# aqc-rev2.net
KiCad netlist of a schematic drawn in EAGLE
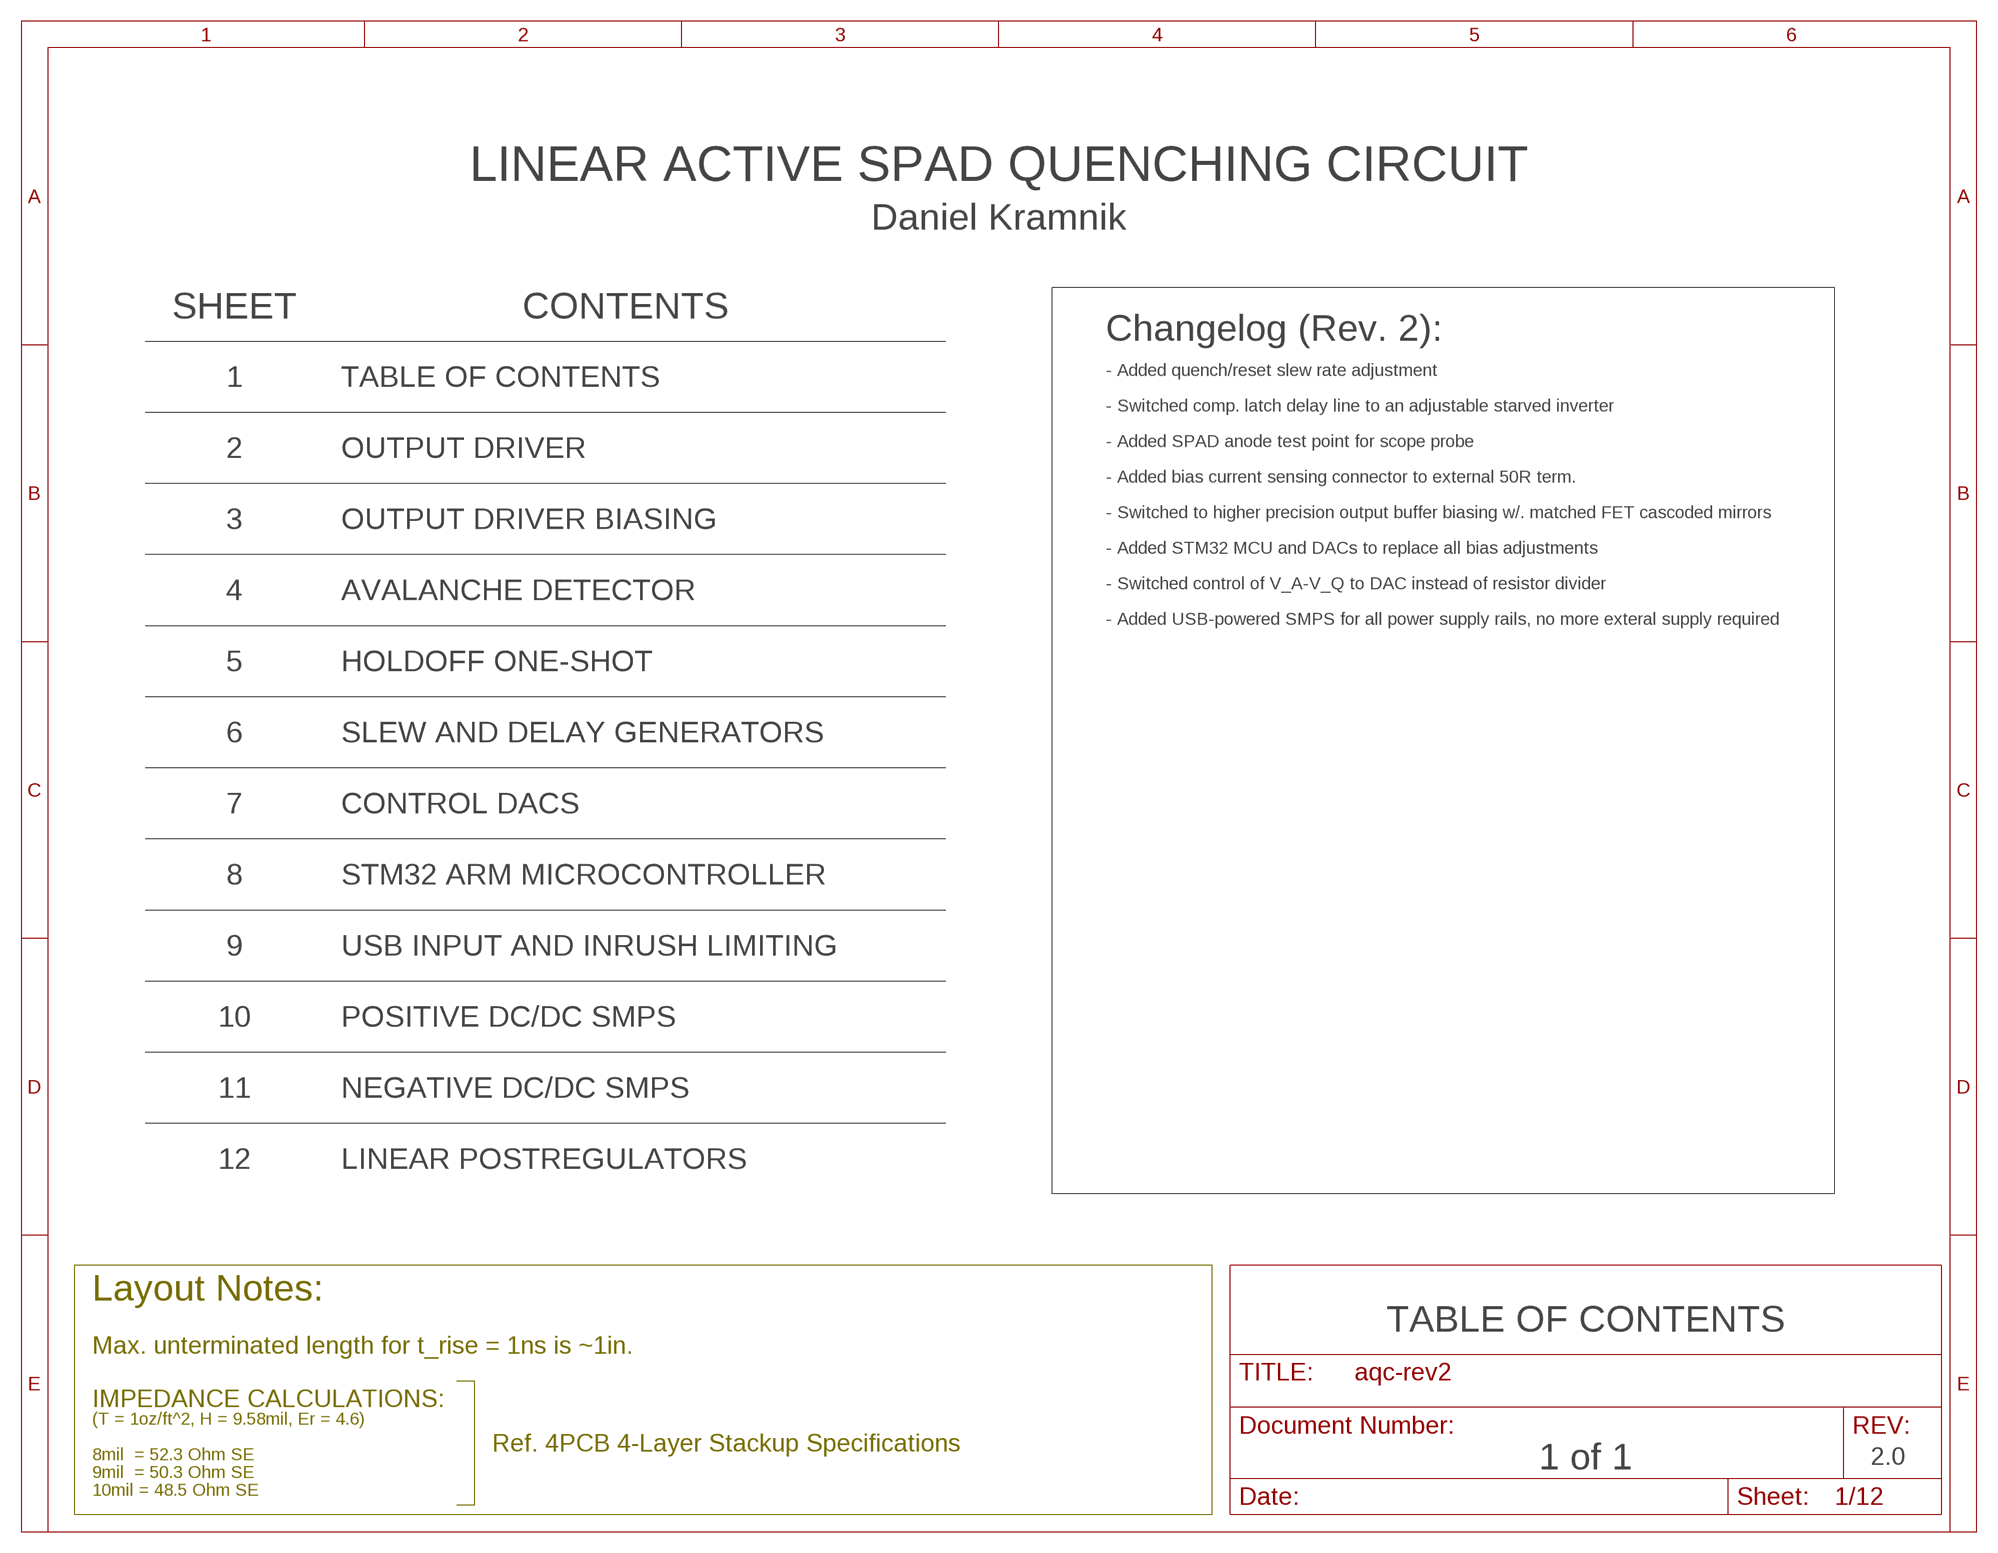
[diagram p0: schematic, sheet 1]
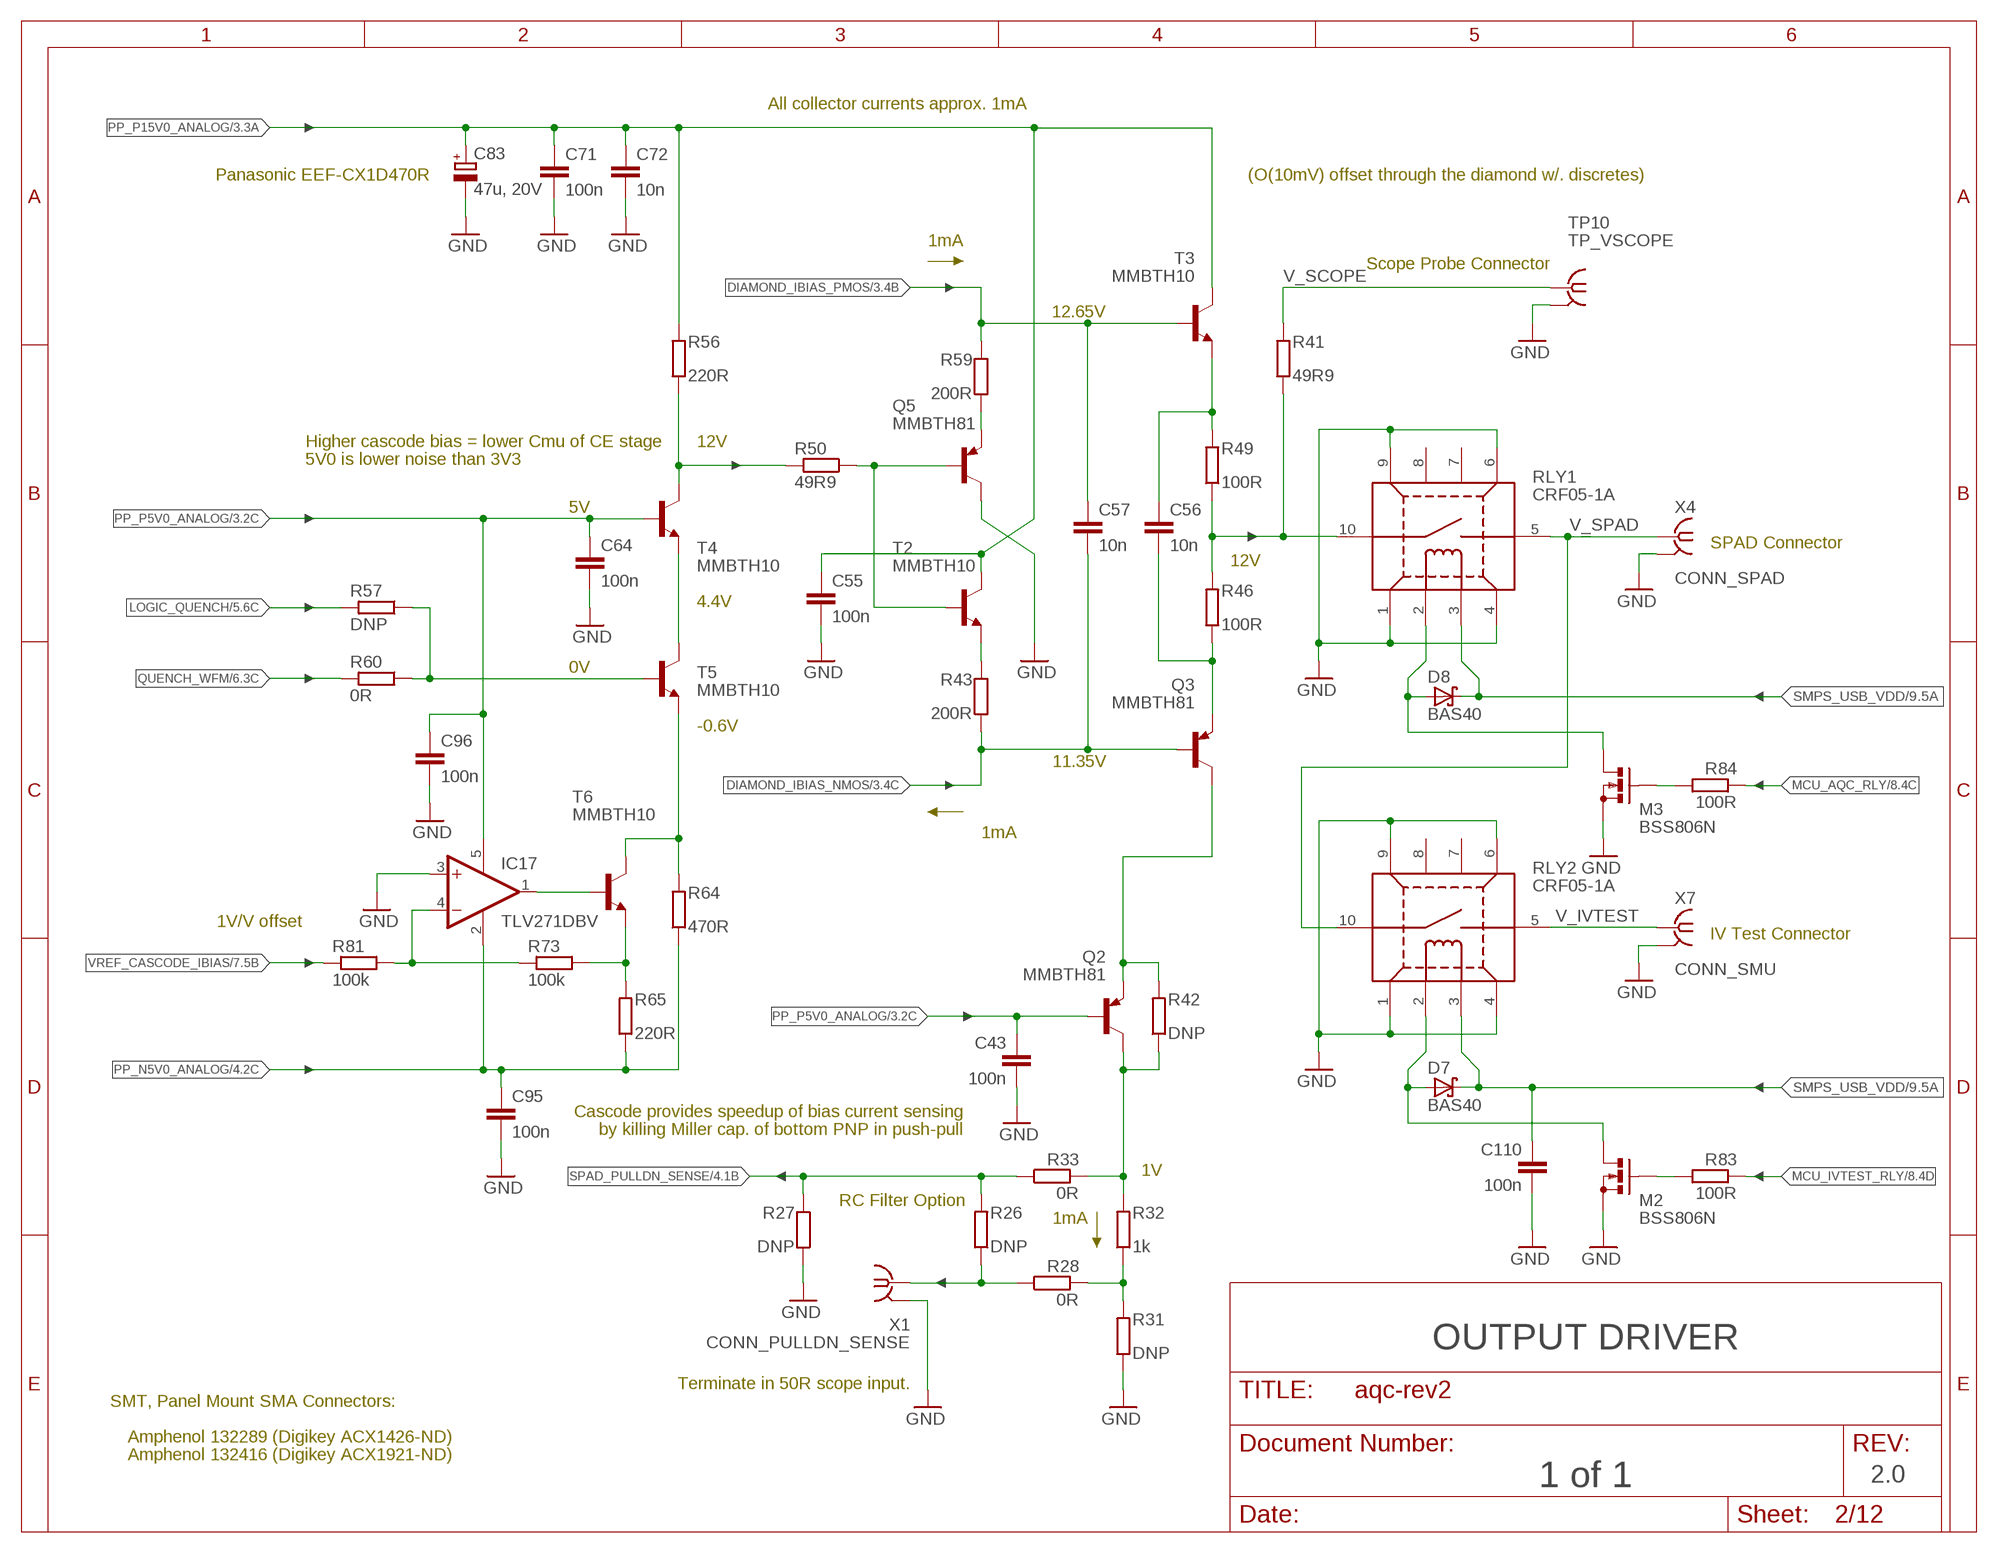
[diagram p1: schematic, sheet 2]
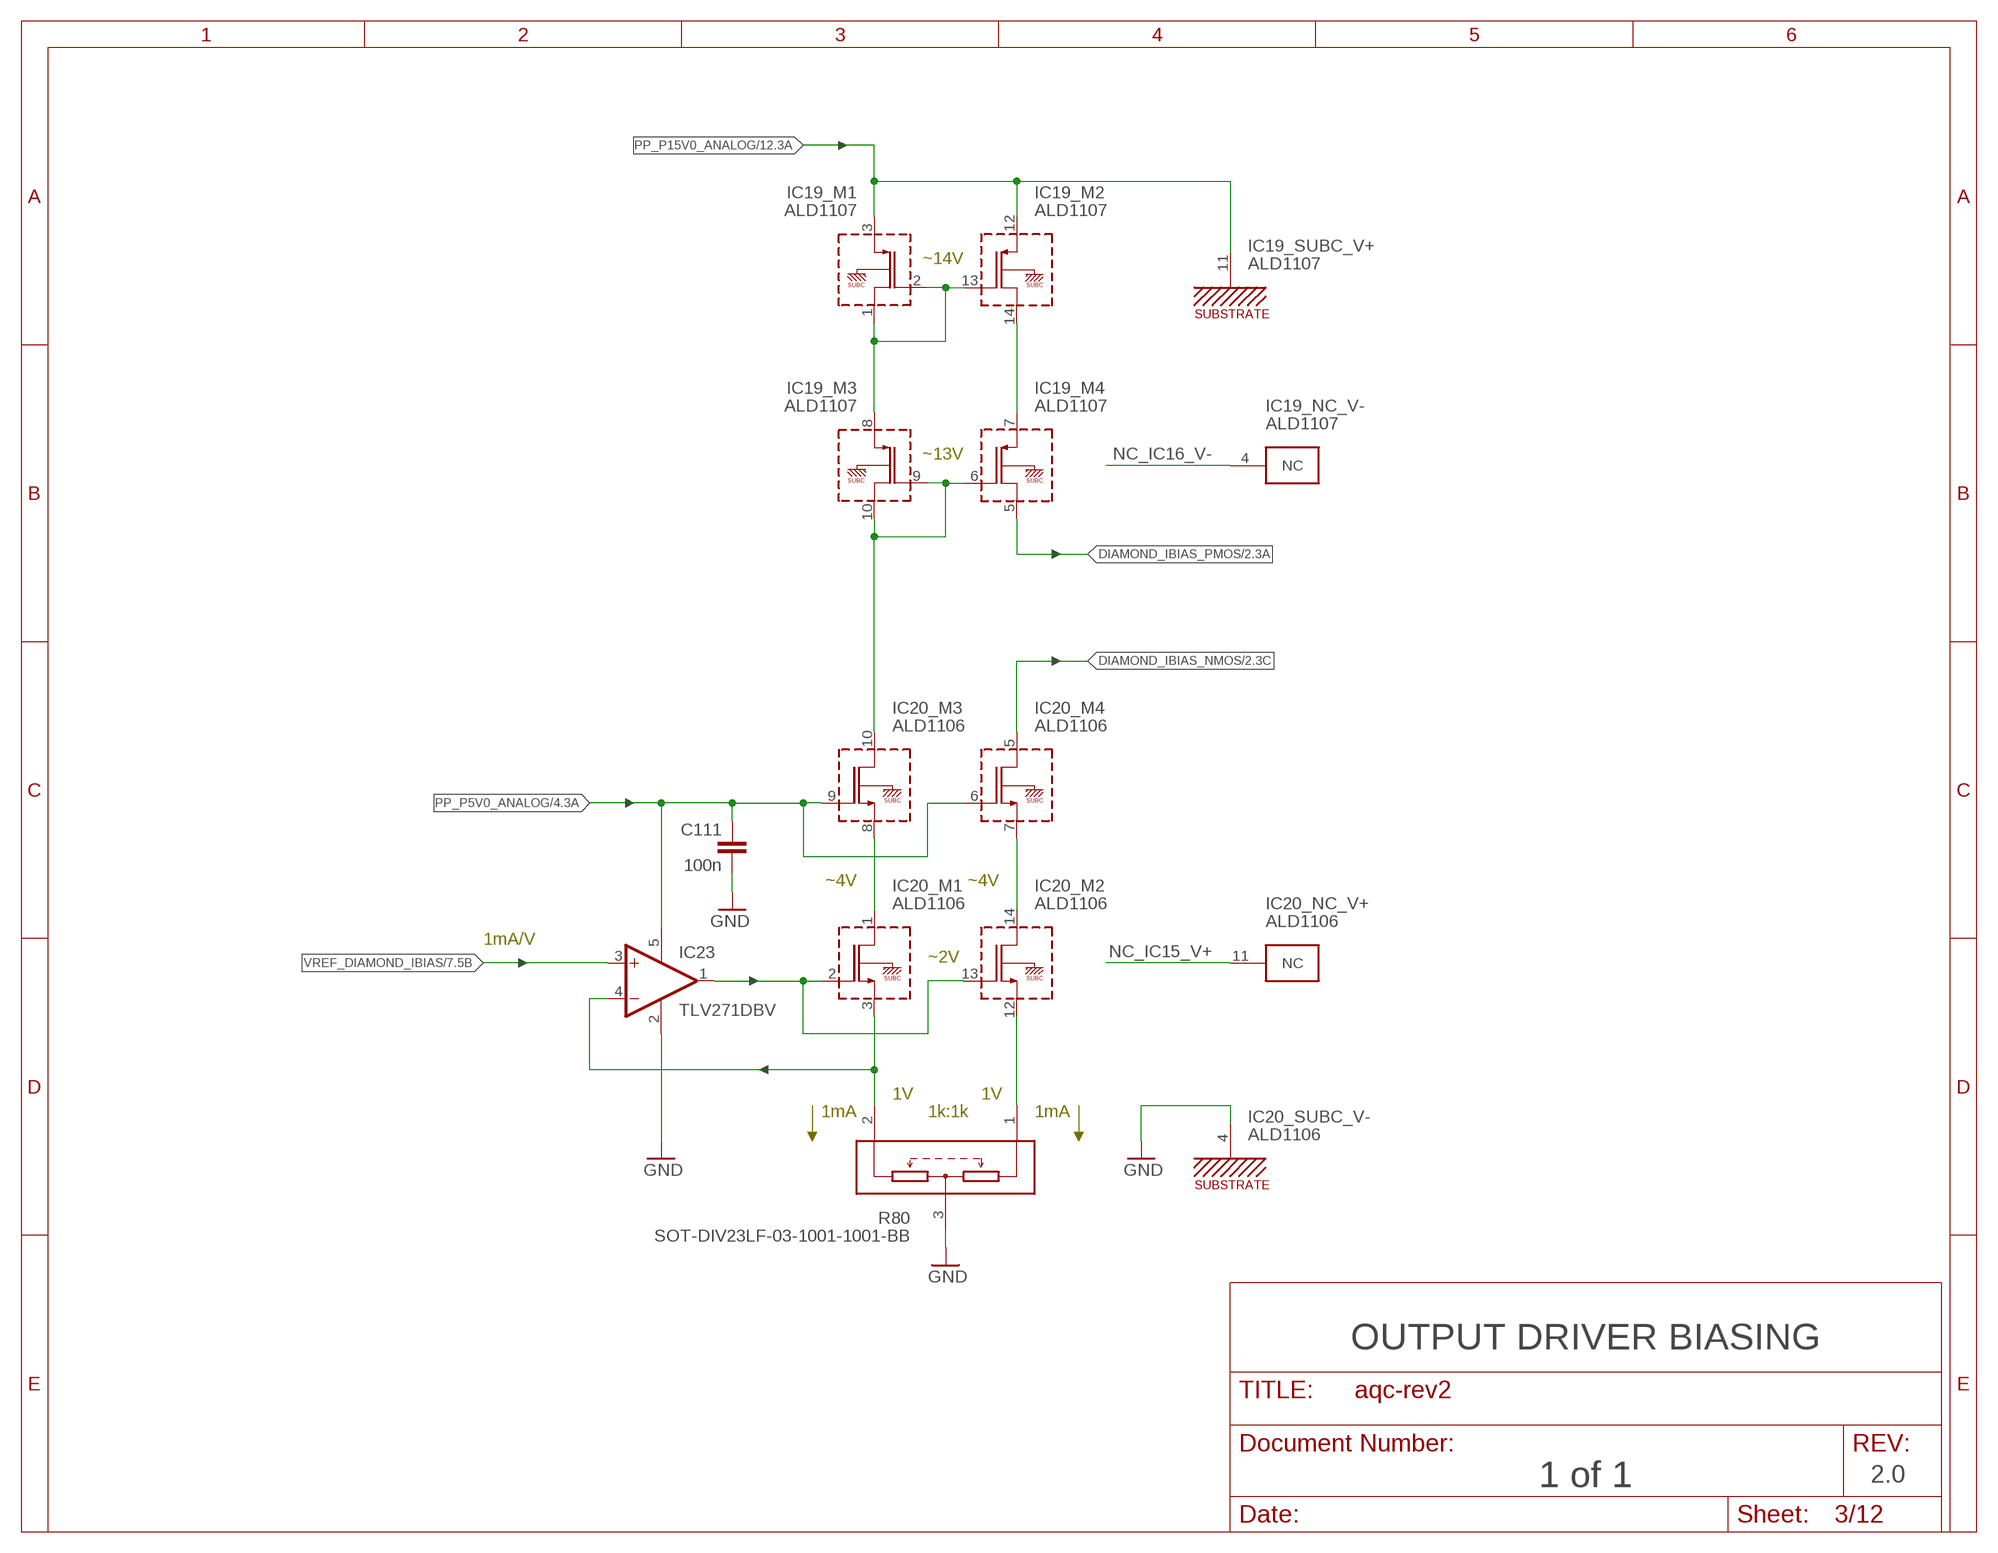
[diagram p2: schematic, sheet 3]
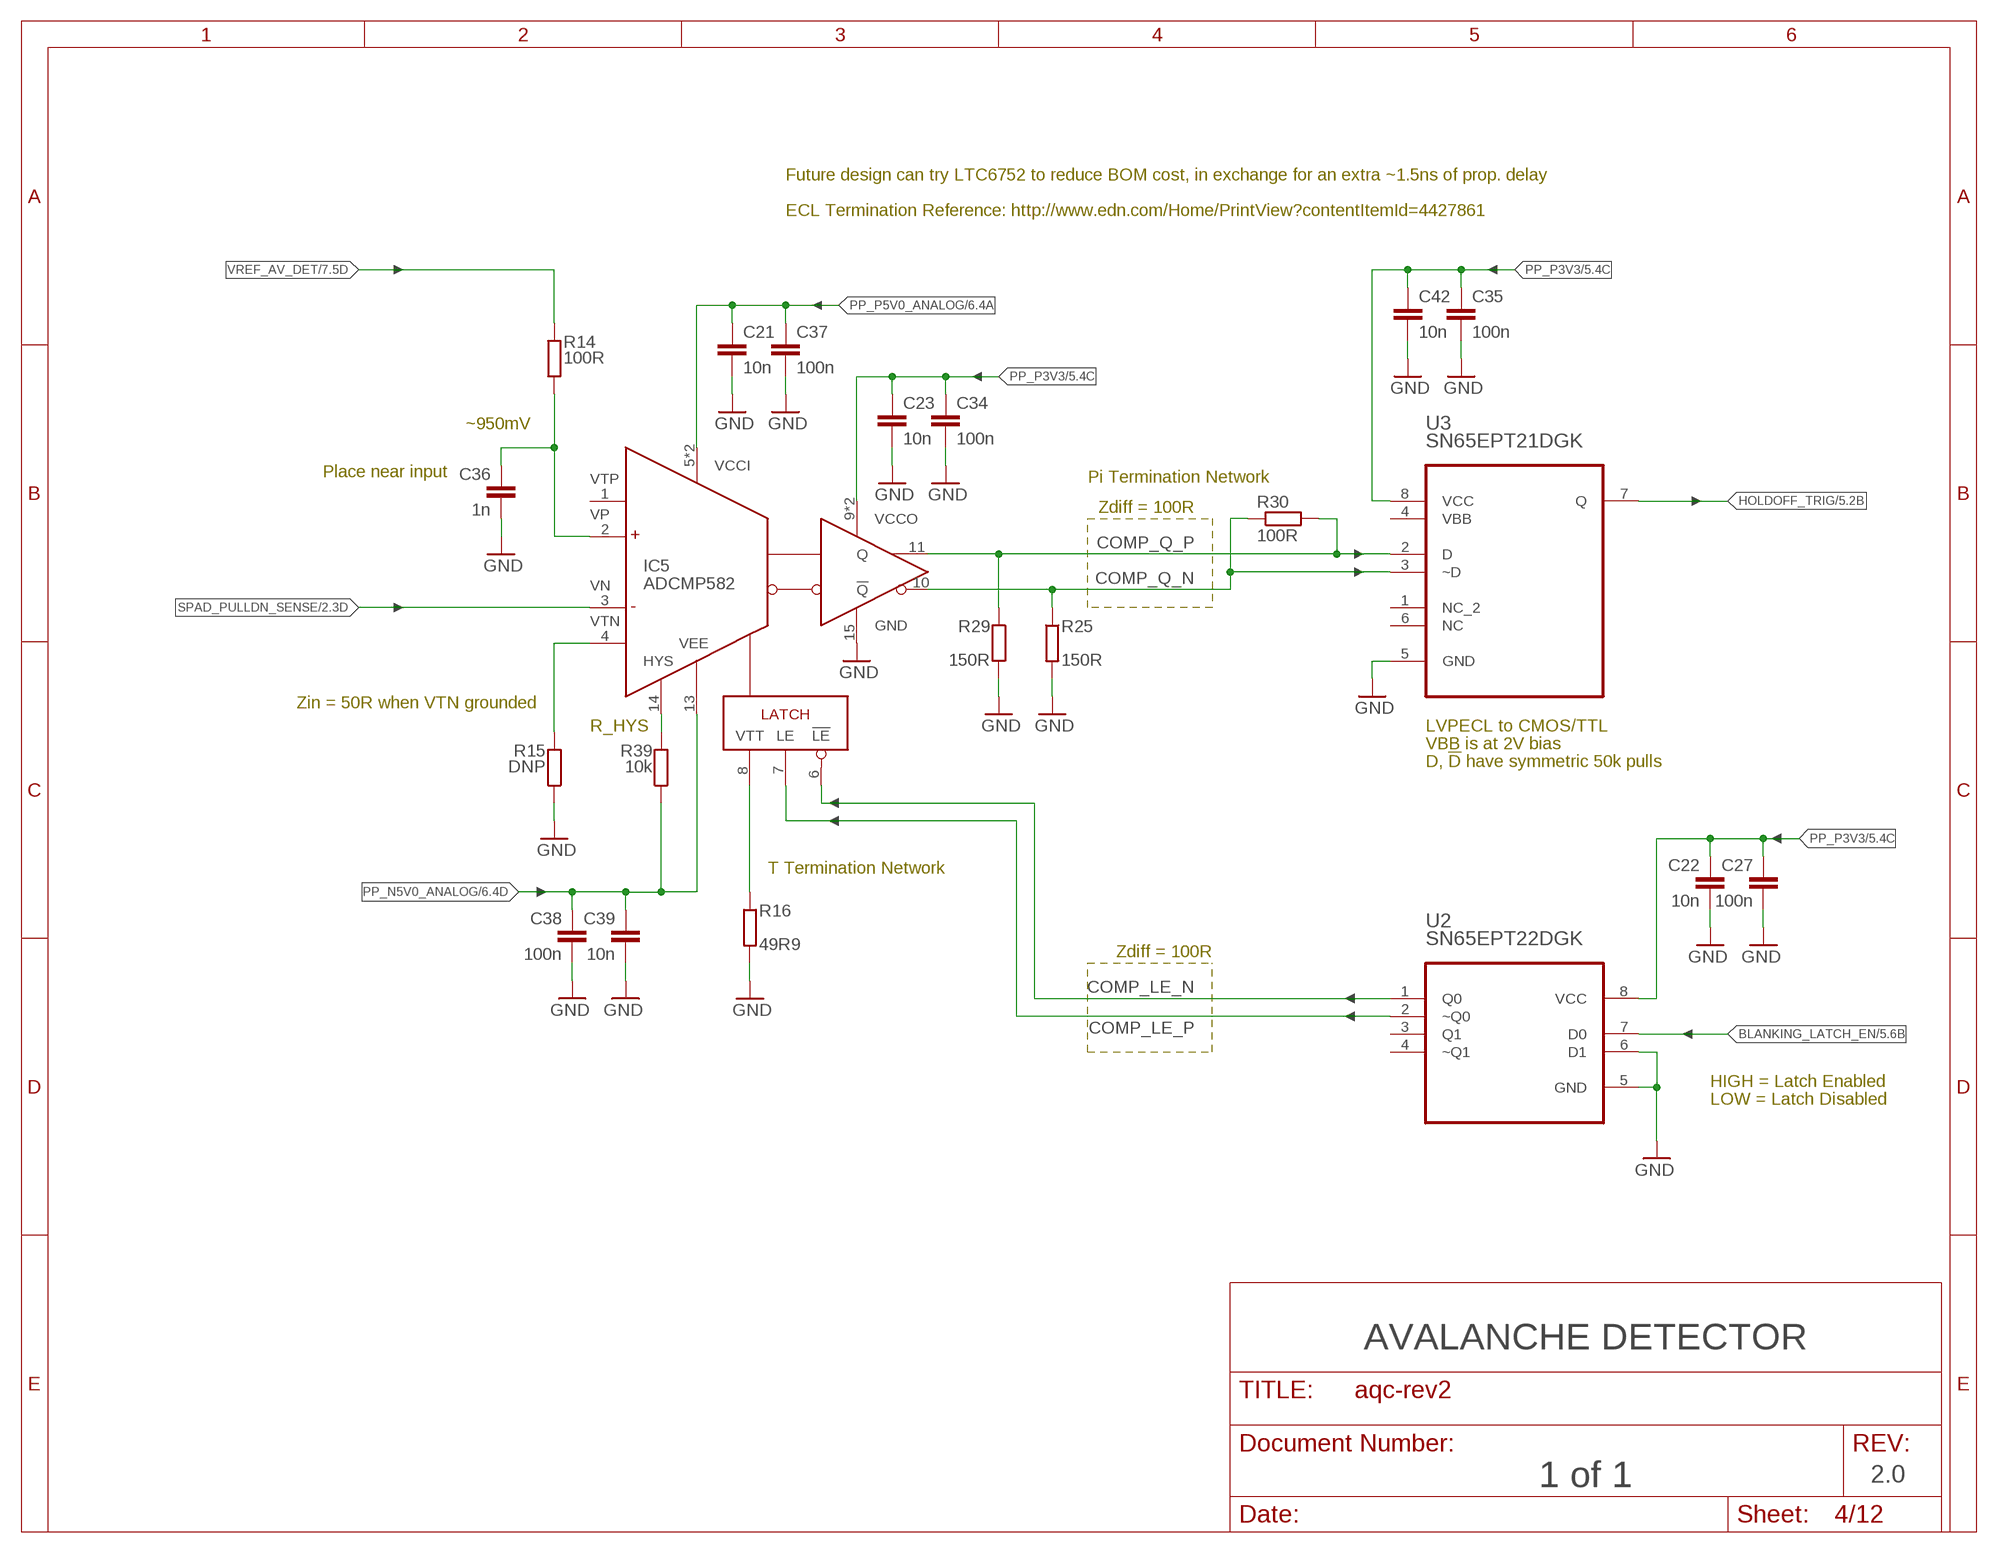
[diagram p3: schematic, sheet 4]
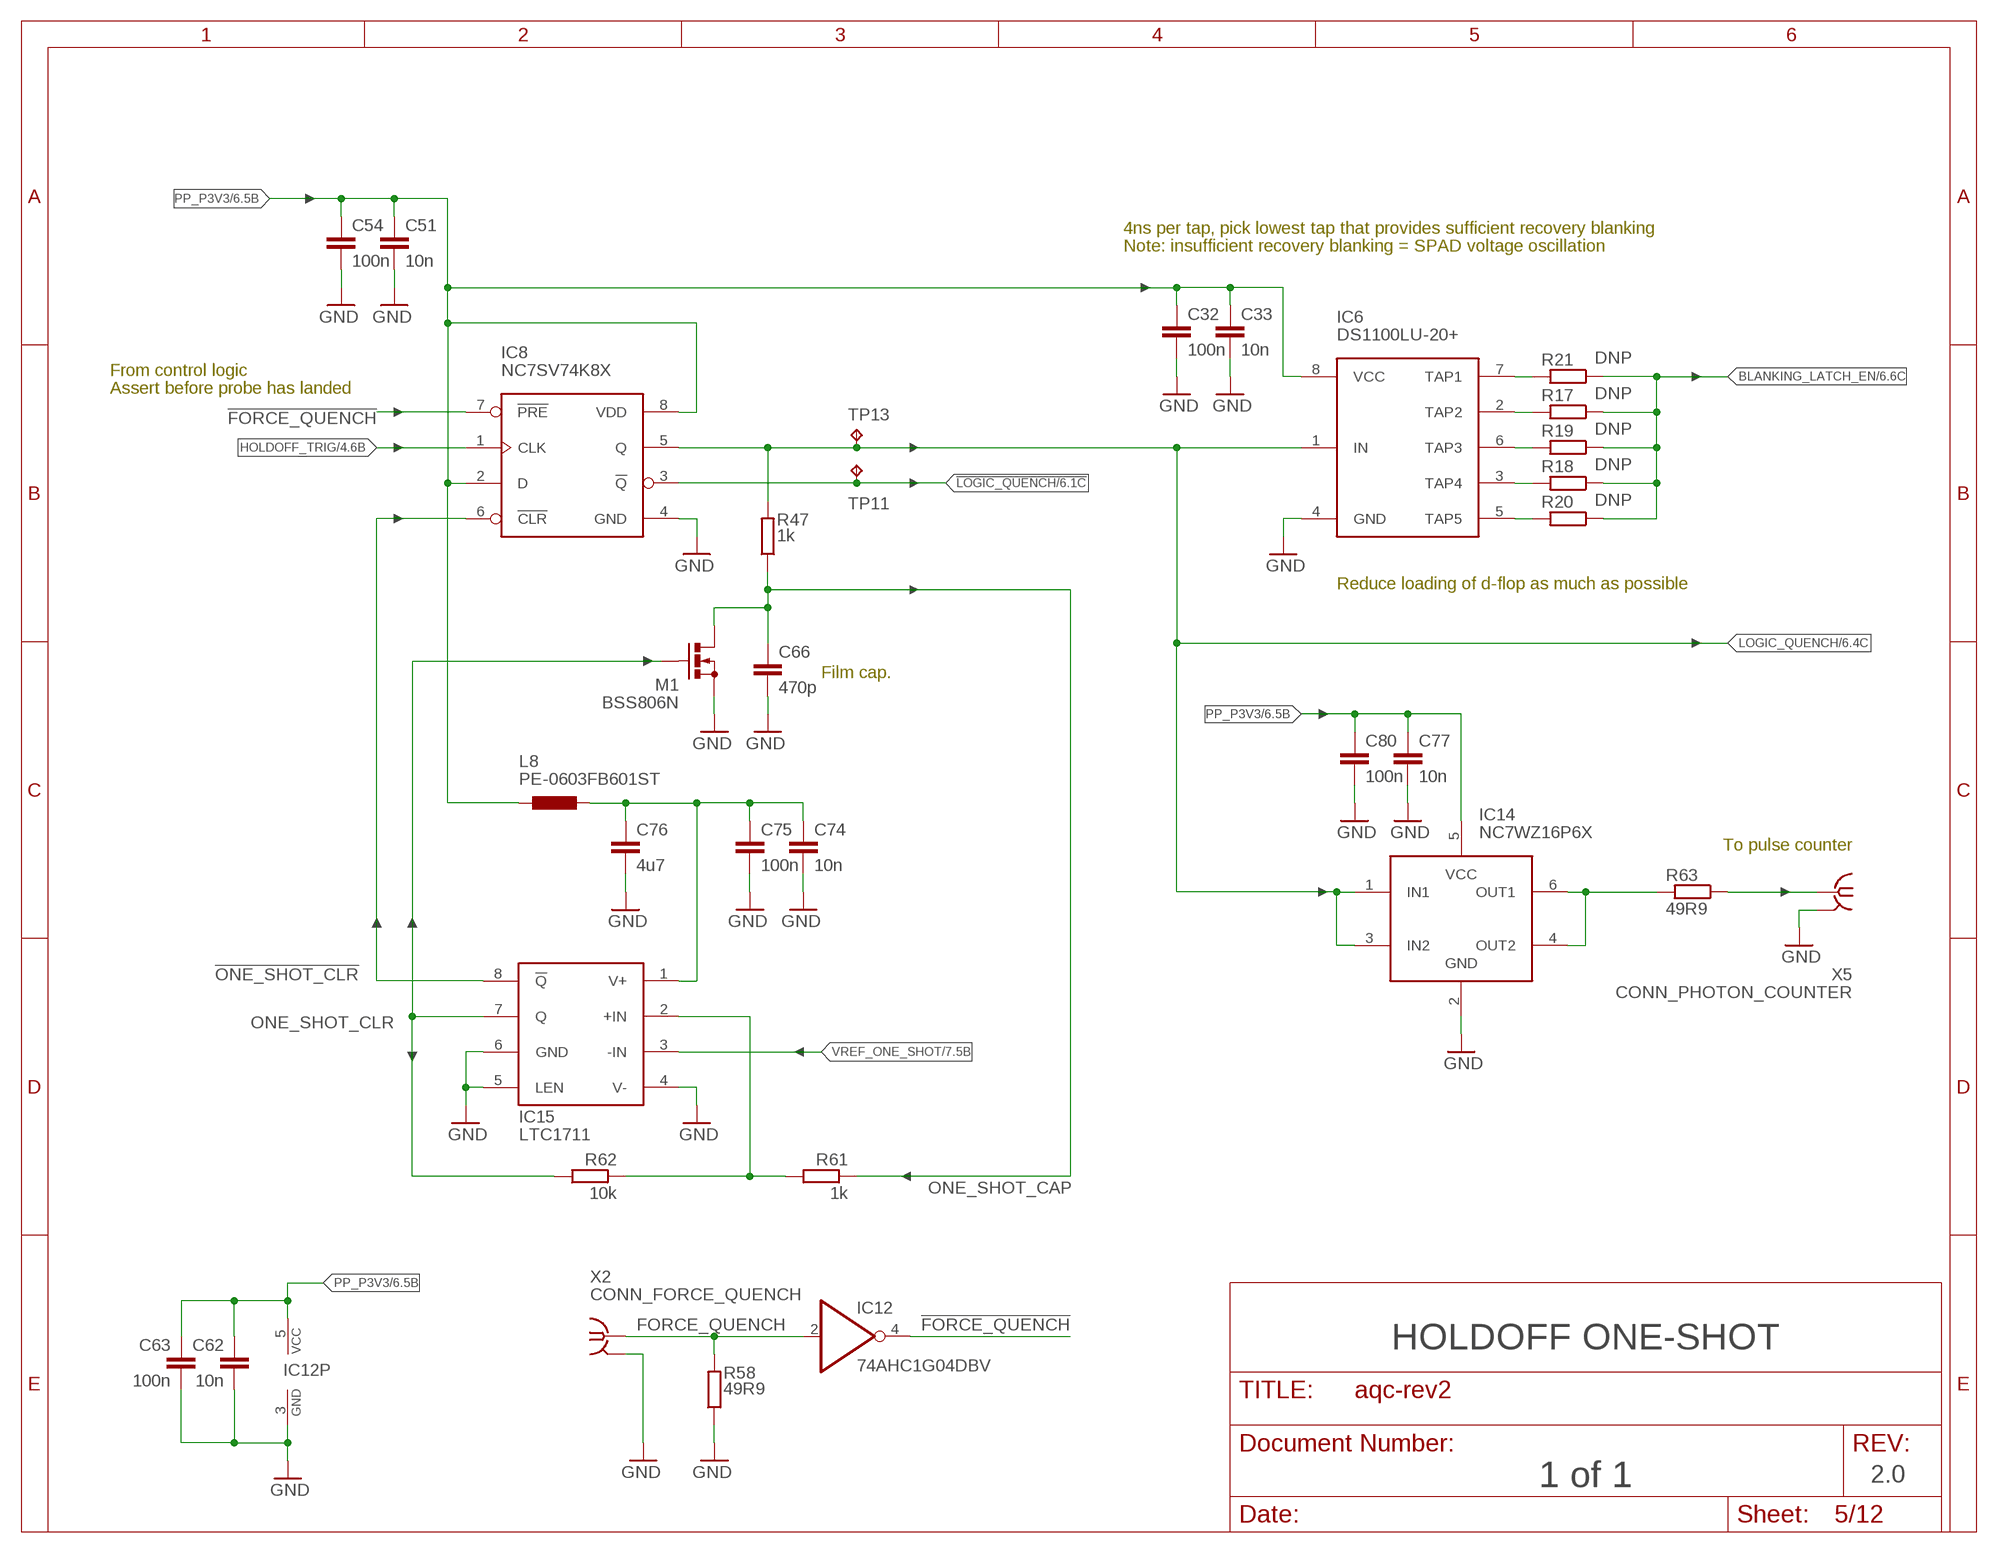
[diagram p4: schematic, sheet 5]
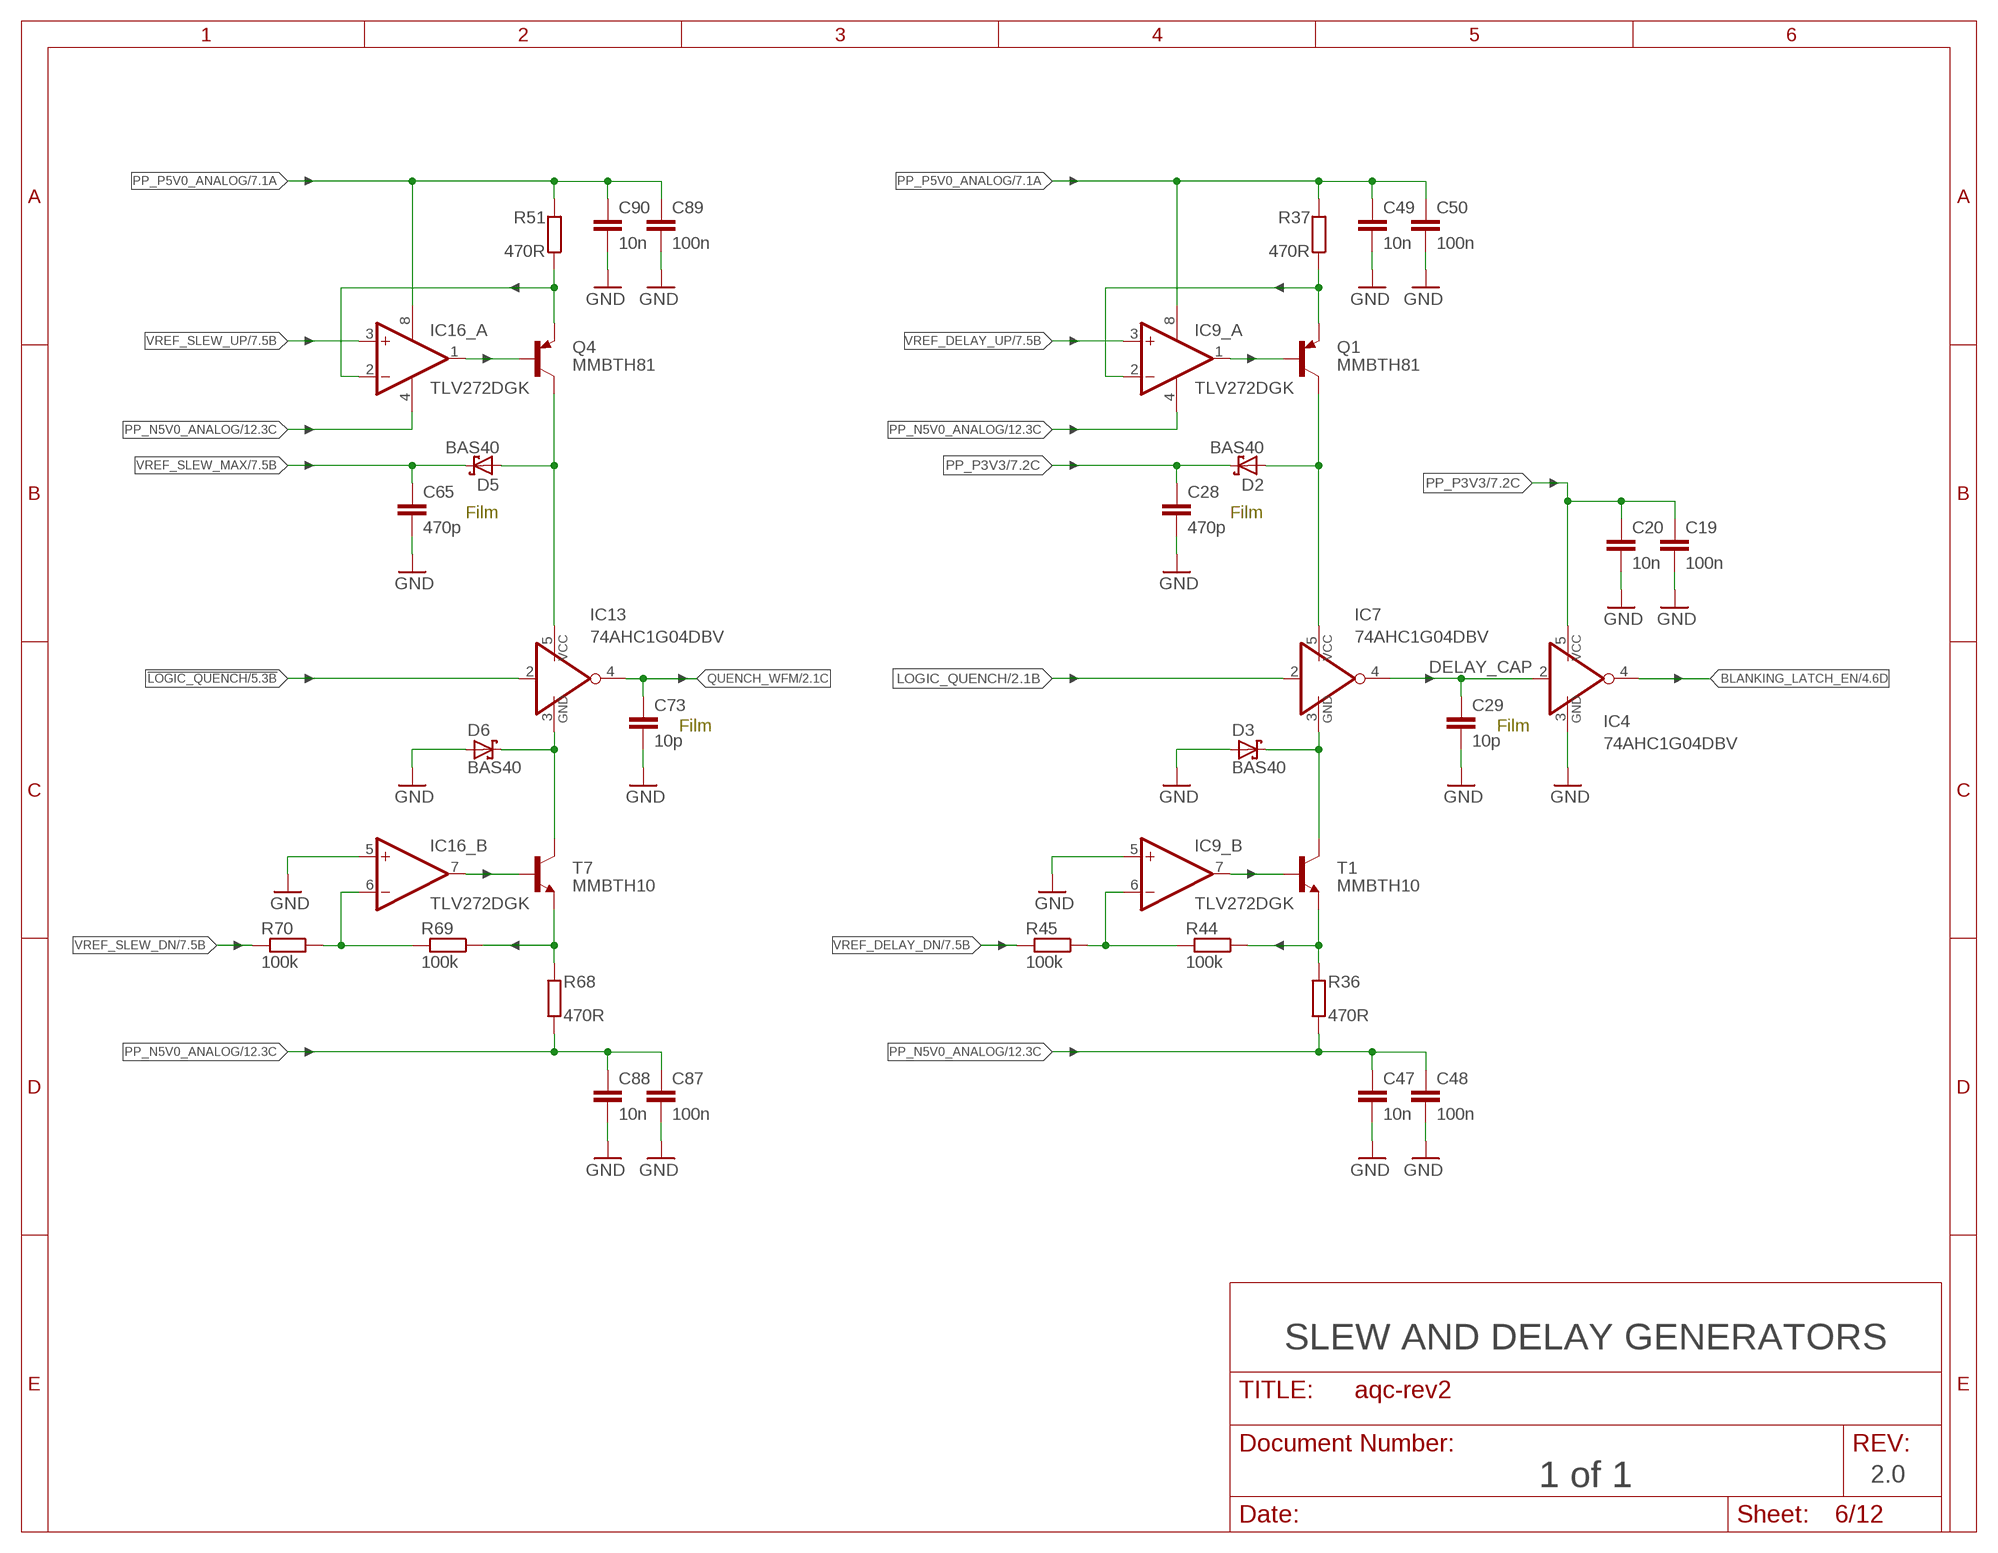
[diagram p5: schematic, sheet 6]
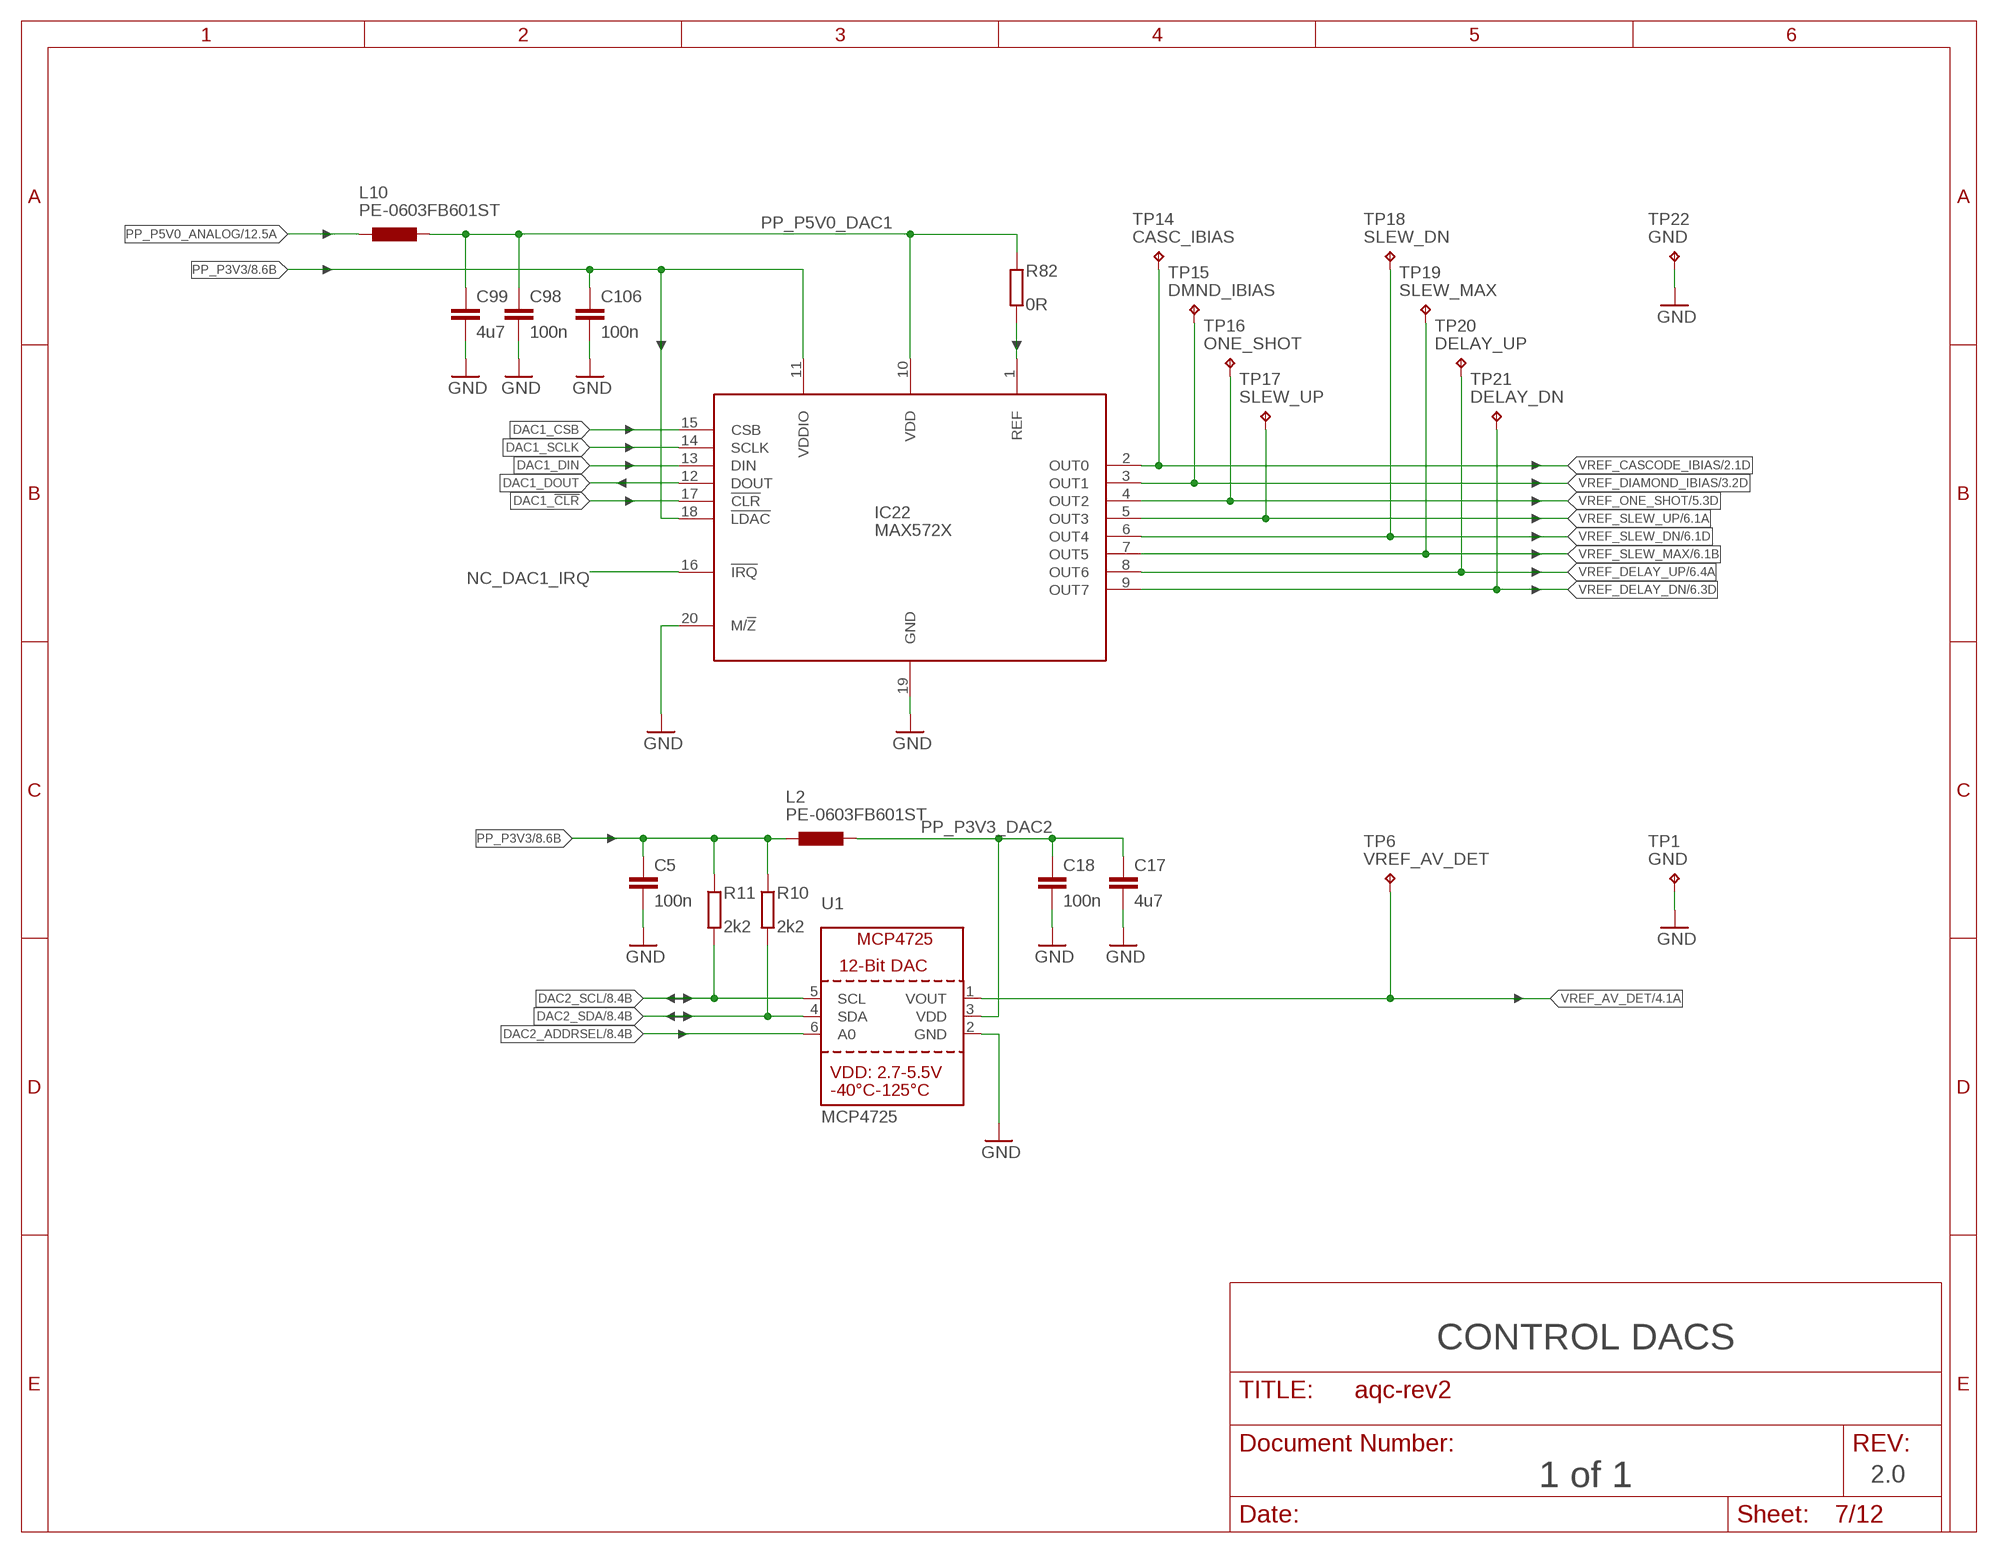
[diagram p6: schematic, sheet 7]
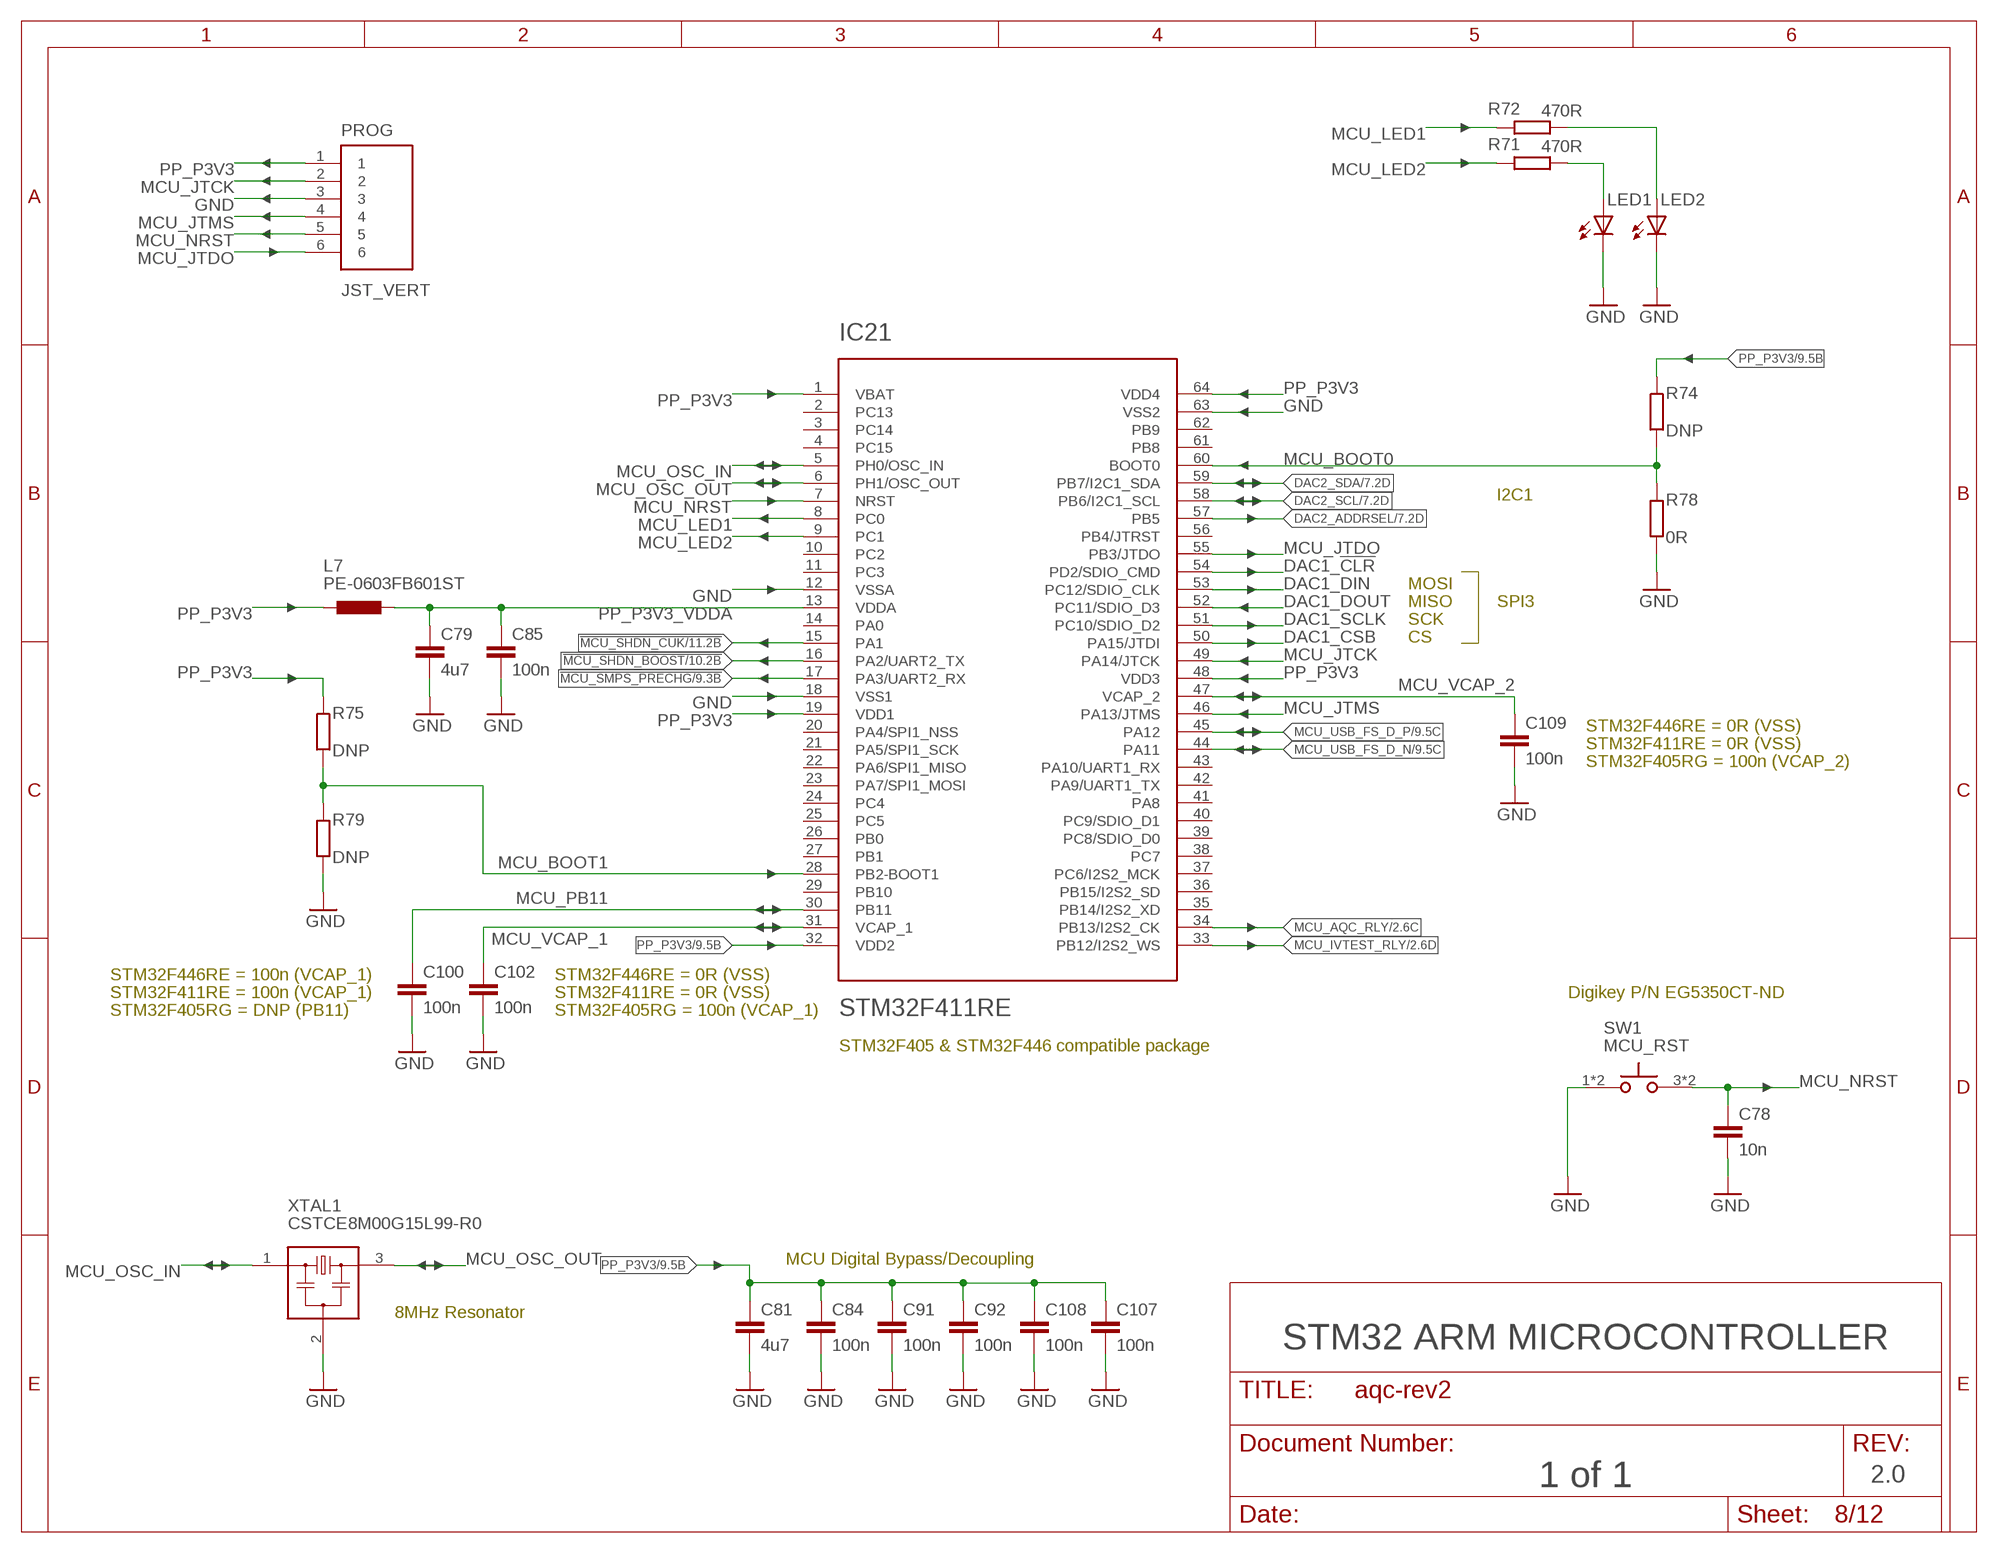
[diagram p7: schematic, sheet 8]
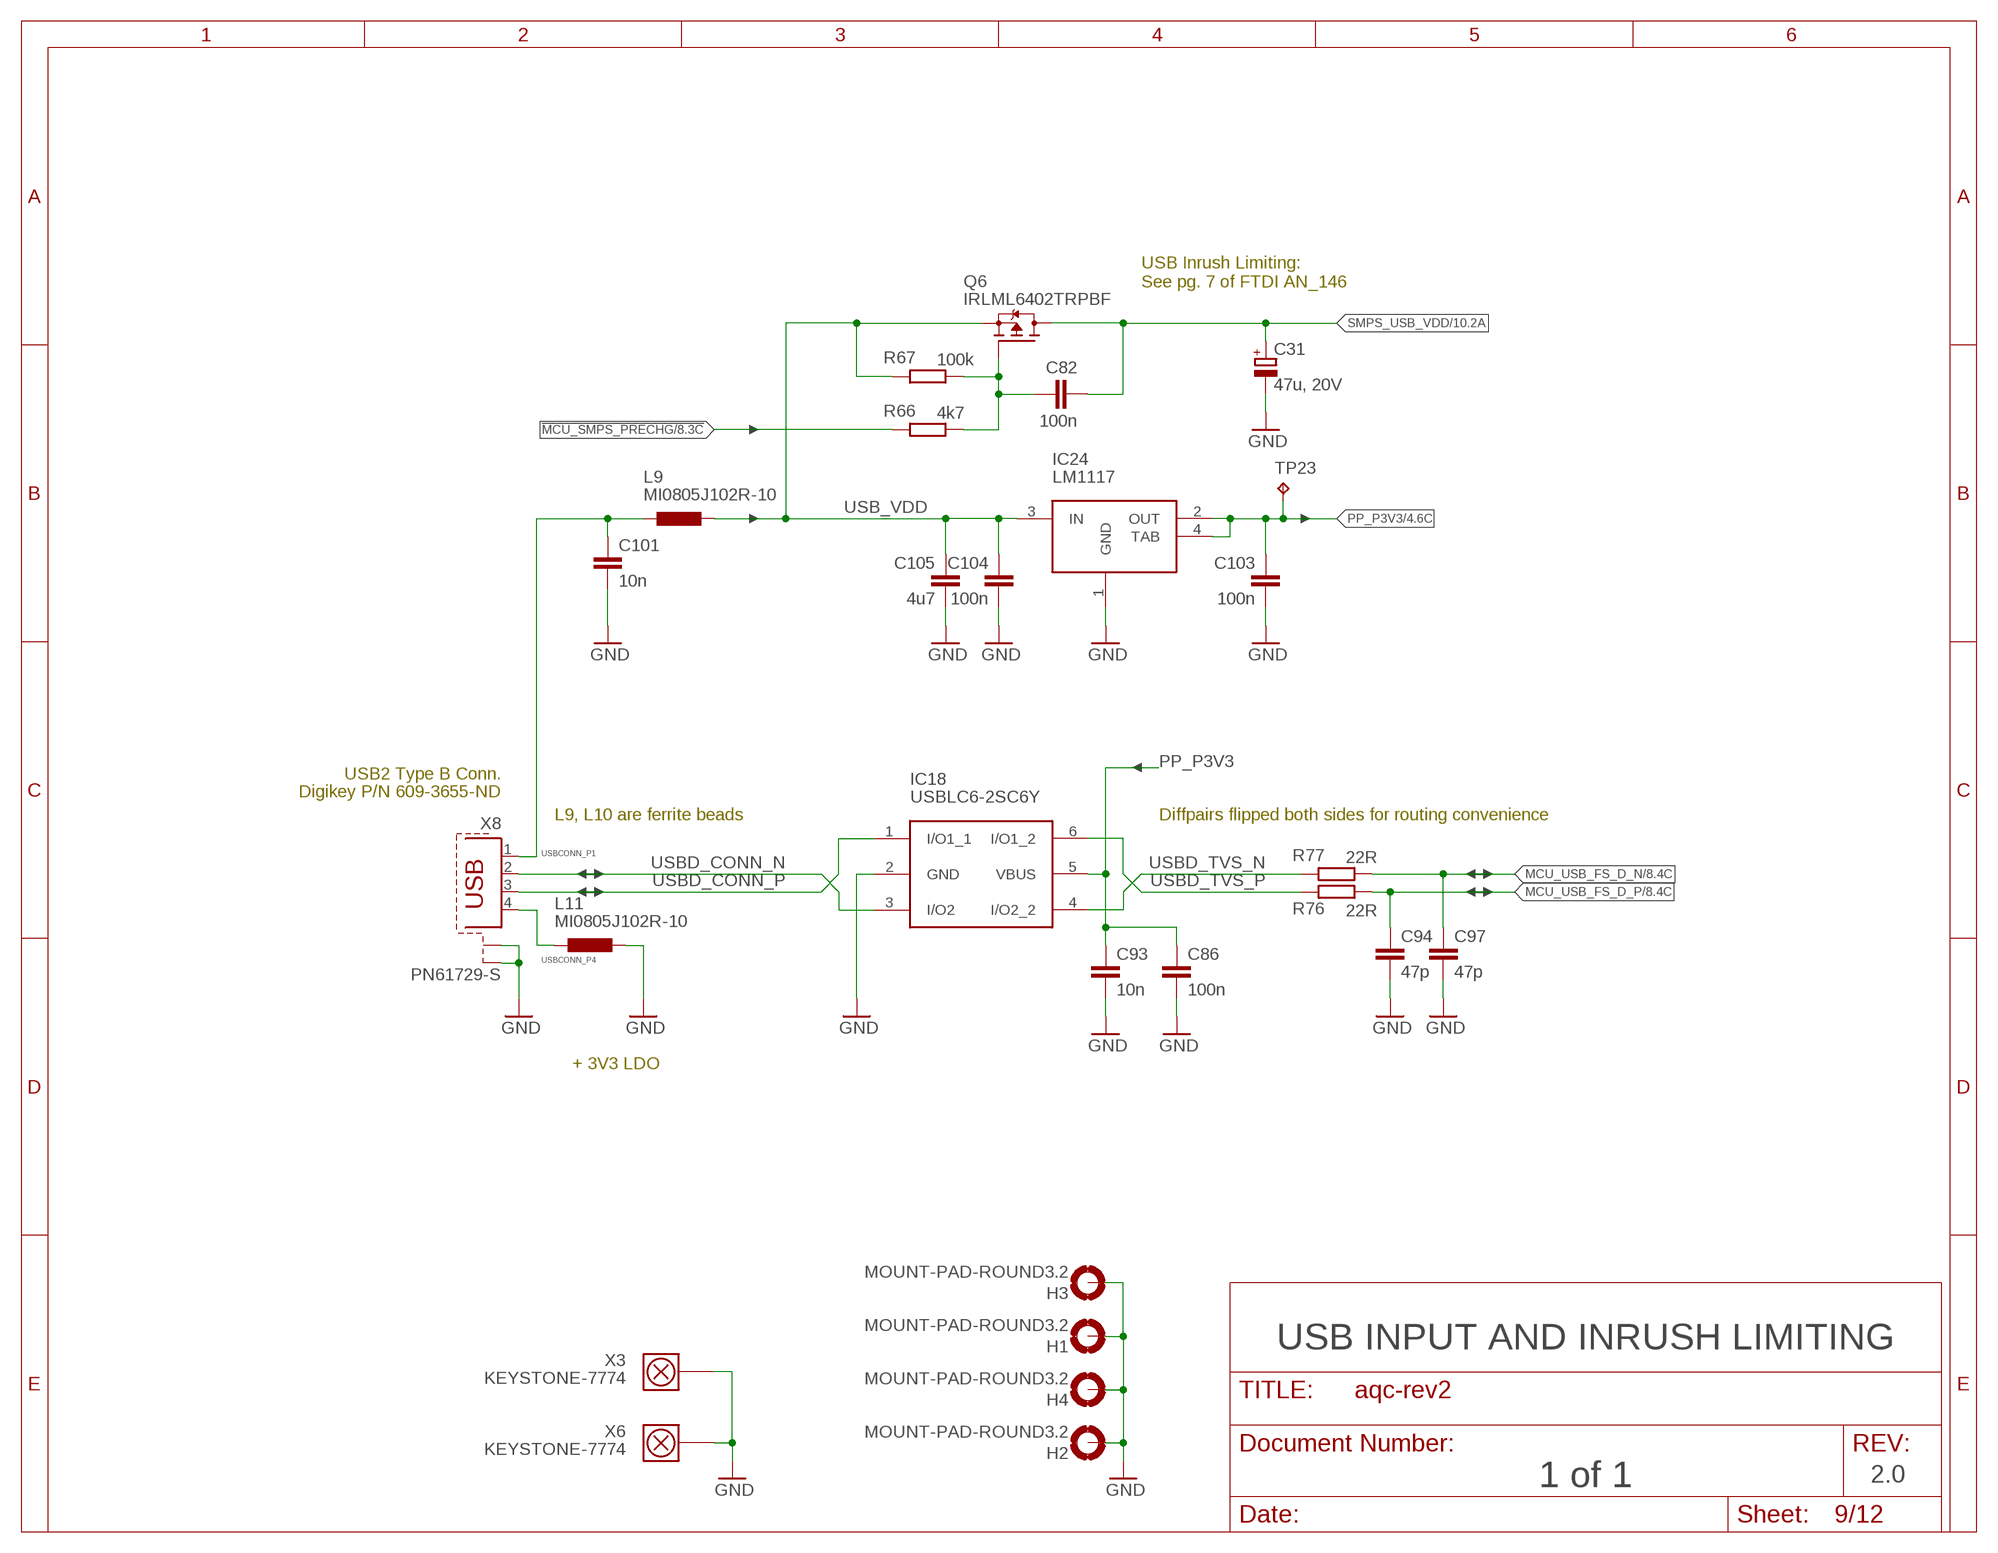
[diagram p8: schematic, sheet 9]
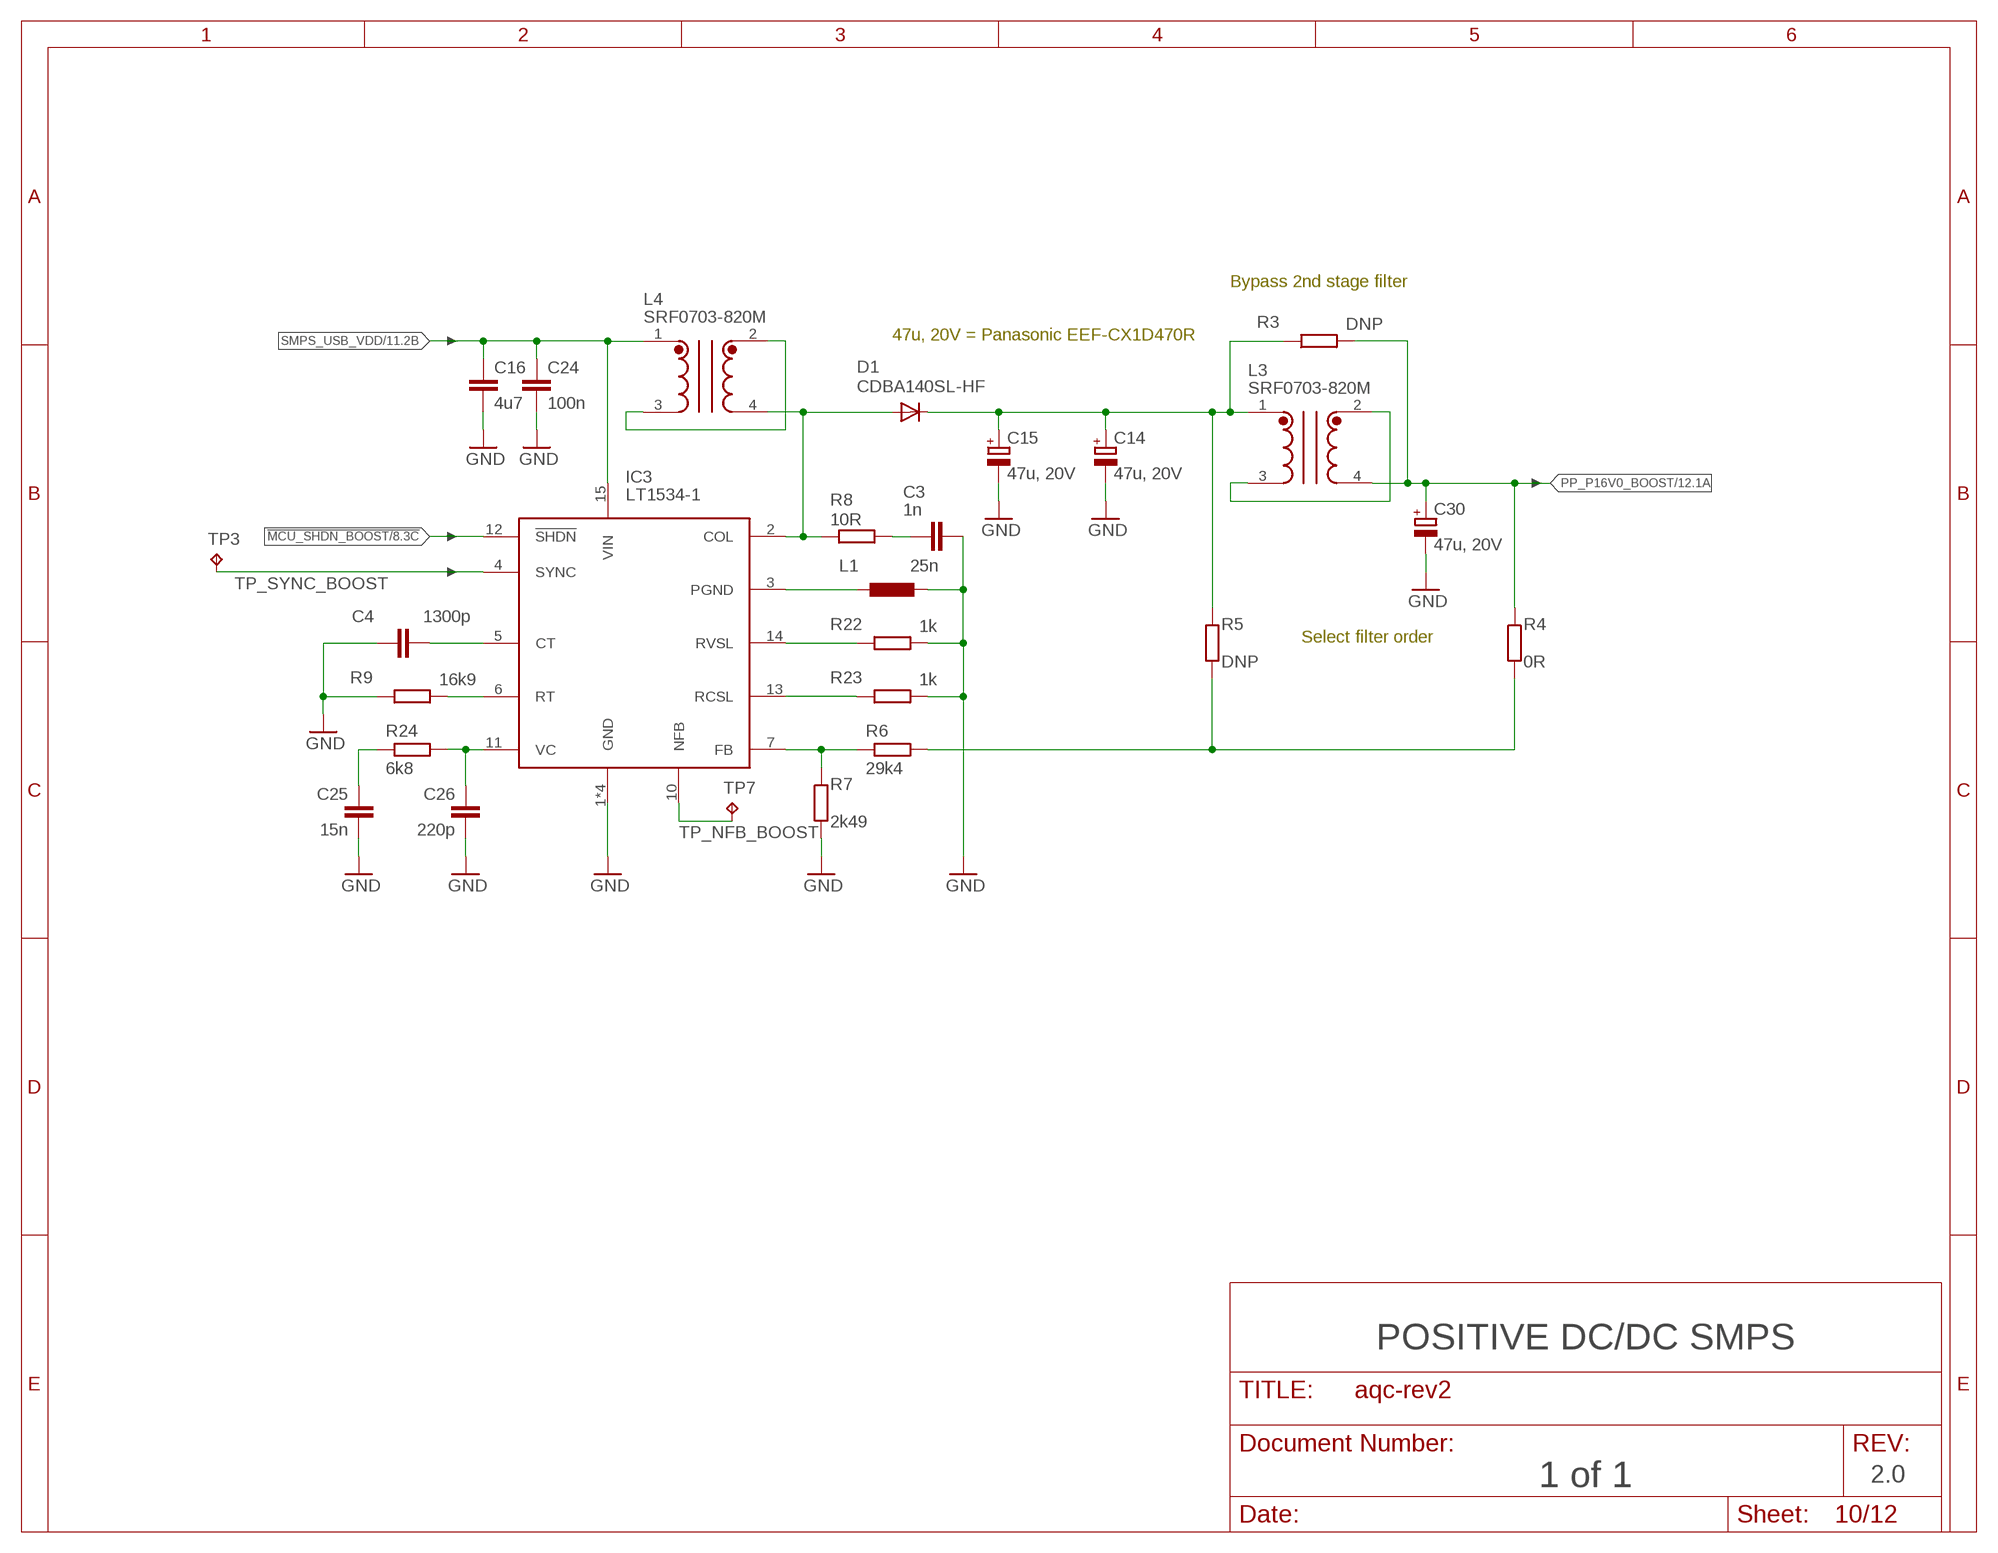
[diagram p9: schematic, sheet 10]
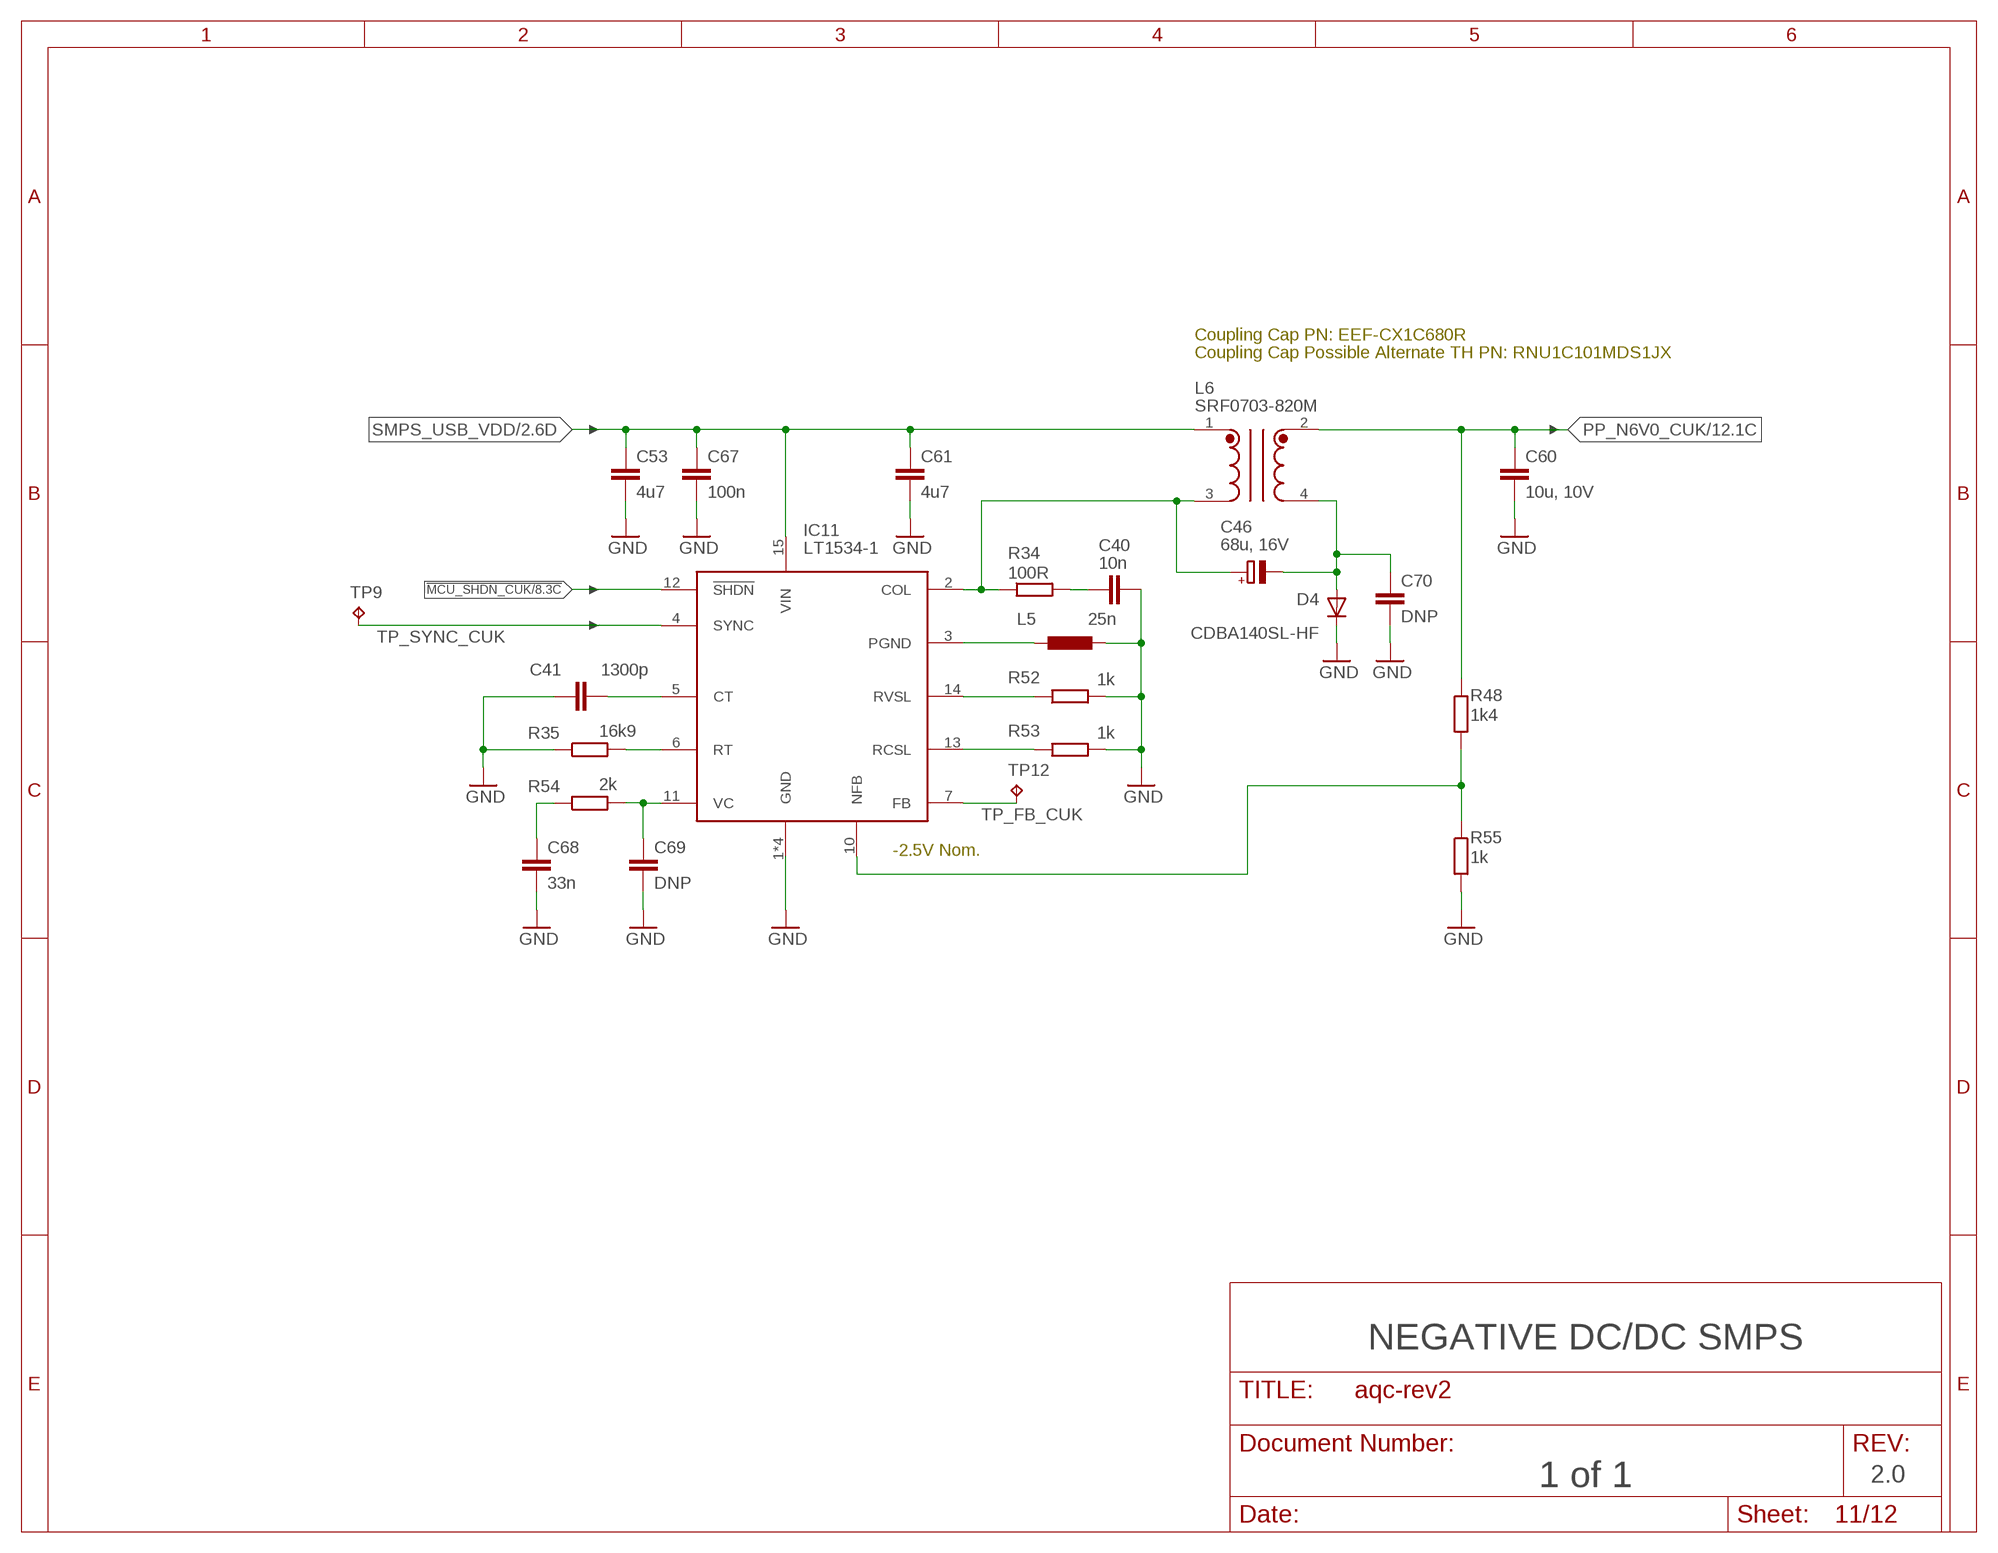
[diagram p10: schematic, sheet 11]
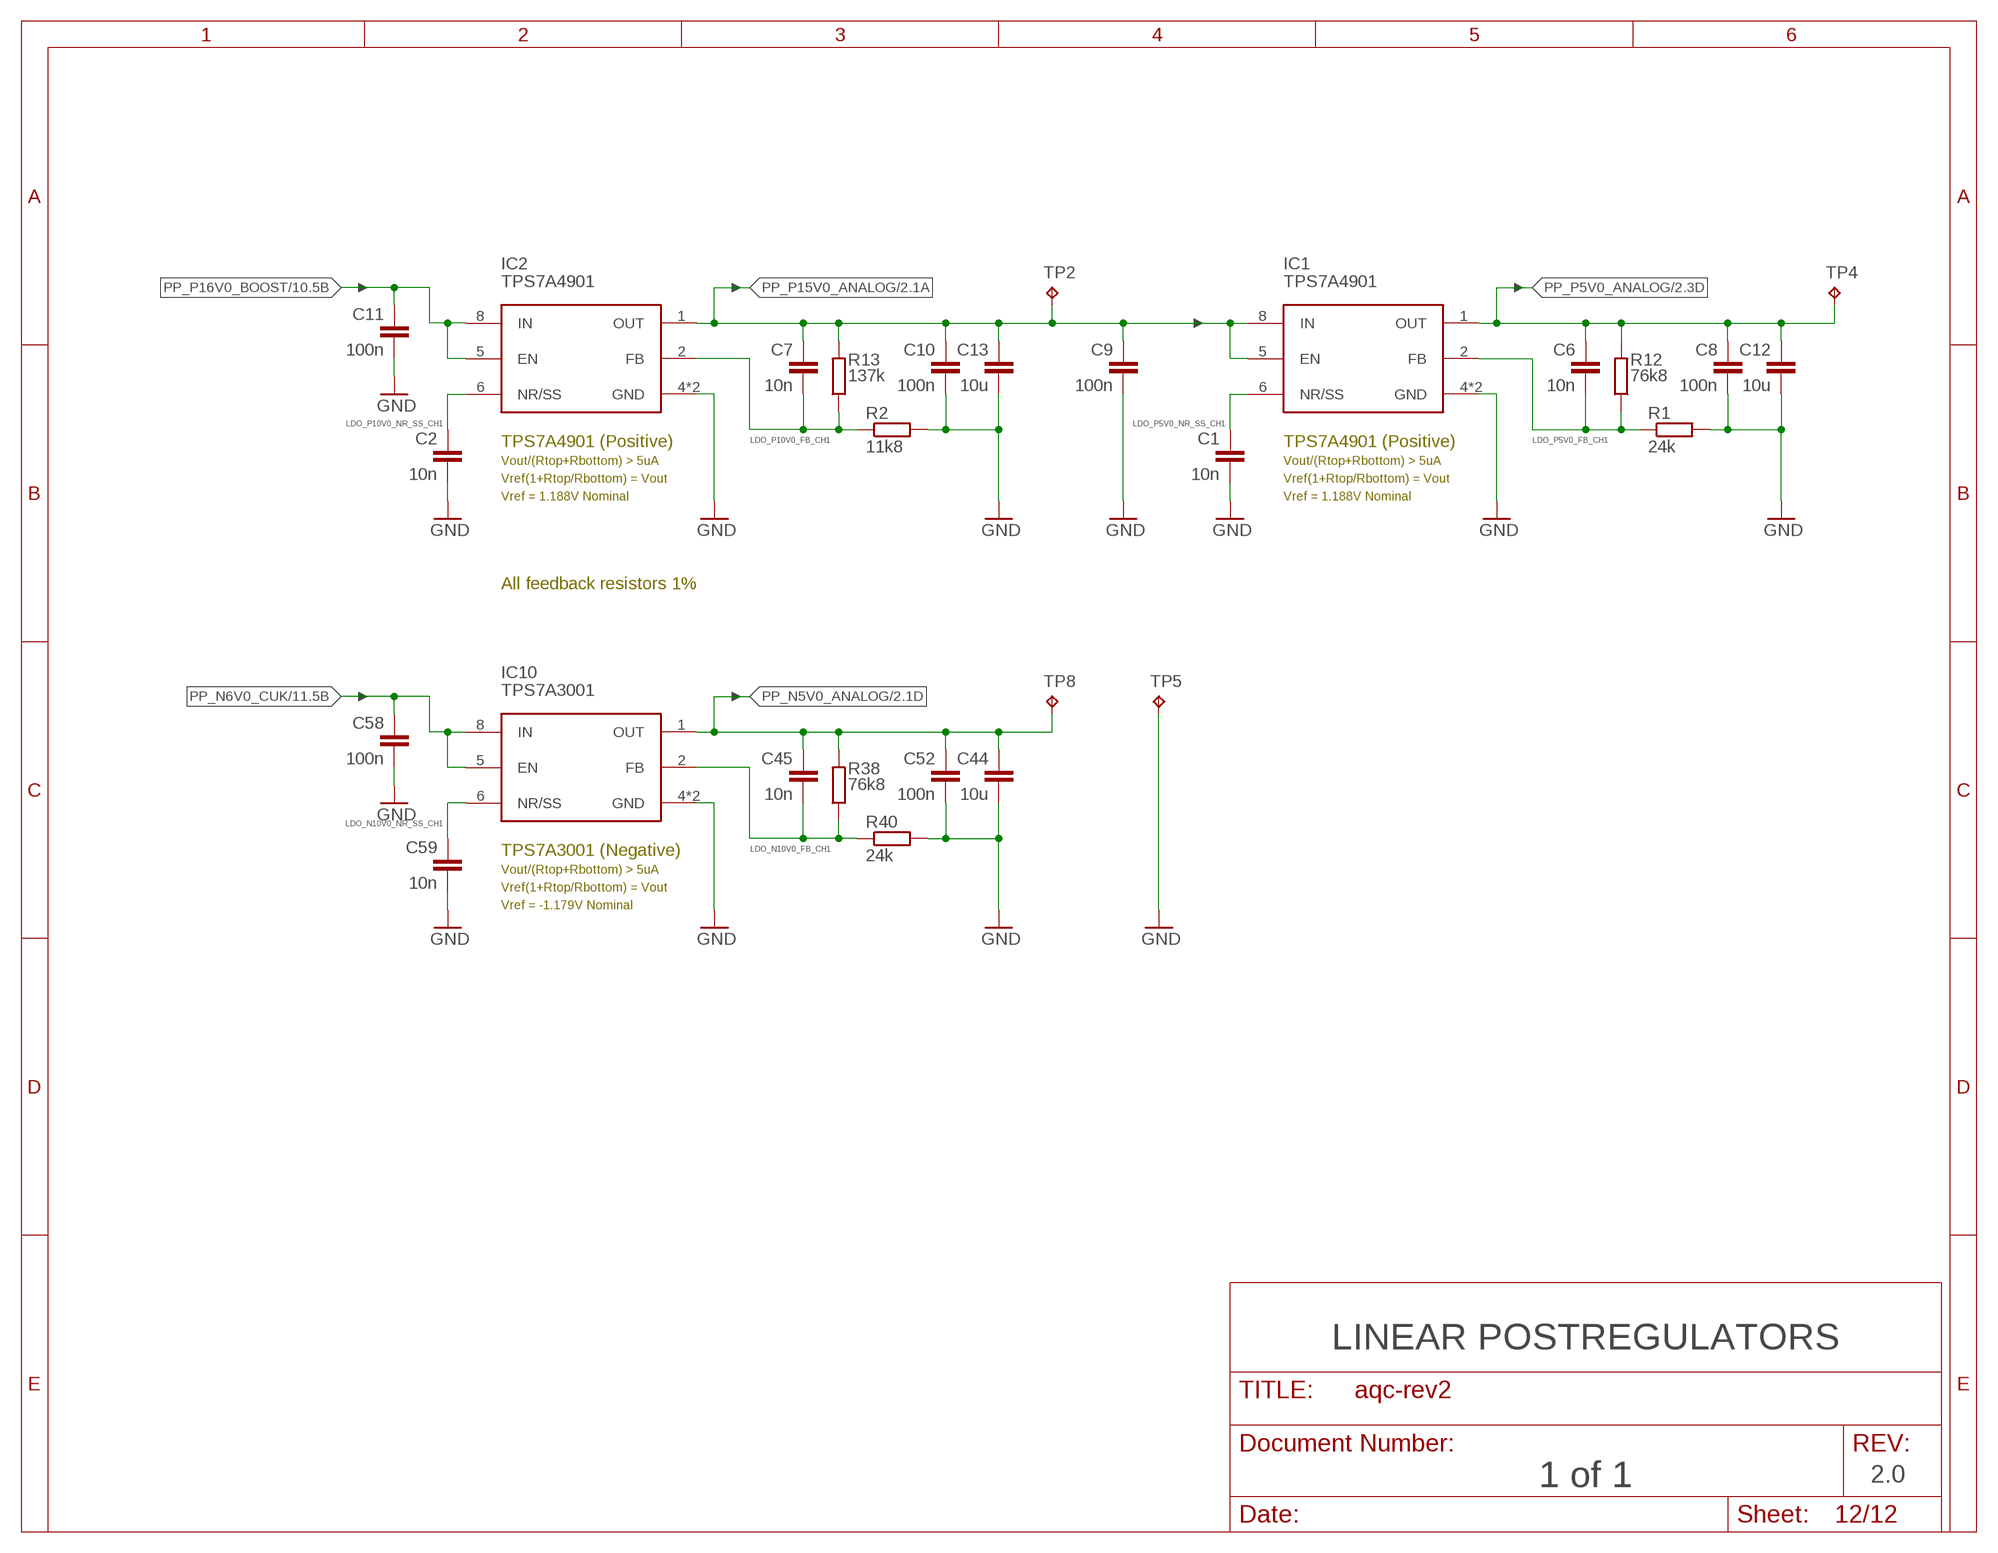
[diagram p11: schematic, sheet 12]

(export (version "E")
  (design (tool "Eeschema 10.0.6"))
  (components
    (comp (ref "C40")
      (value "10n")
      (footprint "eagle-import:C0603")
      (libsource (lib "eagle-import") (part "C-EUC0603"))
    )
    (comp (ref "C41")
      (value "1300p")
      (footprint "eagle-import:C0603")
      (libsource (lib "eagle-import") (part "C-EUC0603"))
    )
    (comp (ref "C46")
      (value "68u, 16V")
      (footprint "eagle-import:CT7343")
      (libsource (lib "eagle-import") (part "CPOL-EUCT7343"))
    )
    (comp (ref "C53")
      (value "4u7")
      (footprint "eagle-import:C0805")
      (libsource (lib "eagle-import") (part "C-EUC0805"))
    )
    (comp (ref "C60")
      (value "10u, 10V")
      (footprint "eagle-import:C0805")
      (libsource (lib "eagle-import") (part "C-EUC0805"))
    )
    (comp (ref "C61")
      (value "4u7")
      (footprint "eagle-import:C0805")
      (libsource (lib "eagle-import") (part "C-EUC0805"))
    )
    (comp (ref "C67")
      (value "100n")
      (footprint "eagle-import:C0603")
      (libsource (lib "eagle-import") (part "C-EUC0603"))
    )
    (comp (ref "C68")
      (value "33n")
      (footprint "eagle-import:C0603")
      (libsource (lib "eagle-import") (part "C-EUC0603"))
    )
    (comp (ref "C69")
      (value "DNP")
      (footprint "eagle-import:C0603")
      (libsource (lib "eagle-import") (part "C-EUC0603"))
    )
    (comp (ref "C70")
      (value "DNP")
      (footprint "eagle-import:C0603")
      (libsource (lib "eagle-import") (part "C-EUC0603"))
    )
    (comp (ref "D4")
      (value "CDBA140SL-HF")
      (footprint "eagle-import:DO214AC")
      (libsource (lib "eagle-import") (part "DIODE-DO214AC"))
    )
    (comp (ref "IC11")
      (value "LT1534-1")
      (footprint "eagle-import:SO16")
      (libsource (lib "eagle-import") (part "LT1534"))
    )
    (comp (ref "L5")
      (value "25n")
      (footprint "eagle-import:R0603")
      (libsource (lib "eagle-import") (part "INDUCTOR0603"))
    )
    (comp (ref "L6")
      (value "SRF0703-820M")
      (footprint "eagle-import:SRF0703")
      (libsource (lib "eagle-import") (part "SRF0703"))
    )
    (comp (ref "R34")
      (value "100R")
      (footprint "eagle-import:R0603")
      (libsource (lib "eagle-import") (part "resistor_R-EU_R0603"))
    )
    (comp (ref "R35")
      (value "16k9")
      (footprint "eagle-import:R0603")
      (libsource (lib "eagle-import") (part "R-EU_R0603"))
    )
    (comp (ref "R48")
      (value "1k4")
      (footprint "eagle-import:R0603")
      (libsource (lib "eagle-import") (part "resistor_R-EU_R0603"))
    )
    (comp (ref "R52")
      (value "1k")
      (footprint "eagle-import:R0603")
      (libsource (lib "eagle-import") (part "resistor_R-EU_R0603"))
    )
    (comp (ref "R53")
      (value "1k")
      (footprint "eagle-import:R0603")
      (libsource (lib "eagle-import") (part "resistor_R-EU_R0603"))
    )
    (comp (ref "R54")
      (value "2k")
      (footprint "eagle-import:R0603")
      (libsource (lib "eagle-import") (part "R-EU_R0603"))
    )
    (comp (ref "R55")
      (value "1k")
      (footprint "eagle-import:R0603")
      (libsource (lib "eagle-import") (part "resistor_R-EU_R0603"))
    )
    (comp (ref "TP9")
      (value "TPB1,27")
      (footprint "eagle-import:B1,27")
      (libsource (lib "eagle-import") (part "TPB1,27"))
    )
    (comp (ref "TP12")
      (value "TPB1,27")
      (footprint "eagle-import:B1,27")
      (libsource (lib "eagle-import") (part "TPB1,27"))
    )
    (comp (ref "C19")
      (value "100n")
      (footprint "eagle-import:C0402")
      (libsource (lib "eagle-import") (part "C-EUC0402"))
    )
    (comp (ref "C20")
      (value "10n")
      (footprint "eagle-import:C0402")
      (libsource (lib "eagle-import") (part "C-EUC0402"))
    )
    (comp (ref "C28")
      (value "470p")
      (footprint "eagle-import:C0603")
      (libsource (lib "eagle-import") (part "C-EUC0603"))
    )
    (comp (ref "C29")
      (value "10p")
      (footprint "eagle-import:C0603")
      (libsource (lib "eagle-import") (part "C-EUC0603"))
    )
    (comp (ref "C47")
      (value "10n")
      (footprint "eagle-import:C0402")
      (libsource (lib "eagle-import") (part "C-EUC0402"))
    )
    (comp (ref "C48")
      (value "100n")
      (footprint "eagle-import:C0402")
      (libsource (lib "eagle-import") (part "C-EUC0402"))
    )
    (comp (ref "C49")
      (value "10n")
      (footprint "eagle-import:C0402")
      (libsource (lib "eagle-import") (part "C-EUC0402"))
    )
    (comp (ref "C50")
      (value "100n")
      (footprint "eagle-import:C0402")
      (libsource (lib "eagle-import") (part "C-EUC0402"))
    )
    (comp (ref "C65")
      (value "470p")
      (footprint "eagle-import:C0603")
      (libsource (lib "eagle-import") (part "C-EUC0603"))
    )
    (comp (ref "C73")
      (value "10p")
      (footprint "eagle-import:C0603")
      (libsource (lib "eagle-import") (part "C-EUC0603"))
    )
    (comp (ref "C87")
      (value "100n")
      (footprint "eagle-import:C0402")
      (libsource (lib "eagle-import") (part "C-EUC0402"))
    )
    (comp (ref "C88")
      (value "10n")
      (footprint "eagle-import:C0402")
      (libsource (lib "eagle-import") (part "C-EUC0402"))
    )
    (comp (ref "C89")
      (value "100n")
      (footprint "eagle-import:C0402")
      (libsource (lib "eagle-import") (part "C-EUC0402"))
    )
    (comp (ref "C90")
      (value "10n")
      (footprint "eagle-import:C0402")
      (libsource (lib "eagle-import") (part "C-EUC0402"))
    )
    (comp (ref "D2")
      (value "BAS40")
      (footprint "eagle-import:SOT23")
      (libsource (lib "eagle-import") (part "BAS40"))
    )
    (comp (ref "D3")
      (value "BAS40")
      (footprint "eagle-import:SOT23")
      (libsource (lib "eagle-import") (part "BAS40"))
    )
    (comp (ref "D5")
      (value "BAS40")
      (footprint "eagle-import:SOT23")
      (libsource (lib "eagle-import") (part "BAS40"))
    )
    (comp (ref "D6")
      (value "BAS40")
      (footprint "eagle-import:SOT23")
      (libsource (lib "eagle-import") (part "BAS40"))
    )
    (comp (ref "IC4")
      (value "74AHC1G04DBV")
      (footprint "eagle-import:SOT23-5")
      (libsource (lib "eagle-import") (part "741G04DBVAHC"))
    )
    (comp (ref "IC7")
      (value "74AHC1G04DBV")
      (footprint "eagle-import:SOT23-5")
      (libsource (lib "eagle-import") (part "741G04DBVAHC"))
    )
    (comp (ref "IC9")
      (value "TLV272DGK")
      (footprint "eagle-import:MSOP8")
      (libsource (lib "eagle-import") (part "TLV272DGK"))
    )
    (comp (ref "IC13")
      (value "74AHC1G04DBV")
      (footprint "eagle-import:SOT23-5")
      (libsource (lib "eagle-import") (part "741G04DBVAHC"))
    )
    (comp (ref "IC16")
      (value "TLV272DGK")
      (footprint "eagle-import:MSOP8")
      (libsource (lib "eagle-import") (part "TLV272DGK"))
    )
    (comp (ref "Q1")
      (value "MMBTH81")
      (footprint "eagle-import:SOT23-BEC")
      (libsource (lib "eagle-import") (part "MMBTH81SMDLT1"))
    )
    (comp (ref "Q4")
      (value "MMBTH81")
      (footprint "eagle-import:SOT23-BEC")
      (libsource (lib "eagle-import") (part "MMBTH81SMDLT1"))
    )
    (comp (ref "R36")
      (value "470R")
      (footprint "eagle-import:R0603")
      (libsource (lib "eagle-import") (part "R-EU_R0603"))
    )
    (comp (ref "R37")
      (value "470R")
      (footprint "eagle-import:R0603")
      (libsource (lib "eagle-import") (part "R-EU_R0603"))
    )
    (comp (ref "R44")
      (value "100k")
      (footprint "eagle-import:R0603")
      (libsource (lib "eagle-import") (part "R-EU_R0603"))
    )
    (comp (ref "R45")
      (value "100k")
      (footprint "eagle-import:R0603")
      (libsource (lib "eagle-import") (part "R-EU_R0603"))
    )
    (comp (ref "R51")
      (value "470R")
      (footprint "eagle-import:R0603")
      (libsource (lib "eagle-import") (part "R-EU_R0603"))
    )
    (comp (ref "R68")
      (value "470R")
      (footprint "eagle-import:R0603")
      (libsource (lib "eagle-import") (part "R-EU_R0603"))
    )
    (comp (ref "R69")
      (value "100k")
      (footprint "eagle-import:R0603")
      (libsource (lib "eagle-import") (part "R-EU_R0603"))
    )
    (comp (ref "R70")
      (value "100k")
      (footprint "eagle-import:R0603")
      (libsource (lib "eagle-import") (part "R-EU_R0603"))
    )
    (comp (ref "T1")
      (value "MMBTH10")
      (footprint "eagle-import:SOT23-BEC")
      (libsource (lib "eagle-import") (part "-NPN-SOT23-BECMMBTH10LT1"))
    )
    (comp (ref "T7")
      (value "MMBTH10")
      (footprint "eagle-import:SOT23-BEC")
      (libsource (lib "eagle-import") (part "-NPN-SOT23-BECMMBTH10LT1"))
    )
    (comp (ref "C3")
      (value "1n")
      (footprint "eagle-import:C0603")
      (libsource (lib "eagle-import") (part "C-EUC0603"))
    )
    (comp (ref "C4")
      (value "1300p")
      (footprint "eagle-import:C0603")
      (libsource (lib "eagle-import") (part "C-EUC0603"))
    )
    (comp (ref "C14")
      (value "47u, 20V")
      (footprint "eagle-import:CT7343")
      (libsource (lib "eagle-import") (part "CPOL-EUCT7343"))
    )
    (comp (ref "C15")
      (value "47u, 20V")
      (footprint "eagle-import:CT7343")
      (libsource (lib "eagle-import") (part "CPOL-EUCT7343"))
    )
    (comp (ref "C16")
      (value "4u7")
      (footprint "eagle-import:C0805")
      (libsource (lib "eagle-import") (part "C-EUC0805"))
    )
    (comp (ref "C24")
      (value "100n")
      (footprint "eagle-import:C0603")
      (libsource (lib "eagle-import") (part "C-EUC0603"))
    )
    (comp (ref "C25")
      (value "15n")
      (footprint "eagle-import:C0603")
      (libsource (lib "eagle-import") (part "C-EUC0603"))
    )
    (comp (ref "C26")
      (value "220p")
      (footprint "eagle-import:C0603")
      (libsource (lib "eagle-import") (part "C-EUC0603"))
    )
    (comp (ref "C30")
      (value "47u, 20V")
      (footprint "eagle-import:CT7343")
      (libsource (lib "eagle-import") (part "CPOL-EUCT7343"))
    )
    (comp (ref "D1")
      (value "CDBA140SL-HF")
      (footprint "eagle-import:DO214AC")
      (libsource (lib "eagle-import") (part "DIODE-DO214AC"))
    )
    (comp (ref "IC3")
      (value "LT1534-1")
      (footprint "eagle-import:SO16")
      (libsource (lib "eagle-import") (part "LT1534"))
    )
    (comp (ref "L1")
      (value "25n")
      (footprint "eagle-import:R0603")
      (libsource (lib "eagle-import") (part "INDUCTOR0603"))
    )
    (comp (ref "L3")
      (value "SRF0703-820M")
      (footprint "eagle-import:SRF0703")
      (libsource (lib "eagle-import") (part "SRF0703"))
    )
    (comp (ref "L4")
      (value "SRF0703-820M")
      (footprint "eagle-import:SRF0703")
      (libsource (lib "eagle-import") (part "SRF0703"))
    )
    (comp (ref "R3")
      (value "DNP")
      (footprint "eagle-import:R0603")
      (libsource (lib "eagle-import") (part "resistor_R-EU_R0603"))
    )
    (comp (ref "R4")
      (value "0R")
      (footprint "eagle-import:R0603")
      (libsource (lib "eagle-import") (part "resistor_R-EU_R0603"))
    )
    (comp (ref "R5")
      (value "DNP")
      (footprint "eagle-import:R0603")
      (libsource (lib "eagle-import") (part "resistor_R-EU_R0603"))
    )
    (comp (ref "R6")
      (value "29k4")
      (footprint "eagle-import:R0603")
      (libsource (lib "eagle-import") (part "resistor_R-EU_R0603"))
    )
    (comp (ref "R7")
      (value "2k49")
      (footprint "eagle-import:R0603")
      (libsource (lib "eagle-import") (part "resistor_R-EU_R0603"))
    )
    (comp (ref "R8")
      (value "10R")
      (footprint "eagle-import:R0603")
      (libsource (lib "eagle-import") (part "resistor_R-EU_R0603"))
    )
    (comp (ref "R9")
      (value "16k9")
      (footprint "eagle-import:R0603")
      (libsource (lib "eagle-import") (part "resistor_R-EU_R0603"))
    )
    (comp (ref "R22")
      (value "1k")
      (footprint "eagle-import:R0603")
      (libsource (lib "eagle-import") (part "resistor_R-EU_R0603"))
    )
    (comp (ref "R23")
      (value "1k")
      (footprint "eagle-import:R0603")
      (libsource (lib "eagle-import") (part "resistor_R-EU_R0603"))
    )
    (comp (ref "R24")
      (value "6k8")
      (footprint "eagle-import:R0603")
      (libsource (lib "eagle-import") (part "resistor_R-EU_R0603"))
    )
    (comp (ref "TP3")
      (value "TPB1,27")
      (footprint "eagle-import:B1,27")
      (libsource (lib "eagle-import") (part "TPB1,27"))
    )
    (comp (ref "TP7")
      (value "TPB1,27")
      (footprint "eagle-import:B1,27")
      (libsource (lib "eagle-import") (part "TPB1,27"))
    )
    (comp (ref "C31")
      (value "47u, 20V")
      (footprint "eagle-import:CT7343")
      (libsource (lib "eagle-import") (part "CPOL-EUCT7343"))
    )
    (comp (ref "C82")
      (value "100n")
      (footprint "eagle-import:C0603")
      (libsource (lib "eagle-import") (part "C-EUC0603"))
    )
    (comp (ref "C86")
      (value "100n")
      (footprint "eagle-import:C0402")
      (libsource (lib "eagle-import") (part "C-EUC0402"))
    )
    (comp (ref "C93")
      (value "10n")
      (footprint "eagle-import:C0402")
      (libsource (lib "eagle-import") (part "C-EUC0402"))
    )
    (comp (ref "C94")
      (value "47p")
      (footprint "eagle-import:C0402")
      (libsource (lib "eagle-import") (part "C-EUC0402"))
    )
    (comp (ref "C97")
      (value "47p")
      (footprint "eagle-import:C0402")
      (libsource (lib "eagle-import") (part "C-EUC0402"))
    )
    (comp (ref "C101")
      (value "10n")
      (footprint "eagle-import:C0603")
      (libsource (lib "eagle-import") (part "C-EUC0603"))
    )
    (comp (ref "C103")
      (value "100n")
      (footprint "eagle-import:C0603")
      (libsource (lib "eagle-import") (part "C-EUC0603"))
    )
    (comp (ref "C104")
      (value "100n")
      (footprint "eagle-import:C0603")
      (libsource (lib "eagle-import") (part "C-EUC0603"))
    )
    (comp (ref "C105")
      (value "4u7")
      (footprint "eagle-import:C0603")
      (libsource (lib "eagle-import") (part "C-EUC0603"))
    )
    (comp (ref "H1")
      (value "MOUNT-PAD-ROUND3.2")
      (footprint "eagle-import:3,2-PAD")
      (libsource (lib "eagle-import") (part "MOUNT-PAD-ROUND3.2"))
    )
    (comp (ref "H2")
      (value "MOUNT-PAD-ROUND3.2")
      (footprint "eagle-import:3,2-PAD")
      (libsource (lib "eagle-import") (part "MOUNT-PAD-ROUND3.2"))
    )
    (comp (ref "H3")
      (value "MOUNT-PAD-ROUND3.2")
      (footprint "eagle-import:3,2-PAD")
      (libsource (lib "eagle-import") (part "MOUNT-PAD-ROUND3.2"))
    )
    (comp (ref "H4")
      (value "MOUNT-PAD-ROUND3.2")
      (footprint "eagle-import:3,2-PAD")
      (libsource (lib "eagle-import") (part "MOUNT-PAD-ROUND3.2"))
    )
    (comp (ref "IC18")
      (value "USBLC6-2SC6Y")
      (footprint "eagle-import:SOT23-6L")
      (libsource (lib "eagle-import") (part "USBLC6"))
    )
    (comp (ref "IC24")
      (value "LM1117")
      (footprint "eagle-import:SOT-223")
      (libsource (lib "eagle-import") (part "LM1117"))
    )
    (comp (ref "L9")
      (value "MI0805J102R-10")
      (footprint "eagle-import:R0805")
      (libsource (lib "eagle-import") (part "INDUCTOR0805"))
    )
    (comp (ref "L11")
      (value "MI0805J102R-10")
      (footprint "eagle-import:R0805")
      (libsource (lib "eagle-import") (part "INDUCTOR0805"))
    )
    (comp (ref "Q6")
      (value "IRLML6402TRPBF")
      (footprint "eagle-import:SOT23-WIDE")
      (libsource (lib "eagle-import") (part "MOSFET-PWIDE"))
    )
    (comp (ref "R66")
      (value "4k7")
      (footprint "eagle-import:R0603")
      (libsource (lib "eagle-import") (part "resistor_R-EU_R0603"))
    )
    (comp (ref "R67")
      (value "100k")
      (footprint "eagle-import:R0603")
      (libsource (lib "eagle-import") (part "resistor_R-EU_R0603"))
    )
    (comp (ref "R76")
      (value "22R")
      (footprint "eagle-import:R0402")
      (libsource (lib "eagle-import") (part "resistor_R-EU_R0402"))
    )
    (comp (ref "R77")
      (value "22R")
      (footprint "eagle-import:R0402")
      (libsource (lib "eagle-import") (part "resistor_R-EU_R0402"))
    )
    (comp (ref "TP23")
      (value "TPTP15R")
      (footprint "eagle-import:TP15R")
      (libsource (lib "eagle-import") (part "TPTP15R"))
    )
    (comp (ref "X3")
      (value "KEYSTONE-7774")
      (footprint "eagle-import:KEYSTONE-7774")
      (libsource (lib "eagle-import") (part "KEYSTONE-7774"))
    )
    (comp (ref "X6")
      (value "KEYSTONE-7774")
      (footprint "eagle-import:KEYSTONE-7774")
      (libsource (lib "eagle-import") (part "KEYSTONE-7774"))
    )
    (comp (ref "X8")
      (value "PN61729-S")
      (footprint "eagle-import:PN61729-S")
      (libsource (lib "eagle-import") (part "PN61729-S"))
    )
    (comp (ref "C32")
      (value "100n")
      (footprint "eagle-import:C0402")
      (libsource (lib "eagle-import") (part "C-EUC0402"))
    )
    (comp (ref "C33")
      (value "10n")
      (footprint "eagle-import:C0402")
      (libsource (lib "eagle-import") (part "C-EUC0402"))
    )
    (comp (ref "C51")
      (value "10n")
      (footprint "eagle-import:C0402")
      (libsource (lib "eagle-import") (part "C-EUC0402"))
    )
    (comp (ref "C54")
      (value "100n")
      (footprint "eagle-import:C0402")
      (libsource (lib "eagle-import") (part "C-EUC0402"))
    )
    (comp (ref "C62")
      (value "10n")
      (footprint "eagle-import:C0402")
      (libsource (lib "eagle-import") (part "C-EUC0402"))
    )
    (comp (ref "C63")
      (value "100n")
      (footprint "eagle-import:C0402")
      (libsource (lib "eagle-import") (part "C-EUC0402"))
    )
    (comp (ref "C66")
      (value "470p")
      (footprint "eagle-import:C0603")
      (libsource (lib "eagle-import") (part "C-EUC0603"))
    )
    (comp (ref "C74")
      (value "10n")
      (footprint "eagle-import:C0402")
      (libsource (lib "eagle-import") (part "C-EUC0402"))
    )
    (comp (ref "C75")
      (value "100n")
      (footprint "eagle-import:C0402")
      (libsource (lib "eagle-import") (part "C-EUC0402"))
    )
    (comp (ref "C76")
      (value "4u7")
      (footprint "eagle-import:C0603")
      (libsource (lib "eagle-import") (part "C-EUC0603"))
    )
    (comp (ref "C77")
      (value "10n")
      (footprint "eagle-import:C0402")
      (libsource (lib "eagle-import") (part "C-EUC0402"))
    )
    (comp (ref "C80")
      (value "100n")
      (footprint "eagle-import:C0402")
      (libsource (lib "eagle-import") (part "C-EUC0402"))
    )
    (comp (ref "IC6")
      (value "DS1100LU-20+")
      (footprint "eagle-import:MSOP8")
      (libsource (lib "eagle-import") (part "DS1100L"))
    )
    (comp (ref "IC8")
      (value "NC7SV74K8X")
      (footprint "eagle-import:US8_3.1MM_JDEC_MO-187")
      (libsource (lib "eagle-import") (part "NC7SV74K8X"))
    )
    (comp (ref "IC12")
      (value "74AHC1G04DBV")
      (footprint "eagle-import:SOT23-5")
      (libsource (lib "eagle-import") (part "741G04DBVAHC"))
    )
    (comp (ref "IC14")
      (value "NC7WZ16P6X")
      (footprint "eagle-import:SC70-6L")
      (libsource (lib "eagle-import") (part "NC7WZ16P6X"))
    )
    (comp (ref "IC15")
      (value "LTC1711")
      (footprint "eagle-import:MSOP8")
      (libsource (lib "eagle-import") (part "LTC1711"))
    )
    (comp (ref "L8")
      (value "PE-0603FB601ST")
      (footprint "eagle-import:R0603")
      (libsource (lib "eagle-import") (part "INDUCTOR0603"))
    )
    (comp (ref "M1")
      (value "BSS806N")
      (footprint "eagle-import:SOT23R_INFINEON")
      (libsource (lib "eagle-import") (part "BSS806N"))
    )
    (comp (ref "R17")
      (value "DNP")
      (footprint "eagle-import:R0603")
      (libsource (lib "eagle-import") (part "R-EU_R0603"))
    )
    (comp (ref "R18")
      (value "DNP")
      (footprint "eagle-import:R0603")
      (libsource (lib "eagle-import") (part "R-EU_R0603"))
    )
    (comp (ref "R19")
      (value "DNP")
      (footprint "eagle-import:R0603")
      (libsource (lib "eagle-import") (part "R-EU_R0603"))
    )
    (comp (ref "R20")
      (value "DNP")
      (footprint "eagle-import:R0603")
      (libsource (lib "eagle-import") (part "R-EU_R0603"))
    )
    (comp (ref "R21")
      (value "DNP")
      (footprint "eagle-import:R0603")
      (libsource (lib "eagle-import") (part "R-EU_R0603"))
    )
    (comp (ref "R47")
      (value "1k")
      (footprint "eagle-import:R0603")
      (libsource (lib "eagle-import") (part "R-EU_R0603"))
    )
    (comp (ref "R58")
      (value "49R9")
      (footprint "eagle-import:R0603")
      (libsource (lib "eagle-import") (part "R-EU_R0603"))
    )
    (comp (ref "R61")
      (value "1k")
      (footprint "eagle-import:R0603")
      (libsource (lib "eagle-import") (part "R-EU_R0603"))
    )
    (comp (ref "R62")
      (value "10k")
      (footprint "eagle-import:R0603")
      (libsource (lib "eagle-import") (part "R-EU_R0603"))
    )
    (comp (ref "R63")
      (value "49R9")
      (footprint "eagle-import:R0603")
      (libsource (lib "eagle-import") (part "R-EU_R0603"))
    )
    (comp (ref "TP11")
      (value "TPTP06R")
      (footprint "eagle-import:TP06R")
      (libsource (lib "eagle-import") (part "TPTP06R"))
    )
    (comp (ref "TP13")
      (value "TPTP06R")
      (footprint "eagle-import:TP06R")
      (libsource (lib "eagle-import") (part "TPTP06R"))
    )
    (comp (ref "X2")
      (value "CONN_FORCE_QUENCH")
      (footprint "eagle-import:J502-ND-142-0711-871_876")
      (fields
        (field (name "MF") "JOHNSON COMPONENTS")
        (field (name "MPN") "142-0711-871")
        (field (name "MF_1") "JOHNSON COMPONENTS")
        (field (name "MPN_1") "142-0711-871")
        (field (name "OC_FARNELL") "unknown")
        (field (name "OC_NEWARK") "01C1639")
      )
      (libsource (lib "eagle-import") (part "SMA-142-0711-871/876"))
    )
    (comp (ref "X5")
      (value "CONN_PHOTON_COUNTER")
      (footprint "eagle-import:J502-ND-142-0711-871_876")
      (fields (field (name "MF") "JOHNSON COMPONENTS") (field (name "MPN") "142-0711-871"))
      (libsource (lib "eagle-import") (part "SMA-142-0711-871/876"))
    )
    (comp (ref "C5")
      (value "100n")
      (footprint "eagle-import:C0603")
      (libsource (lib "eagle-import") (part "C-EUC0603"))
    )
    (comp (ref "C17")
      (value "4u7")
      (footprint "eagle-import:C0603")
      (libsource (lib "eagle-import") (part "C-EUC0603"))
    )
    (comp (ref "C18")
      (value "100n")
      (footprint "eagle-import:C0603")
      (libsource (lib "eagle-import") (part "C-EUC0603"))
    )
    (comp (ref "C98")
      (value "100n")
      (footprint "eagle-import:C0603")
      (libsource (lib "eagle-import") (part "C-EUC0603"))
    )
    (comp (ref "C99")
      (value "4u7")
      (footprint "eagle-import:C0603")
      (libsource (lib "eagle-import") (part "C-EUC0603"))
    )
    (comp (ref "C106")
      (value "100n")
      (footprint "eagle-import:C0603")
      (libsource (lib "eagle-import") (part "C-EUC0603"))
    )
    (comp (ref "IC22")
      (value "MAX572X")
      (footprint "eagle-import:TSSOP20")
      (libsource (lib "eagle-import") (part "MAX572X"))
    )
    (comp (ref "L2")
      (value "PE-0603FB601ST")
      (footprint "eagle-import:R0603")
      (libsource (lib "eagle-import") (part "INDUCTOR0603"))
    )
    (comp (ref "L10")
      (value "PE-0603FB601ST")
      (footprint "eagle-import:R0603")
      (libsource (lib "eagle-import") (part "INDUCTOR0603"))
    )
    (comp (ref "R10")
      (value "2k2")
      (footprint "eagle-import:R0603")
      (libsource (lib "eagle-import") (part "R-EU_R0603"))
    )
    (comp (ref "R11")
      (value "2k2")
      (footprint "eagle-import:R0603")
      (libsource (lib "eagle-import") (part "R-EU_R0603"))
    )
    (comp (ref "R82")
      (value "0R")
      (footprint "eagle-import:R0603")
      (libsource (lib "eagle-import") (part "R-EU_R0603"))
    )
    (comp (ref "TP1")
      (value "GND")
      (footprint "eagle-import:KEYSTONE_5000_MINIATURE")
      (libsource (lib "eagle-import") (part "KEYSTONE_5000"))
    )
    (comp (ref "TP6")
      (value "VREF_AV_DET")
      (footprint "eagle-import:KEYSTONE_5000_MINIATURE")
      (libsource (lib "eagle-import") (part "KEYSTONE_5000"))
    )
    (comp (ref "TP14")
      (value "CASC_IBIAS")
      (footprint "eagle-import:KEYSTONE_5000_MINIATURE")
      (libsource (lib "eagle-import") (part "KEYSTONE_5000"))
    )
    (comp (ref "TP15")
      (value "DMND_IBIAS")
      (footprint "eagle-import:KEYSTONE_5000_MINIATURE")
      (libsource (lib "eagle-import") (part "KEYSTONE_5000"))
    )
    (comp (ref "TP16")
      (value "ONE_SHOT")
      (footprint "eagle-import:KEYSTONE_5000_MINIATURE")
      (libsource (lib "eagle-import") (part "KEYSTONE_5000"))
    )
    (comp (ref "TP17")
      (value "SLEW_UP")
      (footprint "eagle-import:KEYSTONE_5000_MINIATURE")
      (libsource (lib "eagle-import") (part "KEYSTONE_5000"))
    )
    (comp (ref "TP18")
      (value "SLEW_DN")
      (footprint "eagle-import:KEYSTONE_5000_MINIATURE")
      (libsource (lib "eagle-import") (part "KEYSTONE_5000"))
    )
    (comp (ref "TP19")
      (value "SLEW_MAX")
      (footprint "eagle-import:KEYSTONE_5000_MINIATURE")
      (libsource (lib "eagle-import") (part "KEYSTONE_5000"))
    )
    (comp (ref "TP20")
      (value "DELAY_UP")
      (footprint "eagle-import:KEYSTONE_5000_MINIATURE")
      (libsource (lib "eagle-import") (part "KEYSTONE_5000"))
    )
    (comp (ref "TP21")
      (value "DELAY_DN")
      (footprint "eagle-import:KEYSTONE_5000_MINIATURE")
      (libsource (lib "eagle-import") (part "KEYSTONE_5000"))
    )
    (comp (ref "TP22")
      (value "GND")
      (footprint "eagle-import:KEYSTONE_5000_MINIATURE")
      (libsource (lib "eagle-import") (part "KEYSTONE_5000"))
    )
    (comp (ref "U1")
      (value "MCP4725")
      (footprint "eagle-import:SOT23-6")
      (libsource (lib "eagle-import") (part "DAC_MCP4725"))
    )
    (comp (ref "C21")
      (value "10n")
      (footprint "eagle-import:C0402")
      (libsource (lib "eagle-import") (part "C-EUC0402"))
    )
    (comp (ref "C22")
      (value "10n")
      (footprint "eagle-import:C0402")
      (libsource (lib "eagle-import") (part "C-EUC0402"))
    )
    (comp (ref "C23")
      (value "10n")
      (footprint "eagle-import:C0402")
      (libsource (lib "eagle-import") (part "C-EUC0402"))
    )
    (comp (ref "C27")
      (value "100n")
      (footprint "eagle-import:C0402")
      (libsource (lib "eagle-import") (part "C-EUC0402"))
    )
    (comp (ref "C34")
      (value "100n")
      (footprint "eagle-import:C0402")
      (libsource (lib "eagle-import") (part "C-EUC0402"))
    )
    (comp (ref "C35")
      (value "100n")
      (footprint "eagle-import:C0402")
      (libsource (lib "eagle-import") (part "C-EUC0402"))
    )
    (comp (ref "C36")
      (value "1n")
      (footprint "eagle-import:C0603")
      (libsource (lib "eagle-import") (part "C-EUC0603"))
    )
    (comp (ref "C37")
      (value "100n")
      (footprint "eagle-import:C0402")
      (libsource (lib "eagle-import") (part "C-EUC0402"))
    )
    (comp (ref "C38")
      (value "100n")
      (footprint "eagle-import:C0402")
      (libsource (lib "eagle-import") (part "C-EUC0402"))
    )
    (comp (ref "C39")
      (value "10n")
      (footprint "eagle-import:C0402")
      (libsource (lib "eagle-import") (part "C-EUC0402"))
    )
    (comp (ref "C42")
      (value "10n")
      (footprint "eagle-import:C0402")
      (libsource (lib "eagle-import") (part "C-EUC0402"))
    )
    (comp (ref "IC5")
      (value "ADCMP582")
      (footprint "eagle-import:QFN50P300X300X80-16N")
      (libsource (lib "eagle-import") (part "ADCMP582"))
    )
    (comp (ref "R14")
      (value "100R")
      (footprint "eagle-import:R0603")
      (libsource (lib "eagle-import") (part "R-EU_R0603"))
    )
    (comp (ref "R15")
      (value "DNP")
      (footprint "eagle-import:R0603")
      (libsource (lib "eagle-import") (part "R-EU_R0603"))
    )
    (comp (ref "R16")
      (value "49R9")
      (footprint "eagle-import:R0603")
      (libsource (lib "eagle-import") (part "R-EU_R0603"))
    )
    (comp (ref "R25")
      (value "150R")
      (footprint "eagle-import:R0402")
      (libsource (lib "eagle-import") (part "R-EU_R0402"))
    )
    (comp (ref "R29")
      (value "150R")
      (footprint "eagle-import:R0402")
      (libsource (lib "eagle-import") (part "R-EU_R0402"))
    )
    (comp (ref "R30")
      (value "100R")
      (footprint "eagle-import:R0402")
      (libsource (lib "eagle-import") (part "R-EU_R0402"))
    )
    (comp (ref "R39")
      (value "10k")
      (footprint "eagle-import:R0603")
      (libsource (lib "eagle-import") (part "R-EU_R0603"))
    )
    (comp (ref "U2")
      (value "SN65EPT22DGK")
      (footprint "eagle-import:SOP65P490X110-8N")
      (libsource (lib "eagle-import") (part "SN65EPT22DGK"))
    )
    (comp (ref "U3")
      (value "SN65EPT21DGK")
      (footprint "eagle-import:SOP65P490X110-8N")
      (libsource (lib "eagle-import") (part "SN65EPT21DGK"))
    )
    (comp (ref "C111")
      (value "100n")
      (footprint "eagle-import:C0603")
      (libsource (lib "eagle-import") (part "C-EUC0603"))
    )
    (comp (ref "IC19")
      (value "ALD1107")
      (footprint "eagle-import:SO14")
      (libsource (lib "eagle-import") (part "ALD1107"))
    )
    (comp (ref "IC20")
      (value "ALD1106")
      (footprint "eagle-import:SO14")
      (libsource (lib "eagle-import") (part "ALD1106"))
    )
    (comp (ref "IC23")
      (value "TLV271DBV")
      (footprint "eagle-import:SOT23-5")
      (libsource (lib "eagle-import") (part "TLV271DBV"))
    )
    (comp (ref "R80")
      (value "SOT-DIV23LF-03-1001-1001-BB")
      (footprint "eagle-import:SOT23C")
      (libsource (lib "eagle-import") (part "DIVIDER_SOT23-5"))
    )
    (comp (ref "C1")
      (value "10n")
      (footprint "eagle-import:C0603")
      (libsource (lib "eagle-import") (part "C-EUC0603"))
    )
    (comp (ref "C2")
      (value "10n")
      (footprint "eagle-import:C0603")
      (libsource (lib "eagle-import") (part "C-EUC0603"))
    )
    (comp (ref "C6")
      (value "10n")
      (footprint "eagle-import:C0603")
      (libsource (lib "eagle-import") (part "C-EUC0603"))
    )
    (comp (ref "C7")
      (value "10n")
      (footprint "eagle-import:C0603")
      (libsource (lib "eagle-import") (part "C-EUC0603"))
    )
    (comp (ref "C8")
      (value "100n")
      (footprint "eagle-import:C0603")
      (libsource (lib "eagle-import") (part "C-EUC0603"))
    )
    (comp (ref "C9")
      (value "100n")
      (footprint "eagle-import:C0603")
      (libsource (lib "eagle-import") (part "C-EUC0603"))
    )
    (comp (ref "C10")
      (value "100n")
      (footprint "eagle-import:C0603")
      (libsource (lib "eagle-import") (part "C-EUC0603"))
    )
    (comp (ref "C11")
      (value "100n")
      (footprint "eagle-import:C0603")
      (libsource (lib "eagle-import") (part "C-EUC0603"))
    )
    (comp (ref "C12")
      (value "10u")
      (footprint "eagle-import:C0805")
      (libsource (lib "eagle-import") (part "C-EUC0805"))
    )
    (comp (ref "C13")
      (value "10u")
      (footprint "eagle-import:C0805")
      (libsource (lib "eagle-import") (part "C-EUC0805"))
    )
    (comp (ref "C44")
      (value "10u")
      (footprint "eagle-import:C0805")
      (libsource (lib "eagle-import") (part "C-EUC0805"))
    )
    (comp (ref "C45")
      (value "10n")
      (footprint "eagle-import:C0603")
      (libsource (lib "eagle-import") (part "C-EUC0603"))
    )
    (comp (ref "C52")
      (value "100n")
      (footprint "eagle-import:C0603")
      (libsource (lib "eagle-import") (part "C-EUC0603"))
    )
    (comp (ref "C58")
      (value "100n")
      (footprint "eagle-import:C0603")
      (libsource (lib "eagle-import") (part "C-EUC0603"))
    )
    (comp (ref "C59")
      (value "10n")
      (footprint "eagle-import:C0603")
      (libsource (lib "eagle-import") (part "C-EUC0603"))
    )
    (comp (ref "IC1")
      (value "TPS7A4901")
      (footprint "eagle-import:MSOP-8_POWER_PAD")
      (libsource (lib "eagle-import") (part "TPS7A"))
    )
    (comp (ref "IC2")
      (value "TPS7A4901")
      (footprint "eagle-import:MSOP-8_POWER_PAD")
      (libsource (lib "eagle-import") (part "TPS7A"))
    )
    (comp (ref "IC10")
      (value "TPS7A3001")
      (footprint "eagle-import:MSOP-8_POWER_PAD")
      (libsource (lib "eagle-import") (part "TPS7A"))
    )
    (comp (ref "R1")
      (value "24k")
      (footprint "eagle-import:R0603")
      (libsource (lib "eagle-import") (part "resistor_R-EU_R0603"))
    )
    (comp (ref "R2")
      (value "11k8")
      (footprint "eagle-import:R0603")
      (libsource (lib "eagle-import") (part "resistor_R-EU_R0603"))
    )
    (comp (ref "R12")
      (value "76k8")
      (footprint "eagle-import:R0603")
      (libsource (lib "eagle-import") (part "resistor_R-EU_R0603"))
    )
    (comp (ref "R13")
      (value "137k")
      (footprint "eagle-import:R0603")
      (libsource (lib "eagle-import") (part "resistor_R-EU_R0603"))
    )
    (comp (ref "R38")
      (value "76k8")
      (footprint "eagle-import:R0603")
      (libsource (lib "eagle-import") (part "resistor_R-EU_R0603"))
    )
    (comp (ref "R40")
      (value "24k")
      (footprint "eagle-import:R0603")
      (libsource (lib "eagle-import") (part "resistor_R-EU_R0603"))
    )
    (comp (ref "TP2")
      (value "TPTP15R")
      (footprint "eagle-import:TP15R")
      (libsource (lib "eagle-import") (part "TPTP15R"))
    )
    (comp (ref "TP4")
      (value "TPTP15R")
      (footprint "eagle-import:TP15R")
      (libsource (lib "eagle-import") (part "TPTP15R"))
    )
    (comp (ref "TP5")
      (value "TPTP15R")
      (footprint "eagle-import:TP15R")
      (libsource (lib "eagle-import") (part "TPTP15R"))
    )
    (comp (ref "TP8")
      (value "TPTP15R")
      (footprint "eagle-import:TP15R")
      (libsource (lib "eagle-import") (part "TPTP15R"))
    )
    (comp (ref "C78")
      (value "10n")
      (footprint "eagle-import:C0603")
      (libsource (lib "eagle-import") (part "C-EUC0603"))
    )
    (comp (ref "C79")
      (value "4u7")
      (footprint "eagle-import:C0603")
      (libsource (lib "eagle-import") (part "C-EUC0603"))
    )
    (comp (ref "C81")
      (value "4u7")
      (footprint "eagle-import:C0603")
      (libsource (lib "eagle-import") (part "C-EUC0603"))
    )
    (comp (ref "C84")
      (value "100n")
      (footprint "eagle-import:C0603")
      (libsource (lib "eagle-import") (part "C-EUC0603"))
    )
    (comp (ref "C85")
      (value "100n")
      (footprint "eagle-import:C0603")
      (libsource (lib "eagle-import") (part "C-EUC0603"))
    )
    (comp (ref "C91")
      (value "100n")
      (footprint "eagle-import:C0603")
      (libsource (lib "eagle-import") (part "C-EUC0603"))
    )
    (comp (ref "C92")
      (value "100n")
      (footprint "eagle-import:C0603")
      (libsource (lib "eagle-import") (part "C-EUC0603"))
    )
    (comp (ref "C100")
      (value "100n")
      (footprint "eagle-import:C0603")
      (libsource (lib "eagle-import") (part "C-EUC0603"))
    )
    (comp (ref "C102")
      (value "100n")
      (footprint "eagle-import:C0603")
      (libsource (lib "eagle-import") (part "C-EUC0603"))
    )
    (comp (ref "C107")
      (value "100n")
      (footprint "eagle-import:C0603")
      (libsource (lib "eagle-import") (part "C-EUC0603"))
    )
    (comp (ref "C108")
      (value "100n")
      (footprint "eagle-import:C0603")
      (libsource (lib "eagle-import") (part "C-EUC0603"))
    )
    (comp (ref "C109")
      (value "100n")
      (footprint "eagle-import:C0603")
      (libsource (lib "eagle-import") (part "C-EUC0603"))
    )
    (comp (ref "IC21")
      (value "STM32F411RE")
      (footprint "eagle-import:TQFP64_STM32")
      (libsource (lib "eagle-import") (part "STM32F405RG"))
    )
    (comp (ref "L7")
      (value "PE-0603FB601ST")
      (footprint "eagle-import:R0603")
      (libsource (lib "eagle-import") (part "INDUCTOR0603"))
    )
    (comp (ref "LED1")
      (value "LEDCHIP-LED0805")
      (footprint "eagle-import:CHIP-LED0805")
      (libsource (lib "eagle-import") (part "LEDCHIP-LED0805"))
    )
    (comp (ref "LED2")
      (value "LEDCHIP-LED0805")
      (footprint "eagle-import:CHIP-LED0805")
      (libsource (lib "eagle-import") (part "LEDCHIP-LED0805"))
    )
    (comp (ref "PROG")
      (value "JST_VERT")
      (footprint "eagle-import:JST-6-SMD-VERT-1.0MM")
      (libsource (lib "eagle-import") (part "JST_VERTICAL"))
    )
    (comp (ref "R71")
      (value "470R")
      (footprint "eagle-import:R0603")
      (libsource (lib "eagle-import") (part "resistor_R-EU_R0603"))
    )
    (comp (ref "R72")
      (value "470R")
      (footprint "eagle-import:R0603")
      (libsource (lib "eagle-import") (part "resistor_R-EU_R0603"))
    )
    (comp (ref "R74")
      (value "DNP")
      (footprint "eagle-import:R0603")
      (libsource (lib "eagle-import") (part "resistor_R-EU_R0603"))
    )
    (comp (ref "R75")
      (value "DNP")
      (footprint "eagle-import:R0603")
      (libsource (lib "eagle-import") (part "resistor_R-EU_R0603"))
    )
    (comp (ref "R78")
      (value "0R")
      (footprint "eagle-import:R0603")
      (libsource (lib "eagle-import") (part "resistor_R-EU_R0603"))
    )
    (comp (ref "R79")
      (value "DNP")
      (footprint "eagle-import:R0603")
      (libsource (lib "eagle-import") (part "resistor_R-EU_R0603"))
    )
    (comp (ref "SW1")
      (value "MCU_RST")
      (footprint "eagle-import:E-SWITCH-TL3305AF160QG")
      (libsource (lib "eagle-import") (part "E-SWITCH-TL3305AF160QG"))
    )
    (comp (ref "XTAL1")
      (value "CSTCE8M00G15L99-R0")
      (footprint "eagle-import:CSTCE_G15L_CSTCE_GH5L")
      (libsource (lib "eagle-import") (part "MURATA_CSTCE_G15L/CSTCE_GH5L"))
    )
    (comp (ref "C43")
      (value "100n")
      (footprint "eagle-import:C0603")
      (libsource (lib "eagle-import") (part "C-EUC0603"))
    )
    (comp (ref "C55")
      (value "100n")
      (footprint "eagle-import:C0603")
      (libsource (lib "eagle-import") (part "C-EUC0603"))
    )
    (comp (ref "C56")
      (value "10n")
      (footprint "eagle-import:C0603")
      (libsource (lib "eagle-import") (part "C-EUC0603"))
    )
    (comp (ref "C57")
      (value "10n")
      (footprint "eagle-import:C0603")
      (libsource (lib "eagle-import") (part "C-EUC0603"))
    )
    (comp (ref "C64")
      (value "100n")
      (footprint "eagle-import:C0603")
      (libsource (lib "eagle-import") (part "C-EUC0603"))
    )
    (comp (ref "C71")
      (value "100n")
      (footprint "eagle-import:C0603")
      (libsource (lib "eagle-import") (part "C-EUC0603"))
    )
    (comp (ref "C72")
      (value "10n")
      (footprint "eagle-import:C0603")
      (libsource (lib "eagle-import") (part "C-EUC0603"))
    )
    (comp (ref "C83")
      (value "47u, 20V")
      (footprint "eagle-import:CT7343")
      (libsource (lib "eagle-import") (part "CPOL-EUCT7343"))
    )
    (comp (ref "C95")
      (value "100n")
      (footprint "eagle-import:C0603")
      (libsource (lib "eagle-import") (part "C-EUC0603"))
    )
    (comp (ref "C96")
      (value "100n")
      (footprint "eagle-import:C0603")
      (libsource (lib "eagle-import") (part "C-EUC0603"))
    )
    (comp (ref "C110")
      (value "100n")
      (footprint "eagle-import:C0603")
      (libsource (lib "eagle-import") (part "C-EUC0603"))
    )
    (comp (ref "D7")
      (value "BAS40")
      (footprint "eagle-import:SOT23")
      (libsource (lib "eagle-import") (part "BAS40"))
    )
    (comp (ref "D8")
      (value "BAS40")
      (footprint "eagle-import:SOT23")
      (libsource (lib "eagle-import") (part "BAS40"))
    )
    (comp (ref "IC17")
      (value "TLV271DBV")
      (footprint "eagle-import:SOT23-5")
      (libsource (lib "eagle-import") (part "TLV271DBV"))
    )
    (comp (ref "M2")
      (value "BSS806N")
      (footprint "eagle-import:SOT23R_INFINEON")
      (libsource (lib "eagle-import") (part "BSS806N"))
    )
    (comp (ref "M3")
      (value "BSS806N")
      (footprint "eagle-import:SOT23R_INFINEON")
      (libsource (lib "eagle-import") (part "BSS806N"))
    )
    (comp (ref "Q2")
      (value "MMBTH81")
      (footprint "eagle-import:SOT23-BEC")
      (libsource (lib "eagle-import") (part "MMBTH81SMDLT1"))
    )
    (comp (ref "Q3")
      (value "MMBTH81")
      (footprint "eagle-import:SOT23-BEC")
      (libsource (lib "eagle-import") (part "MMBTH81SMDLT1"))
    )
    (comp (ref "Q5")
      (value "MMBTH81")
      (footprint "eagle-import:SOT23-BEC")
      (libsource (lib "eagle-import") (part "MMBTH81SMDLT1"))
    )
    (comp (ref "R26")
      (value "DNP")
      (footprint "eagle-import:R0603")
      (libsource (lib "eagle-import") (part "R-EU_R0603"))
    )
    (comp (ref "R27")
      (value "DNP")
      (footprint "eagle-import:R0603")
      (libsource (lib "eagle-import") (part "R-EU_R0603"))
    )
    (comp (ref "R28")
      (value "0R")
      (footprint "eagle-import:R0603")
      (libsource (lib "eagle-import") (part "R-EU_R0603"))
    )
    (comp (ref "R31")
      (value "DNP")
      (footprint "eagle-import:R0603")
      (libsource (lib "eagle-import") (part "R-EU_R0603"))
    )
    (comp (ref "R32")
      (value "1k")
      (footprint "eagle-import:R0603")
      (libsource (lib "eagle-import") (part "R-EU_R0603"))
    )
    (comp (ref "R33")
      (value "0R")
      (footprint "eagle-import:R0603")
      (libsource (lib "eagle-import") (part "R-EU_R0603"))
    )
    (comp (ref "R41")
      (value "49R9")
      (footprint "eagle-import:R0603")
      (libsource (lib "eagle-import") (part "R-EU_R0603"))
    )
    (comp (ref "R42")
      (value "DNP")
      (footprint "eagle-import:R0603")
      (libsource (lib "eagle-import") (part "R-EU_R0603"))
    )
    (comp (ref "R43")
      (value "200R")
      (footprint "eagle-import:R0603")
      (libsource (lib "eagle-import") (part "R-EU_R0603"))
    )
    (comp (ref "R46")
      (value "100R")
      (footprint "eagle-import:R0603")
      (libsource (lib "eagle-import") (part "R-EU_R0603"))
    )
    (comp (ref "R49")
      (value "100R")
      (footprint "eagle-import:R0603")
      (libsource (lib "eagle-import") (part "R-EU_R0603"))
    )
    (comp (ref "R50")
      (value "49R9")
      (footprint "eagle-import:R0603")
      (libsource (lib "eagle-import") (part "R-EU_R0603"))
    )
    (comp (ref "R56")
      (value "220R")
      (footprint "eagle-import:R0603")
      (libsource (lib "eagle-import") (part "R-EU_R0603"))
    )
    (comp (ref "R57")
      (value "DNP")
      (footprint "eagle-import:R0603")
      (libsource (lib "eagle-import") (part "R-EU_R0603"))
    )
    (comp (ref "R59")
      (value "200R")
      (footprint "eagle-import:R0603")
      (libsource (lib "eagle-import") (part "R-EU_R0603"))
    )
    (comp (ref "R60")
      (value "0R")
      (footprint "eagle-import:R0603")
      (libsource (lib "eagle-import") (part "R-EU_R0603"))
    )
    (comp (ref "R64")
      (value "470R")
      (footprint "eagle-import:R0603")
      (libsource (lib "eagle-import") (part "R-EU_R0603"))
    )
    (comp (ref "R65")
      (value "220R")
      (footprint "eagle-import:R0603")
      (libsource (lib "eagle-import") (part "R-EU_R0603"))
    )
    (comp (ref "R73")
      (value "100k")
      (footprint "eagle-import:R0603")
      (libsource (lib "eagle-import") (part "R-EU_R0603"))
    )
    (comp (ref "R81")
      (value "100k")
      (footprint "eagle-import:R0603")
      (libsource (lib "eagle-import") (part "R-EU_R0603"))
    )
    (comp (ref "R83")
      (value "100R")
      (footprint "eagle-import:R0603")
      (libsource (lib "eagle-import") (part "R-EU_R0603"))
    )
    (comp (ref "R84")
      (value "100R")
      (footprint "eagle-import:R0603")
      (libsource (lib "eagle-import") (part "R-EU_R0603"))
    )
    (comp (ref "RLY1")
      (value "CRF05-1A")
      (footprint "eagle-import:MEDER_RELAY_CRF")
      (libsource (lib "eagle-import") (part "MEDER_CRF05-1A"))
    )
    (comp (ref "RLY2")
      (value "CRF05-1A")
      (footprint "eagle-import:MEDER_RELAY_CRF")
      (libsource (lib "eagle-import") (part "MEDER_CRF05-1A"))
    )
    (comp (ref "T2")
      (value "MMBTH10")
      (footprint "eagle-import:SOT23-BEC")
      (libsource (lib "eagle-import") (part "-NPN-SOT23-BECMMBTH10LT1"))
    )
    (comp (ref "T3")
      (value "MMBTH10")
      (footprint "eagle-import:SOT23-BEC")
      (libsource (lib "eagle-import") (part "-NPN-SOT23-BECMMBTH10LT1"))
    )
    (comp (ref "T4")
      (value "MMBTH10")
      (footprint "eagle-import:SOT23-BEC")
      (libsource (lib "eagle-import") (part "-NPN-SOT23-BECMMBTH10LT1"))
    )
    (comp (ref "T5")
      (value "MMBTH10")
      (footprint "eagle-import:SOT23-BEC")
      (libsource (lib "eagle-import") (part "-NPN-SOT23-BECMMBTH10LT1"))
    )
    (comp (ref "T6")
      (value "MMBTH10")
      (footprint "eagle-import:SOT23-BEC")
      (libsource (lib "eagle-import") (part "-NPN-SOT23-BECMMBTH10LT1"))
    )
    (comp (ref "TP10")
      (value "TP_VSCOPE")
      (footprint "eagle-import:JOHNSON-129-0701-30X")
      (libsource (lib "eagle-import") (part "TP-SCOPE_H"))
    )
    (comp (ref "X1")
      (value "CONN_PULLDN_SENSE")
      (footprint "eagle-import:J502-ND-142-0711-871_876")
      (fields
        (field (name "MF") "JOHNSON COMPONENTS")
        (field (name "MPN") "142-0711-871")
        (field (name "MF_1") "JOHNSON COMPONENTS")
        (field (name "MPN_1") "142-0711-871")
        (field (name "OC_FARNELL") "unknown")
        (field (name "OC_NEWARK") "01C1639")
      )
      (libsource (lib "eagle-import") (part "SMA-142-0711-871/876"))
    )
    (comp (ref "X4")
      (value "CONN_SPAD")
      (footprint "eagle-import:J502-ND-142-0711-871_876")
      (fields (field (name "MF") "JOHNSON COMPONENTS") (field (name "MPN") "142-0711-871"))
      (libsource (lib "eagle-import") (part "SMA-142-0711-871/876"))
    )
    (comp (ref "X7")
      (value "CONN_SMU")
      (footprint "eagle-import:J502-ND-142-0711-871_876")
      (fields (field (name "MF") "JOHNSON COMPONENTS") (field (name "MPN") "142-0711-871"))
      (libsource (lib "eagle-import") (part "SMA-142-0711-871/876"))
    )
  )
  (nets
    (net (code "1") (name "BLANKING_LATCH_EN") (class "Default")
      (node (ref "IC4") (pin "4") (pinfunction "O_4") (pintype "output"))
      (node (ref "R17") (pin "1") (pinfunction "1_1") (pintype "passive"))
      (node (ref "R18") (pin "1") (pinfunction "1_1") (pintype "passive"))
      (node (ref "R19") (pin "1") (pinfunction "1_1") (pintype "passive"))
      (node (ref "R20") (pin "1") (pinfunction "1_1") (pintype "passive"))
      (node (ref "R21") (pin "1") (pinfunction "1_1") (pintype "passive"))
      (node (ref "U2") (pin "7") (pinfunction "D0_7") (pintype "input"))
    )
    (net (code "2") (name "COMP_LE_N") (class "Default")
      (node (ref "IC5") (pin "6") (pinfunction "~{LE}_6") (pintype "bidirectional"))
      (node (ref "U2") (pin "1") (pinfunction "Q0_1") (pintype "output"))
    )
    (net (code "3") (name "COMP_LE_P") (class "Default")
      (node (ref "IC5") (pin "7") (pinfunction "LE_7") (pintype "bidirectional"))
      (node (ref "U2") (pin "2") (pinfunction "~{Q0}_2") (pintype "output"))
    )
    (net (code "4") (name "COMP_Q_N") (class "Default")
      (node (ref "IC5") (pin "10") (pinfunction "~{Q}_10") (pintype "bidirectional"))
      (node (ref "R25") (pin "1") (pinfunction "1_1") (pintype "passive"))
      (node (ref "R30") (pin "1") (pinfunction "1_1") (pintype "passive"))
      (node (ref "U3") (pin "3") (pinfunction "~{D}_3") (pintype "input"))
    )
    (net (code "5") (name "COMP_Q_P") (class "Default")
      (node (ref "IC5") (pin "11") (pinfunction "Q_11") (pintype "bidirectional"))
      (node (ref "R29") (pin "1") (pinfunction "1_1") (pintype "passive"))
      (node (ref "R30") (pin "2") (pinfunction "2_2") (pintype "passive"))
      (node (ref "U3") (pin "2") (pinfunction "D_2") (pintype "input"))
    )
    (net (code "6") (name "DAC1_CSB") (class "Default")
      (node (ref "IC21") (pin "50") (pinfunction "PA15/JTDI_50") (pintype "bidirectional"))
      (node (ref "IC22") (pin "15") (pinfunction "CSB_15") (pintype "bidirectional"))
    )
    (net (code "7") (name "DAC1_DIN") (class "Default")
      (node (ref "IC21") (pin "53") (pinfunction "PC12/SDIO_CLK_53") (pintype "bidirectional"))
      (node (ref "IC22") (pin "13") (pinfunction "DIN_13") (pintype "bidirectional"))
    )
    (net (code "8") (name "DAC1_DOUT") (class "Default")
      (node (ref "IC21") (pin "52") (pinfunction "PC11/SDIO_D3_52") (pintype "bidirectional"))
      (node (ref "IC22") (pin "12") (pinfunction "DOUT_12") (pintype "bidirectional"))
    )
    (net (code "9") (name "DAC1_SCLK") (class "Default")
      (node (ref "IC21") (pin "51") (pinfunction "PC10/SDIO_D2_51") (pintype "bidirectional"))
      (node (ref "IC22") (pin "14") (pinfunction "SCLK_14") (pintype "bidirectional"))
    )
    (net (code "10") (name "DAC1_~{CLR}") (class "Default")
      (node (ref "IC21") (pin "54") (pinfunction "PD2/SDIO_CMD_54") (pintype "bidirectional"))
      (node (ref "IC22") (pin "17") (pinfunction "~{CLR}_17") (pintype "bidirectional"))
    )
    (net (code "11") (name "DAC2_ADDRSEL") (class "Default")
      (node (ref "IC21") (pin "57") (pinfunction "PB5_57") (pintype "bidirectional"))
      (node (ref "U1") (pin "6") (pinfunction "A0_6") (pintype "input"))
    )
    (net (code "12") (name "DAC2_SCL") (class "Default")
      (node (ref "IC21") (pin "58") (pinfunction "PB6/I2C1_SCL_58") (pintype "bidirectional"))
      (node (ref "R11") (pin "2") (pinfunction "2_2") (pintype "passive"))
      (node (ref "U1") (pin "5") (pinfunction "SCL_5") (pintype "bidirectional"))
    )
    (net (code "13") (name "DAC2_SDA") (class "Default")
      (node (ref "IC21") (pin "59") (pinfunction "PB7/I2C1_SDA_59") (pintype "bidirectional"))
      (node (ref "R10") (pin "2") (pinfunction "2_2") (pintype "passive"))
      (node (ref "U1") (pin "4") (pinfunction "SDA_4") (pintype "bidirectional"))
    )
    (net (code "14") (name "DELAY_CAP") (class "Default")
      (node (ref "C29") (pin "1") (pinfunction "1_1") (pintype "passive"))
      (node (ref "IC4") (pin "2") (pinfunction "I_2") (pintype "input"))
      (node (ref "IC7") (pin "4") (pinfunction "O_4") (pintype "output"))
    )
    (net (code "15") (name "DIAMOND_IBIAS_NMOS") (class "Default")
      (node (ref "C57") (pin "2") (pinfunction "2_2") (pintype "passive"))
      (node (ref "IC20") (pin "5") (pinfunction "D_5") (pintype "bidirectional"))
      (node (ref "Q3") (pin "B") (pinfunction "B_B") (pintype "passive"))
      (node (ref "R43") (pin "1") (pinfunction "1_1") (pintype "passive"))
    )
    (net (code "16") (name "DIAMOND_IBIAS_PMOS") (class "Default")
      (node (ref "C57") (pin "1") (pinfunction "1_1") (pintype "passive"))
      (node (ref "IC19") (pin "5") (pinfunction "D_5") (pintype "bidirectional"))
      (node (ref "R59") (pin "2") (pinfunction "2_2") (pintype "passive"))
      (node (ref "T3") (pin "B") (pinfunction "B_B") (pintype "passive"))
    )
    (net (code "17") (name "FORCE_QUENCH") (class "Default")
      (node (ref "IC12") (pin "2") (pinfunction "I_2") (pintype "input"))
      (node (ref "R58") (pin "2") (pinfunction "2_2") (pintype "passive"))
      (node (ref "X2") (pin "1") (pinfunction "1_1") (pintype "passive"))
    )
    (net (code "18") (name "GND") (class "Default")
      (node (ref "C1") (pin "2") (pinfunction "2_2") (pintype "passive"))
      (node (ref "C10") (pin "2") (pinfunction "2_2") (pintype "passive"))
      (node (ref "C100") (pin "2") (pinfunction "2_2") (pintype "passive"))
      (node (ref "C101") (pin "2") (pinfunction "2_2") (pintype "passive"))
      (node (ref "C102") (pin "2") (pinfunction "2_2") (pintype "passive"))
      (node (ref "C103") (pin "2") (pinfunction "2_2") (pintype "passive"))
      (node (ref "C104") (pin "2") (pinfunction "2_2") (pintype "passive"))
      (node (ref "C105") (pin "2") (pinfunction "2_2") (pintype "passive"))
      (node (ref "C106") (pin "2") (pinfunction "2_2") (pintype "passive"))
      (node (ref "C107") (pin "2") (pinfunction "2_2") (pintype "passive"))
      (node (ref "C108") (pin "2") (pinfunction "2_2") (pintype "passive"))
      (node (ref "C109") (pin "2") (pinfunction "2_2") (pintype "passive"))
      (node (ref "C11") (pin "2") (pinfunction "2_2") (pintype "passive"))
      (node (ref "C110") (pin "2") (pinfunction "2_2") (pintype "passive"))
      (node (ref "C111") (pin "2") (pinfunction "2_2") (pintype "passive"))
      (node (ref "C12") (pin "2") (pinfunction "2_2") (pintype "passive"))
      (node (ref "C13") (pin "2") (pinfunction "2_2") (pintype "passive"))
      (node (ref "C14") (pin "-") (pinfunction "-_-") (pintype "passive"))
      (node (ref "C15") (pin "-") (pinfunction "-_-") (pintype "passive"))
      (node (ref "C16") (pin "2") (pinfunction "2_2") (pintype "passive"))
      (node (ref "C17") (pin "2") (pinfunction "2_2") (pintype "passive"))
      (node (ref "C18") (pin "2") (pinfunction "2_2") (pintype "passive"))
      (node (ref "C19") (pin "2") (pinfunction "2_2") (pintype "passive"))
      (node (ref "C2") (pin "2") (pinfunction "2_2") (pintype "passive"))
      (node (ref "C20") (pin "2") (pinfunction "2_2") (pintype "passive"))
      (node (ref "C21") (pin "2") (pinfunction "2_2") (pintype "passive"))
      (node (ref "C22") (pin "2") (pinfunction "2_2") (pintype "passive"))
      (node (ref "C23") (pin "2") (pinfunction "2_2") (pintype "passive"))
      (node (ref "C24") (pin "2") (pinfunction "2_2") (pintype "passive"))
      (node (ref "C25") (pin "2") (pinfunction "2_2") (pintype "passive"))
      (node (ref "C26") (pin "2") (pinfunction "2_2") (pintype "passive"))
      (node (ref "C27") (pin "2") (pinfunction "2_2") (pintype "passive"))
      (node (ref "C28") (pin "2") (pinfunction "2_2") (pintype "passive"))
      (node (ref "C29") (pin "2") (pinfunction "2_2") (pintype "passive"))
      (node (ref "C3") (pin "1") (pinfunction "1_1") (pintype "passive"))
      (node (ref "C30") (pin "-") (pinfunction "-_-") (pintype "passive"))
      (node (ref "C31") (pin "-") (pinfunction "-_-") (pintype "passive"))
      (node (ref "C32") (pin "2") (pinfunction "2_2") (pintype "passive"))
      (node (ref "C33") (pin "2") (pinfunction "2_2") (pintype "passive"))
      (node (ref "C34") (pin "2") (pinfunction "2_2") (pintype "passive"))
      (node (ref "C35") (pin "2") (pinfunction "2_2") (pintype "passive"))
      (node (ref "C36") (pin "2") (pinfunction "2_2") (pintype "passive"))
      (node (ref "C37") (pin "2") (pinfunction "2_2") (pintype "passive"))
      (node (ref "C38") (pin "2") (pinfunction "2_2") (pintype "passive"))
      (node (ref "C39") (pin "2") (pinfunction "2_2") (pintype "passive"))
      (node (ref "C4") (pin "2") (pinfunction "2_2") (pintype "passive"))
      (node (ref "C40") (pin "2") (pinfunction "2_2") (pintype "passive"))
      (node (ref "C41") (pin "2") (pinfunction "2_2") (pintype "passive"))
      (node (ref "C42") (pin "2") (pinfunction "2_2") (pintype "passive"))
      (node (ref "C43") (pin "2") (pinfunction "2_2") (pintype "passive"))
      (node (ref "C44") (pin "2") (pinfunction "2_2") (pintype "passive"))
      (node (ref "C47") (pin "2") (pinfunction "2_2") (pintype "passive"))
      (node (ref "C48") (pin "2") (pinfunction "2_2") (pintype "passive"))
      (node (ref "C49") (pin "2") (pinfunction "2_2") (pintype "passive"))
      (node (ref "C5") (pin "2") (pinfunction "2_2") (pintype "passive"))
      (node (ref "C50") (pin "2") (pinfunction "2_2") (pintype "passive"))
      (node (ref "C51") (pin "2") (pinfunction "2_2") (pintype "passive"))
      (node (ref "C52") (pin "2") (pinfunction "2_2") (pintype "passive"))
      (node (ref "C53") (pin "2") (pinfunction "2_2") (pintype "passive"))
      (node (ref "C54") (pin "2") (pinfunction "2_2") (pintype "passive"))
      (node (ref "C55") (pin "2") (pinfunction "2_2") (pintype "passive"))
      (node (ref "C58") (pin "2") (pinfunction "2_2") (pintype "passive"))
      (node (ref "C59") (pin "2") (pinfunction "2_2") (pintype "passive"))
      (node (ref "C60") (pin "2") (pinfunction "2_2") (pintype "passive"))
      (node (ref "C61") (pin "2") (pinfunction "2_2") (pintype "passive"))
      (node (ref "C62") (pin "2") (pinfunction "2_2") (pintype "passive"))
      (node (ref "C63") (pin "2") (pinfunction "2_2") (pintype "passive"))
      (node (ref "C64") (pin "2") (pinfunction "2_2") (pintype "passive"))
      (node (ref "C65") (pin "2") (pinfunction "2_2") (pintype "passive"))
      (node (ref "C66") (pin "2") (pinfunction "2_2") (pintype "passive"))
      (node (ref "C67") (pin "2") (pinfunction "2_2") (pintype "passive"))
      (node (ref "C68") (pin "2") (pinfunction "2_2") (pintype "passive"))
      (node (ref "C69") (pin "2") (pinfunction "2_2") (pintype "passive"))
      (node (ref "C70") (pin "2") (pinfunction "2_2") (pintype "passive"))
      (node (ref "C71") (pin "2") (pinfunction "2_2") (pintype "passive"))
      (node (ref "C72") (pin "2") (pinfunction "2_2") (pintype "passive"))
      (node (ref "C73") (pin "2") (pinfunction "2_2") (pintype "passive"))
      (node (ref "C74") (pin "2") (pinfunction "2_2") (pintype "passive"))
      (node (ref "C75") (pin "2") (pinfunction "2_2") (pintype "passive"))
      (node (ref "C76") (pin "2") (pinfunction "2_2") (pintype "passive"))
      (node (ref "C77") (pin "2") (pinfunction "2_2") (pintype "passive"))
      (node (ref "C78") (pin "2") (pinfunction "2_2") (pintype "passive"))
      (node (ref "C79") (pin "2") (pinfunction "2_2") (pintype "passive"))
      (node (ref "C8") (pin "2") (pinfunction "2_2") (pintype "passive"))
      (node (ref "C80") (pin "2") (pinfunction "2_2") (pintype "passive"))
      (node (ref "C81") (pin "2") (pinfunction "2_2") (pintype "passive"))
      (node (ref "C83") (pin "-") (pinfunction "-_-") (pintype "passive"))
      (node (ref "C84") (pin "2") (pinfunction "2_2") (pintype "passive"))
      (node (ref "C85") (pin "2") (pinfunction "2_2") (pintype "passive"))
      (node (ref "C86") (pin "2") (pinfunction "2_2") (pintype "passive"))
      (node (ref "C87") (pin "2") (pinfunction "2_2") (pintype "passive"))
      (node (ref "C88") (pin "2") (pinfunction "2_2") (pintype "passive"))
      (node (ref "C89") (pin "2") (pinfunction "2_2") (pintype "passive"))
      (node (ref "C9") (pin "2") (pinfunction "2_2") (pintype "passive"))
      (node (ref "C90") (pin "2") (pinfunction "2_2") (pintype "passive"))
      (node (ref "C91") (pin "2") (pinfunction "2_2") (pintype "passive"))
      (node (ref "C92") (pin "2") (pinfunction "2_2") (pintype "passive"))
      (node (ref "C93") (pin "2") (pinfunction "2_2") (pintype "passive"))
      (node (ref "C94") (pin "2") (pinfunction "2_2") (pintype "passive"))
      (node (ref "C95") (pin "2") (pinfunction "2_2") (pintype "passive"))
      (node (ref "C96") (pin "2") (pinfunction "2_2") (pintype "passive"))
      (node (ref "C97") (pin "2") (pinfunction "2_2") (pintype "passive"))
      (node (ref "C98") (pin "2") (pinfunction "2_2") (pintype "passive"))
      (node (ref "C99") (pin "2") (pinfunction "2_2") (pintype "passive"))
      (node (ref "D3") (pin "1") (pinfunction "A_1") (pintype "passive"))
      (node (ref "D4") (pin "C") (pinfunction "C_C") (pintype "passive"))
      (node (ref "D6") (pin "1") (pinfunction "A_1") (pintype "passive"))
      (node (ref "H1") (pin "B3,2") (pinfunction "MOUNT_B3,2") (pintype "passive"))
      (node (ref "H2") (pin "B3,2") (pinfunction "MOUNT_B3,2") (pintype "passive"))
      (node (ref "H3") (pin "B3,2") (pinfunction "MOUNT_B3,2") (pintype "passive"))
      (node (ref "H4") (pin "B3,2") (pinfunction "MOUNT_B3,2") (pintype "passive"))
      (node (ref "IC1") (pin "4") (pinfunction "GND_4") (pintype "bidirectional"))
      (node (ref "IC1") (pin "PAD") (pinfunction "GND_PAD") (pintype "bidirectional"))
      (node (ref "IC10") (pin "4") (pinfunction "GND_4") (pintype "bidirectional"))
      (node (ref "IC10") (pin "PAD") (pinfunction "GND_PAD") (pintype "bidirectional"))
      (node (ref "IC11") (pin "1") (pinfunction "GND_1") (pintype "bidirectional"))
      (node (ref "IC11") (pin "16") (pinfunction "GND_16") (pintype "bidirectional"))
      (node (ref "IC11") (pin "8") (pinfunction "GND_8") (pintype "bidirectional"))
      (node (ref "IC11") (pin "9") (pinfunction "GND_9") (pintype "bidirectional"))
      (node (ref "IC12") (pin "3") (pinfunction "GND_3") (pintype "power_in"))
      (node (ref "IC14") (pin "2") (pinfunction "GND_2") (pintype "bidirectional"))
      (node (ref "IC15") (pin "4") (pinfunction "V-_4") (pintype "bidirectional"))
      (node (ref "IC15") (pin "5") (pinfunction "LEN_5") (pintype "bidirectional"))
      (node (ref "IC15") (pin "6") (pinfunction "GND_6") (pintype "bidirectional"))
      (node (ref "IC16") (pin "5") (pinfunction "+IN_5") (pintype "input"))
      (node (ref "IC17") (pin "3") (pinfunction "+IN_3") (pintype "input"))
      (node (ref "IC18") (pin "2") (pinfunction "GND_2") (pintype "bidirectional"))
      (node (ref "IC2") (pin "4") (pinfunction "GND_4") (pintype "bidirectional"))
      (node (ref "IC2") (pin "PAD") (pinfunction "GND_PAD") (pintype "bidirectional"))
      (node (ref "IC20") (pin "4") (pinfunction "SUBC_4") (pintype "bidirectional"))
      (node (ref "IC21") (pin "12") (pinfunction "VSSA_12") (pintype "bidirectional"))
      (node (ref "IC21") (pin "18") (pinfunction "VSS1_18") (pintype "bidirectional"))
      (node (ref "IC21") (pin "63") (pinfunction "VSS2_63") (pintype "bidirectional"))
      (node (ref "IC22") (pin "19") (pinfunction "GND_19") (pintype "bidirectional"))
      (node (ref "IC22") (pin "20") (pinfunction "M/~{Z}_20") (pintype "bidirectional"))
      (node (ref "IC23") (pin "2") (pinfunction "V-_2") (pintype "power_in"))
      (node (ref "IC24") (pin "1") (pinfunction "GND_1") (pintype "bidirectional"))
      (node (ref "IC3") (pin "1") (pinfunction "GND_1") (pintype "bidirectional"))
      (node (ref "IC3") (pin "16") (pinfunction "GND_16") (pintype "bidirectional"))
      (node (ref "IC3") (pin "8") (pinfunction "GND_8") (pintype "bidirectional"))
      (node (ref "IC3") (pin "9") (pinfunction "GND_9") (pintype "bidirectional"))
      (node (ref "IC4") (pin "3") (pinfunction "GND_3") (pintype "power_in"))
      (node (ref "IC5") (pin "15") (pinfunction "GND_15") (pintype "bidirectional"))
      (node (ref "IC6") (pin "4") (pinfunction "GND_4") (pintype "bidirectional"))
      (node (ref "IC8") (pin "4") (pinfunction "GND_4") (pintype "bidirectional"))
      (node (ref "IC9") (pin "5") (pinfunction "+IN_5") (pintype "input"))
      (node (ref "L1") (pin "2") (pinfunction "P$2_2") (pintype "bidirectional"))
      (node (ref "L11") (pin "2") (pinfunction "P$2_2") (pintype "bidirectional"))
      (node (ref "L5") (pin "2") (pinfunction "P$2_2") (pintype "bidirectional"))
      (node (ref "LED1") (pin "C") (pinfunction "C_C") (pintype "passive"))
      (node (ref "LED2") (pin "C") (pinfunction "C_C") (pintype "passive"))
      (node (ref "M1") (pin "2") (pinfunction "S_2") (pintype "passive"))
      (node (ref "M2") (pin "2") (pinfunction "S_2") (pintype "passive"))
      (node (ref "M3") (pin "2") (pinfunction "S_2") (pintype "passive"))
      (node (ref "PROG") (pin "3") (pinfunction "3_3") (pintype "bidirectional"))
      (node (ref "Q5") (pin "C") (pinfunction "C_C") (pintype "passive"))
      (node (ref "R1") (pin "2") (pinfunction "2_2") (pintype "passive"))
      (node (ref "R15") (pin "1") (pinfunction "1_1") (pintype "passive"))
      (node (ref "R16") (pin "2") (pinfunction "2_2") (pintype "passive"))
      (node (ref "R2") (pin "2") (pinfunction "2_2") (pintype "passive"))
      (node (ref "R22") (pin "2") (pinfunction "2_2") (pintype "passive"))
      (node (ref "R23") (pin "2") (pinfunction "2_2") (pintype "passive"))
      (node (ref "R25") (pin "2") (pinfunction "2_2") (pintype "passive"))
      (node (ref "R27") (pin "1") (pinfunction "1_1") (pintype "passive"))
      (node (ref "R29") (pin "2") (pinfunction "2_2") (pintype "passive"))
      (node (ref "R31") (pin "1") (pinfunction "1_1") (pintype "passive"))
      (node (ref "R35") (pin "1") (pinfunction "1_1") (pintype "passive"))
      (node (ref "R40") (pin "2") (pinfunction "2_2") (pintype "passive"))
      (node (ref "R52") (pin "2") (pinfunction "2_2") (pintype "passive"))
      (node (ref "R53") (pin "2") (pinfunction "2_2") (pintype "passive"))
      (node (ref "R55") (pin "2") (pinfunction "2_2") (pintype "passive"))
      (node (ref "R58") (pin "1") (pinfunction "1_1") (pintype "passive"))
      (node (ref "R7") (pin "2") (pinfunction "2_2") (pintype "passive"))
      (node (ref "R78") (pin "2") (pinfunction "2_2") (pintype "passive"))
      (node (ref "R79") (pin "2") (pinfunction "2_2") (pintype "passive"))
      (node (ref "R80") (pin "3") (pinfunction "MIDDLE_3") (pintype "bidirectional"))
      (node (ref "R9") (pin "1") (pinfunction "1_1") (pintype "passive"))
      (node (ref "RLY1") (pin "1") (pinfunction "PIN1_1") (pintype "bidirectional"))
      (node (ref "RLY1") (pin "4") (pinfunction "PIN4_4") (pintype "bidirectional"))
      (node (ref "RLY1") (pin "6") (pinfunction "PIN6_6") (pintype "bidirectional"))
      (node (ref "RLY1") (pin "9") (pinfunction "PIN9_9") (pintype "bidirectional"))
      (node (ref "RLY2") (pin "1") (pinfunction "PIN1_1") (pintype "bidirectional"))
      (node (ref "RLY2") (pin "4") (pinfunction "PIN4_4") (pintype "bidirectional"))
      (node (ref "RLY2") (pin "6") (pinfunction "PIN6_6") (pintype "bidirectional"))
      (node (ref "RLY2") (pin "9") (pinfunction "PIN9_9") (pintype "bidirectional"))
      (node (ref "SW1") (pin "1") (pinfunction "P$1_1") (pintype "bidirectional"))
      (node (ref "SW1") (pin "2") (pinfunction "P$1_2") (pintype "bidirectional"))
      (node (ref "TP1") (pin "P$1") (pinfunction "P$1_P$1") (pintype "bidirectional"))
      (node (ref "TP10") (pin "GND1") (pinfunction "GND_GND1") (pintype "power_in"))
      (node (ref "TP10") (pin "GND2") (pinfunction "GND_GND2") (pintype "power_in"))
      (node (ref "TP22") (pin "P$1") (pinfunction "P$1_P$1") (pintype "bidirectional"))
      (node (ref "TP5") (pin "TP") (pinfunction "TP_TP") (pintype "input"))
      (node (ref "U1") (pin "2") (pinfunction "GND_2") (pintype "power_in"))
      (node (ref "U2") (pin "5") (pinfunction "GND_5") (pintype "passive"))
      (node (ref "U2") (pin "6") (pinfunction "D1_6") (pintype "input"))
      (node (ref "U3") (pin "5") (pinfunction "GND_5") (pintype "passive"))
      (node (ref "X1") (pin "G@1") (pinfunction "GND_G@1") (pintype "power_in"))
      (node (ref "X2") (pin "G@1") (pinfunction "GND_G@1") (pintype "power_in"))
      (node (ref "X3") (pin "1") (pinfunction "1_1") (pintype "bidirectional"))
      (node (ref "X3") (pin "2") (pinfunction "1_2") (pintype "bidirectional"))
      (node (ref "X3") (pin "3") (pinfunction "1_3") (pintype "bidirectional"))
      (node (ref "X3") (pin "4") (pinfunction "1_4") (pintype "bidirectional"))
      (node (ref "X4") (pin "G@1") (pinfunction "GND_G@1") (pintype "power_in"))
      (node (ref "X5") (pin "G@1") (pinfunction "GND_G@1") (pintype "power_in"))
      (node (ref "X6") (pin "1") (pinfunction "1_1") (pintype "bidirectional"))
      (node (ref "X6") (pin "2") (pinfunction "1_2") (pintype "bidirectional"))
      (node (ref "X6") (pin "3") (pinfunction "1_3") (pintype "bidirectional"))
      (node (ref "X6") (pin "4") (pinfunction "1_4") (pintype "bidirectional"))
      (node (ref "X7") (pin "G@1") (pinfunction "GND_G@1") (pintype "power_in"))
      (node (ref "X8") (pin "S1") (pinfunction "S1_S1") (pintype "passive"))
      (node (ref "X8") (pin "S2") (pinfunction "S2_S2") (pintype "passive"))
      (node (ref "XTAL1") (pin "2") (pinfunction "GND_2") (pintype "bidirectional"))
    )
    (net (code "19") (name "HOLDOFF_TRIG") (class "Default")
      (node (ref "IC8") (pin "1") (pinfunction "CLK_1") (pintype "bidirectional"))
      (node (ref "U3") (pin "7") (pinfunction "Q_7") (pintype "output"))
    )
    (net (code "20") (name "LDO_N10V0_FB_CH1") (class "Default")
      (node (ref "C45") (pin "2") (pinfunction "2_2") (pintype "passive"))
      (node (ref "IC10") (pin "2") (pinfunction "FB_2") (pintype "bidirectional"))
      (node (ref "R38") (pin "1") (pinfunction "1_1") (pintype "passive"))
      (node (ref "R40") (pin "1") (pinfunction "1_1") (pintype "passive"))
    )
    (net (code "21") (name "LDO_N10V0_NR_SS_CH1") (class "Default")
      (node (ref "C59") (pin "1") (pinfunction "1_1") (pintype "passive"))
      (node (ref "IC10") (pin "6") (pinfunction "NR/SS_6") (pintype "bidirectional"))
    )
    (net (code "22") (name "LDO_P5V0_FB_CH1") (class "Default")
      (node (ref "C6") (pin "2") (pinfunction "2_2") (pintype "passive"))
      (node (ref "IC1") (pin "2") (pinfunction "FB_2") (pintype "bidirectional"))
      (node (ref "R1") (pin "1") (pinfunction "1_1") (pintype "passive"))
      (node (ref "R12") (pin "1") (pinfunction "1_1") (pintype "passive"))
    )
    (net (code "23") (name "LDO_P5V0_NR_SS_CH1") (class "Default")
      (node (ref "C1") (pin "1") (pinfunction "1_1") (pintype "passive"))
      (node (ref "IC1") (pin "6") (pinfunction "NR/SS_6") (pintype "bidirectional"))
    )
    (net (code "24") (name "LDO_P10V0_FB_CH1") (class "Default")
      (node (ref "C7") (pin "2") (pinfunction "2_2") (pintype "passive"))
      (node (ref "IC2") (pin "2") (pinfunction "FB_2") (pintype "bidirectional"))
      (node (ref "R13") (pin "1") (pinfunction "1_1") (pintype "passive"))
      (node (ref "R2") (pin "1") (pinfunction "1_1") (pintype "passive"))
    )
    (net (code "25") (name "LDO_P10V0_NR_SS_CH1") (class "Default")
      (node (ref "C2") (pin "1") (pinfunction "1_1") (pintype "passive"))
      (node (ref "IC2") (pin "6") (pinfunction "NR/SS_6") (pintype "bidirectional"))
    )
    (net (code "26") (name "LOGIC_QUENCH") (class "Default")
      (node (ref "IC14") (pin "1") (pinfunction "IN1_1") (pintype "bidirectional"))
      (node (ref "IC14") (pin "3") (pinfunction "IN2_3") (pintype "bidirectional"))
      (node (ref "IC6") (pin "1") (pinfunction "IN_1") (pintype "bidirectional"))
      (node (ref "IC7") (pin "2") (pinfunction "I_2") (pintype "input"))
      (node (ref "IC8") (pin "5") (pinfunction "Q_5") (pintype "bidirectional"))
      (node (ref "R47") (pin "2") (pinfunction "2_2") (pintype "passive"))
      (node (ref "R57") (pin "2") (pinfunction "2_2") (pintype "passive"))
      (node (ref "TP13") (pin "TP") (pinfunction "TP_TP") (pintype "input"))
    )
    (net (code "27") (name "MCU_AQC_RLY") (class "Default")
      (node (ref "IC21") (pin "34") (pinfunction "PB13/I2S2_CK_34") (pintype "bidirectional"))
      (node (ref "R84") (pin "2") (pinfunction "2_2") (pintype "passive"))
    )
    (net (code "28") (name "MCU_BOOT0") (class "Default")
      (node (ref "IC21") (pin "60") (pinfunction "BOOT0_60") (pintype "bidirectional"))
      (node (ref "R74") (pin "2") (pinfunction "2_2") (pintype "passive"))
      (node (ref "R78") (pin "1") (pinfunction "1_1") (pintype "passive"))
    )
    (net (code "29") (name "MCU_BOOT1") (class "Default")
      (node (ref "IC21") (pin "28") (pinfunction "PB2-BOOT1_28") (pintype "bidirectional"))
      (node (ref "R75") (pin "2") (pinfunction "2_2") (pintype "passive"))
      (node (ref "R79") (pin "1") (pinfunction "1_1") (pintype "passive"))
    )
    (net (code "30") (name "MCU_IVTEST_RLY") (class "Default")
      (node (ref "IC21") (pin "33") (pinfunction "PB12/I2S2_WS_33") (pintype "bidirectional"))
      (node (ref "R83") (pin "2") (pinfunction "2_2") (pintype "passive"))
    )
    (net (code "31") (name "MCU_JTCK") (class "Default")
      (node (ref "IC21") (pin "49") (pinfunction "PA14/JTCK_49") (pintype "bidirectional"))
      (node (ref "PROG") (pin "2") (pinfunction "2_2") (pintype "bidirectional"))
    )
    (net (code "32") (name "MCU_JTDO") (class "Default")
      (node (ref "IC21") (pin "55") (pinfunction "PB3/JTDO_55") (pintype "bidirectional"))
      (node (ref "PROG") (pin "6") (pinfunction "6_6") (pintype "bidirectional"))
    )
    (net (code "33") (name "MCU_JTMS") (class "Default")
      (node (ref "IC21") (pin "46") (pinfunction "PA13/JTMS_46") (pintype "bidirectional"))
      (node (ref "PROG") (pin "4") (pinfunction "4_4") (pintype "bidirectional"))
    )
    (net (code "34") (name "MCU_LED1") (class "Default")
      (node (ref "IC21") (pin "8") (pinfunction "PC0_8") (pintype "bidirectional"))
      (node (ref "R72") (pin "2") (pinfunction "2_2") (pintype "passive"))
    )
    (net (code "35") (name "MCU_LED2") (class "Default")
      (node (ref "IC21") (pin "9") (pinfunction "PC1_9") (pintype "bidirectional"))
      (node (ref "R71") (pin "2") (pinfunction "2_2") (pintype "passive"))
    )
    (net (code "36") (name "MCU_NRST") (class "Default")
      (node (ref "C78") (pin "1") (pinfunction "1_1") (pintype "passive"))
      (node (ref "IC21") (pin "7") (pinfunction "NRST_7") (pintype "bidirectional"))
      (node (ref "PROG") (pin "5") (pinfunction "5_5") (pintype "bidirectional"))
      (node (ref "SW1") (pin "3") (pinfunction "P$2_3") (pintype "bidirectional"))
      (node (ref "SW1") (pin "4") (pinfunction "P$2_4") (pintype "bidirectional"))
    )
    (net (code "37") (name "MCU_OSC_IN") (class "Default")
      (node (ref "IC21") (pin "5") (pinfunction "PH0/OSC_IN_5") (pintype "bidirectional"))
      (node (ref "XTAL1") (pin "1") (pinfunction "LEFT_1") (pintype "bidirectional"))
    )
    (net (code "38") (name "MCU_OSC_OUT") (class "Default")
      (node (ref "IC21") (pin "6") (pinfunction "PH1/OSC_OUT_6") (pintype "bidirectional"))
      (node (ref "XTAL1") (pin "3") (pinfunction "RIGHT_3") (pintype "bidirectional"))
    )
    (net (code "39") (name "MCU_PB11") (class "Default")
      (node (ref "C100") (pin "1") (pinfunction "1_1") (pintype "passive"))
      (node (ref "IC21") (pin "30") (pinfunction "PB11_30") (pintype "bidirectional"))
    )
    (net (code "40") (name "MCU_USB_FS_D_N") (class "Default")
      (node (ref "C97") (pin "1") (pinfunction "1_1") (pintype "passive"))
      (node (ref "IC21") (pin "44") (pinfunction "PA11_44") (pintype "bidirectional"))
      (node (ref "R77") (pin "1") (pinfunction "1_1") (pintype "passive"))
    )
    (net (code "41") (name "MCU_USB_FS_D_P") (class "Default")
      (node (ref "C94") (pin "1") (pinfunction "1_1") (pintype "passive"))
      (node (ref "IC21") (pin "45") (pinfunction "PA12_45") (pintype "bidirectional"))
      (node (ref "R76") (pin "1") (pinfunction "1_1") (pintype "passive"))
    )
    (net (code "42") (name "MCU_VCAP_1") (class "Default")
      (node (ref "C102") (pin "1") (pinfunction "1_1") (pintype "passive"))
      (node (ref "IC21") (pin "31") (pinfunction "VCAP_1_31") (pintype "bidirectional"))
    )
    (net (code "43") (name "MCU_VCAP_2") (class "Default")
      (node (ref "C109") (pin "1") (pinfunction "1_1") (pintype "passive"))
      (node (ref "IC21") (pin "47") (pinfunction "VCAP_2_47") (pintype "bidirectional"))
    )
    (net (code "44") (name "NC_DAC1_IRQ") (class "Default")
      (node (ref "IC22") (pin "16") (pinfunction "~{IRQ}_16") (pintype "bidirectional"))
    )
    (net (code "45") (name "NC_IC15_V+") (class "Default")
      (node (ref "IC20") (pin "11") (pinfunction "NC_11") (pintype "bidirectional"))
    )
    (net (code "46") (name "NC_IC16_V-") (class "Default")
      (node (ref "IC19") (pin "4") (pinfunction "NC_4") (pintype "bidirectional"))
    )
    (net (code "47") (name "Net-(C3-Pad2)") (class "Default")
      (node (ref "C3") (pin "2") (pinfunction "2_2") (pintype "passive"))
      (node (ref "R8") (pin "2") (pinfunction "2_2") (pintype "passive"))
    )
    (net (code "48") (name "Net-(C14-Pad+)") (class "Default")
      (node (ref "C14") (pin "+") (pinfunction "+_+") (pintype "passive"))
      (node (ref "C15") (pin "+") (pinfunction "+_+") (pintype "passive"))
      (node (ref "D1") (pin "C") (pinfunction "C_C") (pintype "passive"))
      (node (ref "L3") (pin "1") (pinfunction "1_1") (pintype "bidirectional"))
      (node (ref "R3") (pin "1") (pinfunction "1_1") (pintype "passive"))
      (node (ref "R5") (pin "1") (pinfunction "1_1") (pintype "passive"))
    )
    (net (code "49") (name "Net-(C25-Pad1)") (class "Default")
      (node (ref "C25") (pin "1") (pinfunction "1_1") (pintype "passive"))
      (node (ref "R24") (pin "1") (pinfunction "1_1") (pintype "passive"))
    )
    (net (code "50") (name "Net-(C40-Pad1)") (class "Default")
      (node (ref "C40") (pin "1") (pinfunction "1_1") (pintype "passive"))
      (node (ref "R34") (pin "2") (pinfunction "2_2") (pintype "passive"))
    )
    (net (code "51") (name "Net-(C46-Pad-)") (class "Default")
      (node (ref "C46") (pin "-") (pinfunction "-_-") (pintype "passive"))
      (node (ref "C70") (pin "1") (pinfunction "1_1") (pintype "passive"))
      (node (ref "D4") (pin "A") (pinfunction "A_A") (pintype "passive"))
      (node (ref "L6") (pin "4") (pinfunction "4_4") (pintype "bidirectional"))
    )
    (net (code "52") (name "Net-(C56-Pad1)") (class "Default")
      (node (ref "C56") (pin "1") (pinfunction "1_1") (pintype "passive"))
      (node (ref "R49") (pin "2") (pinfunction "2_2") (pintype "passive"))
      (node (ref "T3") (pin "E") (pinfunction "E_E") (pintype "passive"))
    )
    (net (code "53") (name "Net-(C56-Pad2)") (class "Default")
      (node (ref "C56") (pin "2") (pinfunction "2_2") (pintype "passive"))
      (node (ref "Q3") (pin "E") (pinfunction "E_E") (pintype "passive"))
      (node (ref "R46") (pin "1") (pinfunction "1_1") (pintype "passive"))
    )
    (net (code "54") (name "Net-(C68-Pad1)") (class "Default")
      (node (ref "C68") (pin "1") (pinfunction "1_1") (pintype "passive"))
      (node (ref "R54") (pin "1") (pinfunction "1_1") (pintype "passive"))
    )
    (net (code "55") (name "Net-(D2-A)") (class "Default")
      (node (ref "D2") (pin "1") (pinfunction "A_1") (pintype "passive"))
      (node (ref "IC7") (pin "5") (pinfunction "VCC_5") (pintype "power_in"))
      (node (ref "Q1") (pin "C") (pinfunction "C_C") (pintype "passive"))
    )
    (net (code "56") (name "Net-(D3-C)") (class "Default")
      (node (ref "D3") (pin "3") (pinfunction "C_3") (pintype "passive"))
      (node (ref "IC7") (pin "3") (pinfunction "GND_3") (pintype "power_in"))
      (node (ref "T1") (pin "C") (pinfunction "C_C") (pintype "passive"))
    )
    (net (code "57") (name "Net-(D5-A)") (class "Default")
      (node (ref "D5") (pin "1") (pinfunction "A_1") (pintype "passive"))
      (node (ref "IC13") (pin "5") (pinfunction "VCC_5") (pintype "power_in"))
      (node (ref "Q4") (pin "C") (pinfunction "C_C") (pintype "passive"))
    )
    (net (code "58") (name "Net-(D6-C)") (class "Default")
      (node (ref "D6") (pin "3") (pinfunction "C_3") (pintype "passive"))
      (node (ref "IC13") (pin "3") (pinfunction "GND_3") (pintype "power_in"))
      (node (ref "T7") (pin "C") (pinfunction "C_C") (pintype "passive"))
    )
    (net (code "59") (name "Net-(D7-A)") (class "Default")
      (node (ref "D7") (pin "1") (pinfunction "A_1") (pintype "passive"))
      (node (ref "M2") (pin "3") (pinfunction "D_3") (pintype "passive"))
      (node (ref "RLY2") (pin "2") (pinfunction "PIN2_2") (pintype "bidirectional"))
    )
    (net (code "60") (name "Net-(D8-A)") (class "Default")
      (node (ref "D8") (pin "1") (pinfunction "A_1") (pintype "passive"))
      (node (ref "M3") (pin "3") (pinfunction "D_3") (pintype "passive"))
      (node (ref "RLY1") (pin "2") (pinfunction "PIN2_2") (pintype "bidirectional"))
    )
    (net (code "61") (name "Net-(IC3-COL)") (class "Default")
      (node (ref "D1") (pin "A") (pinfunction "A_A") (pintype "passive"))
      (node (ref "IC3") (pin "2") (pinfunction "COL_2") (pintype "bidirectional"))
      (node (ref "L4") (pin "4") (pinfunction "4_4") (pintype "bidirectional"))
      (node (ref "R8") (pin "1") (pinfunction "1_1") (pintype "passive"))
    )
    (net (code "62") (name "Net-(IC3-CT)") (class "Default")
      (node (ref "C4") (pin "1") (pinfunction "1_1") (pintype "passive"))
      (node (ref "IC3") (pin "5") (pinfunction "CT_5") (pintype "bidirectional"))
    )
    (net (code "63") (name "Net-(IC3-FB)") (class "Default")
      (node (ref "IC3") (pin "7") (pinfunction "FB_7") (pintype "bidirectional"))
      (node (ref "R6") (pin "1") (pinfunction "1_1") (pintype "passive"))
      (node (ref "R7") (pin "1") (pinfunction "1_1") (pintype "passive"))
    )
    (net (code "64") (name "Net-(IC3-PGND)") (class "Default")
      (node (ref "IC3") (pin "3") (pinfunction "PGND_3") (pintype "bidirectional"))
      (node (ref "L1") (pin "1") (pinfunction "P$1_1") (pintype "bidirectional"))
    )
    (net (code "65") (name "Net-(IC3-RCSL)") (class "Default")
      (node (ref "IC3") (pin "13") (pinfunction "RCSL_13") (pintype "bidirectional"))
      (node (ref "R23") (pin "1") (pinfunction "1_1") (pintype "passive"))
    )
    (net (code "66") (name "Net-(IC3-RT)") (class "Default")
      (node (ref "IC3") (pin "6") (pinfunction "RT_6") (pintype "bidirectional"))
      (node (ref "R9") (pin "2") (pinfunction "2_2") (pintype "passive"))
    )
    (net (code "67") (name "Net-(IC3-RVSL)") (class "Default")
      (node (ref "IC3") (pin "14") (pinfunction "RVSL_14") (pintype "bidirectional"))
      (node (ref "R22") (pin "1") (pinfunction "1_1") (pintype "passive"))
    )
    (net (code "68") (name "Net-(IC3-VC)") (class "Default")
      (node (ref "C26") (pin "1") (pinfunction "1_1") (pintype "passive"))
      (node (ref "IC3") (pin "11") (pinfunction "VC_11") (pintype "bidirectional"))
      (node (ref "R24") (pin "2") (pinfunction "2_2") (pintype "passive"))
    )
    (net (code "69") (name "Net-(IC5-HYS)") (class "Default")
      (node (ref "IC5") (pin "14") (pinfunction "HYS_14") (pintype "bidirectional"))
      (node (ref "R39") (pin "2") (pinfunction "2_2") (pintype "passive"))
    )
    (net (code "70") (name "Net-(IC5-VP)") (class "Default")
      (node (ref "C36") (pin "1") (pinfunction "1_1") (pintype "passive"))
      (node (ref "IC5") (pin "2") (pinfunction "VP_2") (pintype "bidirectional"))
      (node (ref "R14") (pin "1") (pinfunction "1_1") (pintype "passive"))
    )
    (net (code "71") (name "Net-(IC5-VTN)") (class "Default")
      (node (ref "IC5") (pin "4") (pinfunction "VTN_4") (pintype "bidirectional"))
      (node (ref "R15") (pin "2") (pinfunction "2_2") (pintype "passive"))
    )
    (net (code "72") (name "Net-(IC5-VTT)") (class "Default")
      (node (ref "IC5") (pin "8") (pinfunction "VTT_8") (pintype "bidirectional"))
      (node (ref "R16") (pin "1") (pinfunction "1_1") (pintype "passive"))
    )
    (net (code "73") (name "Net-(IC6-TAP1)") (class "Default")
      (node (ref "IC6") (pin "7") (pinfunction "TAP1_7") (pintype "bidirectional"))
      (node (ref "R21") (pin "2") (pinfunction "2_2") (pintype "passive"))
    )
    (net (code "74") (name "Net-(IC6-TAP2)") (class "Default")
      (node (ref "IC6") (pin "2") (pinfunction "TAP2_2") (pintype "bidirectional"))
      (node (ref "R17") (pin "2") (pinfunction "2_2") (pintype "passive"))
    )
    (net (code "75") (name "Net-(IC6-TAP3)") (class "Default")
      (node (ref "IC6") (pin "6") (pinfunction "TAP3_6") (pintype "bidirectional"))
      (node (ref "R19") (pin "2") (pinfunction "2_2") (pintype "passive"))
    )
    (net (code "76") (name "Net-(IC6-TAP4)") (class "Default")
      (node (ref "IC6") (pin "3") (pinfunction "TAP4_3") (pintype "bidirectional"))
      (node (ref "R18") (pin "2") (pinfunction "2_2") (pintype "passive"))
    )
    (net (code "77") (name "Net-(IC6-TAP5)") (class "Default")
      (node (ref "IC6") (pin "5") (pinfunction "TAP5_5") (pintype "bidirectional"))
      (node (ref "R20") (pin "2") (pinfunction "2_2") (pintype "passive"))
    )
    (net (code "78") (name "Net-(IC9A--IN)") (class "Default")
      (node (ref "IC9") (pin "2") (pinfunction "-IN_2") (pintype "input"))
      (node (ref "Q1") (pin "E") (pinfunction "E_E") (pintype "passive"))
      (node (ref "R37") (pin "1") (pinfunction "1_1") (pintype "passive"))
    )
    (net (code "79") (name "Net-(IC9A-OUT)") (class "Default")
      (node (ref "IC9") (pin "1") (pinfunction "OUT_1") (pintype "output"))
      (node (ref "Q1") (pin "B") (pinfunction "B_B") (pintype "passive"))
    )
    (net (code "80") (name "Net-(IC9B--IN)") (class "Default")
      (node (ref "IC9") (pin "6") (pinfunction "-IN_6") (pintype "input"))
      (node (ref "R44") (pin "2") (pinfunction "2_2") (pintype "passive"))
      (node (ref "R45") (pin "1") (pinfunction "1_1") (pintype "passive"))
    )
    (net (code "81") (name "Net-(IC9B-OUT)") (class "Default")
      (node (ref "IC9") (pin "7") (pinfunction "OUT_7") (pintype "output"))
      (node (ref "T1") (pin "B") (pinfunction "B_B") (pintype "passive"))
    )
    (net (code "82") (name "Net-(IC11-COL)") (class "Default")
      (node (ref "C46") (pin "+") (pinfunction "+_+") (pintype "passive"))
      (node (ref "IC11") (pin "2") (pinfunction "COL_2") (pintype "bidirectional"))
      (node (ref "L6") (pin "3") (pinfunction "3_3") (pintype "bidirectional"))
      (node (ref "R34") (pin "1") (pinfunction "1_1") (pintype "passive"))
    )
    (net (code "83") (name "Net-(IC11-CT)") (class "Default")
      (node (ref "C41") (pin "1") (pinfunction "1_1") (pintype "passive"))
      (node (ref "IC11") (pin "5") (pinfunction "CT_5") (pintype "bidirectional"))
    )
    (net (code "84") (name "Net-(IC11-NFB)") (class "Default")
      (node (ref "IC11") (pin "10") (pinfunction "NFB_10") (pintype "bidirectional"))
      (node (ref "R48") (pin "2") (pinfunction "2_2") (pintype "passive"))
      (node (ref "R55") (pin "1") (pinfunction "1_1") (pintype "passive"))
    )
    (net (code "85") (name "Net-(IC11-PGND)") (class "Default")
      (node (ref "IC11") (pin "3") (pinfunction "PGND_3") (pintype "bidirectional"))
      (node (ref "L5") (pin "1") (pinfunction "P$1_1") (pintype "bidirectional"))
    )
    (net (code "86") (name "Net-(IC11-RCSL)") (class "Default")
      (node (ref "IC11") (pin "13") (pinfunction "RCSL_13") (pintype "bidirectional"))
      (node (ref "R53") (pin "1") (pinfunction "1_1") (pintype "passive"))
    )
    (net (code "87") (name "Net-(IC11-RT)") (class "Default")
      (node (ref "IC11") (pin "6") (pinfunction "RT_6") (pintype "bidirectional"))
      (node (ref "R35") (pin "2") (pinfunction "2_2") (pintype "passive"))
    )
    (net (code "88") (name "Net-(IC11-RVSL)") (class "Default")
      (node (ref "IC11") (pin "14") (pinfunction "RVSL_14") (pintype "bidirectional"))
      (node (ref "R52") (pin "1") (pinfunction "1_1") (pintype "passive"))
    )
    (net (code "89") (name "Net-(IC11-VC)") (class "Default")
      (node (ref "C69") (pin "1") (pinfunction "1_1") (pintype "passive"))
      (node (ref "IC11") (pin "11") (pinfunction "VC_11") (pintype "bidirectional"))
      (node (ref "R54") (pin "2") (pinfunction "2_2") (pintype "passive"))
    )
    (net (code "90") (name "Net-(IC14-OUT1)") (class "Default")
      (node (ref "IC14") (pin "4") (pinfunction "OUT2_4") (pintype "bidirectional"))
      (node (ref "IC14") (pin "6") (pinfunction "OUT1_6") (pintype "bidirectional"))
      (node (ref "R63") (pin "2") (pinfunction "2_2") (pintype "passive"))
    )
    (net (code "91") (name "Net-(IC15-+IN)") (class "Default")
      (node (ref "IC15") (pin "2") (pinfunction "+IN_2") (pintype "bidirectional"))
      (node (ref "R61") (pin "1") (pinfunction "1_1") (pintype "passive"))
      (node (ref "R62") (pin "2") (pinfunction "2_2") (pintype "passive"))
    )
    (net (code "92") (name "Net-(IC15-V+)") (class "Default")
      (node (ref "C74") (pin "1") (pinfunction "1_1") (pintype "passive"))
      (node (ref "C75") (pin "1") (pinfunction "1_1") (pintype "passive"))
      (node (ref "C76") (pin "1") (pinfunction "1_1") (pintype "passive"))
      (node (ref "IC15") (pin "1") (pinfunction "V+_1") (pintype "bidirectional"))
      (node (ref "L8") (pin "2") (pinfunction "P$2_2") (pintype "bidirectional"))
    )
    (net (code "93") (name "Net-(IC16A--IN)") (class "Default")
      (node (ref "IC16") (pin "2") (pinfunction "-IN_2") (pintype "input"))
      (node (ref "Q4") (pin "E") (pinfunction "E_E") (pintype "passive"))
      (node (ref "R51") (pin "1") (pinfunction "1_1") (pintype "passive"))
    )
    (net (code "94") (name "Net-(IC16A-OUT)") (class "Default")
      (node (ref "IC16") (pin "1") (pinfunction "OUT_1") (pintype "output"))
      (node (ref "Q4") (pin "B") (pinfunction "B_B") (pintype "passive"))
    )
    (net (code "95") (name "Net-(IC16B--IN)") (class "Default")
      (node (ref "IC16") (pin "6") (pinfunction "-IN_6") (pintype "input"))
      (node (ref "R69") (pin "2") (pinfunction "2_2") (pintype "passive"))
      (node (ref "R70") (pin "1") (pinfunction "1_1") (pintype "passive"))
    )
    (net (code "96") (name "Net-(IC16B-OUT)") (class "Default")
      (node (ref "IC16") (pin "7") (pinfunction "OUT_7") (pintype "output"))
      (node (ref "T7") (pin "B") (pinfunction "B_B") (pintype "passive"))
    )
    (net (code "97") (name "Net-(IC17--IN)") (class "Default")
      (node (ref "IC17") (pin "4") (pinfunction "-IN_4") (pintype "input"))
      (node (ref "R73") (pin "2") (pinfunction "2_2") (pintype "passive"))
      (node (ref "R81") (pin "1") (pinfunction "1_1") (pintype "passive"))
    )
    (net (code "98") (name "Net-(IC17-OUT)") (class "Default")
      (node (ref "IC17") (pin "1") (pinfunction "OUT_1") (pintype "output"))
      (node (ref "T6") (pin "B") (pinfunction "B_B") (pintype "passive"))
    )
    (net (code "99") (name "Net-(IC19A-D)") (class "Default")
      (node (ref "IC19") (pin "1") (pinfunction "D_1") (pintype "bidirectional"))
      (node (ref "IC19") (pin "13") (pinfunction "G_13") (pintype "bidirectional"))
      (node (ref "IC19") (pin "2") (pinfunction "G_2") (pintype "bidirectional"))
      (node (ref "IC19") (pin "8") (pinfunction "S_8") (pintype "bidirectional"))
    )
    (net (code "100") (name "Net-(IC19B-D)") (class "Default")
      (node (ref "IC19") (pin "14") (pinfunction "D_14") (pintype "bidirectional"))
      (node (ref "IC19") (pin "7") (pinfunction "S_7") (pintype "bidirectional"))
    )
    (net (code "101") (name "Net-(IC19C-D)") (class "Default")
      (node (ref "IC19") (pin "10") (pinfunction "D_10") (pintype "bidirectional"))
      (node (ref "IC19") (pin "6") (pinfunction "G_6") (pintype "bidirectional"))
      (node (ref "IC19") (pin "9") (pinfunction "G_9") (pintype "bidirectional"))
      (node (ref "IC20") (pin "10") (pinfunction "D_10") (pintype "bidirectional"))
    )
    (net (code "102") (name "Net-(IC20A-D)") (class "Default")
      (node (ref "IC20") (pin "1") (pinfunction "D_1") (pintype "bidirectional"))
      (node (ref "IC20") (pin "8") (pinfunction "S_8") (pintype "bidirectional"))
    )
    (net (code "103") (name "Net-(IC20A-G)") (class "Default")
      (node (ref "IC20") (pin "13") (pinfunction "G_13") (pintype "bidirectional"))
      (node (ref "IC20") (pin "2") (pinfunction "G_2") (pintype "bidirectional"))
      (node (ref "IC23") (pin "1") (pinfunction "OUT_1") (pintype "output"))
    )
    (net (code "104") (name "Net-(IC20A-S)") (class "Default")
      (node (ref "IC20") (pin "3") (pinfunction "S_3") (pintype "bidirectional"))
      (node (ref "IC23") (pin "4") (pinfunction "-IN_4") (pintype "input"))
      (node (ref "R80") (pin "2") (pinfunction "TOP_2") (pintype "bidirectional"))
    )
    (net (code "105") (name "Net-(IC20B-D)") (class "Default")
      (node (ref "IC20") (pin "14") (pinfunction "D_14") (pintype "bidirectional"))
      (node (ref "IC20") (pin "7") (pinfunction "S_7") (pintype "bidirectional"))
    )
    (net (code "106") (name "Net-(IC20B-S)") (class "Default")
      (node (ref "IC20") (pin "12") (pinfunction "S_12") (pintype "bidirectional"))
      (node (ref "R80") (pin "1") (pinfunction "BOTTOM_1") (pintype "bidirectional"))
    )
    (net (code "107") (name "Net-(IC22-REF)") (class "Default")
      (node (ref "IC22") (pin "1") (pinfunction "REF_1") (pintype "bidirectional"))
      (node (ref "R82") (pin "2") (pinfunction "2_2") (pintype "passive"))
    )
    (net (code "108") (name "Net-(L3-Pad2)") (class "Default")
      (node (ref "L3") (pin "2") (pinfunction "2_2") (pintype "bidirectional"))
      (node (ref "L3") (pin "3") (pinfunction "3_3") (pintype "bidirectional"))
    )
    (net (code "109") (name "Net-(L4-Pad2)") (class "Default")
      (node (ref "L4") (pin "2") (pinfunction "2_2") (pintype "bidirectional"))
      (node (ref "L4") (pin "3") (pinfunction "3_3") (pintype "bidirectional"))
    )
    (net (code "110") (name "Net-(LED1-PadA)") (class "Default")
      (node (ref "LED1") (pin "A") (pinfunction "A_A") (pintype "passive"))
      (node (ref "R71") (pin "1") (pinfunction "1_1") (pintype "passive"))
    )
    (net (code "111") (name "Net-(LED2-PadA)") (class "Default")
      (node (ref "LED2") (pin "A") (pinfunction "A_A") (pintype "passive"))
      (node (ref "R72") (pin "1") (pinfunction "1_1") (pintype "passive"))
    )
    (net (code "112") (name "Net-(M2-G)") (class "Default")
      (node (ref "M2") (pin "1") (pinfunction "G_1") (pintype "passive"))
      (node (ref "R83") (pin "1") (pinfunction "1_1") (pintype "passive"))
    )
    (net (code "113") (name "Net-(M3-G)") (class "Default")
      (node (ref "M3") (pin "1") (pinfunction "G_1") (pintype "passive"))
      (node (ref "R84") (pin "1") (pinfunction "1_1") (pintype "passive"))
    )
    (net (code "114") (name "Net-(Q2-PadC)") (class "Default")
      (node (ref "Q2") (pin "C") (pinfunction "C_C") (pintype "passive"))
      (node (ref "R32") (pin "2") (pinfunction "2_2") (pintype "passive"))
      (node (ref "R33") (pin "2") (pinfunction "2_2") (pintype "passive"))
      (node (ref "R42") (pin "1") (pinfunction "1_1") (pintype "passive"))
    )
    (net (code "115") (name "Net-(Q2-PadE)") (class "Default")
      (node (ref "Q2") (pin "E") (pinfunction "E_E") (pintype "passive"))
      (node (ref "Q3") (pin "C") (pinfunction "C_C") (pintype "passive"))
      (node (ref "R42") (pin "2") (pinfunction "2_2") (pintype "passive"))
    )
    (net (code "116") (name "Net-(Q5-PadB)") (class "Default")
      (node (ref "Q5") (pin "B") (pinfunction "B_B") (pintype "passive"))
      (node (ref "R50") (pin "1") (pinfunction "1_1") (pintype "passive"))
      (node (ref "T2") (pin "B") (pinfunction "B_B") (pintype "passive"))
    )
    (net (code "117") (name "Net-(Q5-PadE)") (class "Default")
      (node (ref "Q5") (pin "E") (pinfunction "E_E") (pintype "passive"))
      (node (ref "R59") (pin "1") (pinfunction "1_1") (pintype "passive"))
    )
    (net (code "118") (name "Net-(Q6-G)") (class "Default")
      (node (ref "C82") (pin "1") (pinfunction "1_1") (pintype "passive"))
      (node (ref "Q6") (pin "1") (pinfunction "G_1") (pintype "passive"))
      (node (ref "R66") (pin "1") (pinfunction "1_1") (pintype "passive"))
      (node (ref "R67") (pin "1") (pinfunction "1_1") (pintype "passive"))
    )
    (net (code "119") (name "Net-(R4-Pad2)") (class "Default")
      (node (ref "R4") (pin "2") (pinfunction "2_2") (pintype "passive"))
      (node (ref "R5") (pin "2") (pinfunction "2_2") (pintype "passive"))
      (node (ref "R6") (pin "2") (pinfunction "2_2") (pintype "passive"))
    )
    (net (code "120") (name "Net-(R26-Pad1)") (class "Default")
      (node (ref "R26") (pin "1") (pinfunction "1_1") (pintype "passive"))
      (node (ref "R28") (pin "1") (pinfunction "1_1") (pintype "passive"))
      (node (ref "X1") (pin "1") (pinfunction "1_1") (pintype "passive"))
    )
    (net (code "121") (name "Net-(R28-Pad2)") (class "Default")
      (node (ref "R28") (pin "2") (pinfunction "2_2") (pintype "passive"))
      (node (ref "R31") (pin "2") (pinfunction "2_2") (pintype "passive"))
      (node (ref "R32") (pin "1") (pinfunction "1_1") (pintype "passive"))
    )
    (net (code "122") (name "Net-(R36-Pad2)") (class "Default")
      (node (ref "R36") (pin "2") (pinfunction "2_2") (pintype "passive"))
      (node (ref "R44") (pin "1") (pinfunction "1_1") (pintype "passive"))
      (node (ref "T1") (pin "E") (pinfunction "E_E") (pintype "passive"))
    )
    (net (code "123") (name "Net-(R43-Pad2)") (class "Default")
      (node (ref "R43") (pin "2") (pinfunction "2_2") (pintype "passive"))
      (node (ref "T2") (pin "E") (pinfunction "E_E") (pintype "passive"))
    )
    (net (code "124") (name "Net-(R50-Pad2)") (class "Default")
      (node (ref "R50") (pin "2") (pinfunction "2_2") (pintype "passive"))
      (node (ref "R56") (pin "1") (pinfunction "1_1") (pintype "passive"))
      (node (ref "T4") (pin "C") (pinfunction "C_C") (pintype "passive"))
    )
    (net (code "125") (name "Net-(R57-Pad1)") (class "Default")
      (node (ref "R57") (pin "1") (pinfunction "1_1") (pintype "passive"))
      (node (ref "R60") (pin "1") (pinfunction "1_1") (pintype "passive"))
      (node (ref "T5") (pin "B") (pinfunction "B_B") (pintype "passive"))
    )
    (net (code "126") (name "Net-(R63-Pad1)") (class "Default")
      (node (ref "R63") (pin "1") (pinfunction "1_1") (pintype "passive"))
      (node (ref "X5") (pin "1") (pinfunction "1_1") (pintype "passive"))
    )
    (net (code "127") (name "Net-(R64-Pad2)") (class "Default")
      (node (ref "R64") (pin "2") (pinfunction "2_2") (pintype "passive"))
      (node (ref "T5") (pin "E") (pinfunction "E_E") (pintype "passive"))
      (node (ref "T6") (pin "C") (pinfunction "C_C") (pintype "passive"))
    )
    (net (code "128") (name "Net-(R65-Pad2)") (class "Default")
      (node (ref "R65") (pin "2") (pinfunction "2_2") (pintype "passive"))
      (node (ref "R73") (pin "1") (pinfunction "1_1") (pintype "passive"))
      (node (ref "T6") (pin "E") (pinfunction "E_E") (pintype "passive"))
    )
    (net (code "129") (name "Net-(R68-Pad2)") (class "Default")
      (node (ref "R68") (pin "2") (pinfunction "2_2") (pintype "passive"))
      (node (ref "R69") (pin "1") (pinfunction "1_1") (pintype "passive"))
      (node (ref "T7") (pin "E") (pinfunction "E_E") (pintype "passive"))
    )
    (net (code "130") (name "Net-(RLY1-PIN10)") (class "Default")
      (node (ref "R41") (pin "1") (pinfunction "1_1") (pintype "passive"))
      (node (ref "R46") (pin "2") (pinfunction "2_2") (pintype "passive"))
      (node (ref "R49") (pin "1") (pinfunction "1_1") (pintype "passive"))
      (node (ref "RLY1") (pin "10") (pinfunction "PIN10_10") (pintype "bidirectional"))
    )
    (net (code "131") (name "Net-(T4-PadE)") (class "Default")
      (node (ref "T4") (pin "E") (pinfunction "E_E") (pintype "passive"))
      (node (ref "T5") (pin "C") (pinfunction "C_C") (pintype "passive"))
    )
    (net (code "132") (name "ONE_SHOT_CAP") (class "Default")
      (node (ref "C66") (pin "1") (pinfunction "1_1") (pintype "passive"))
      (node (ref "M1") (pin "3") (pinfunction "D_3") (pintype "passive"))
      (node (ref "R47") (pin "1") (pinfunction "1_1") (pintype "passive"))
      (node (ref "R61") (pin "2") (pinfunction "2_2") (pintype "passive"))
    )
    (net (code "133") (name "ONE_SHOT_CLR") (class "Default")
      (node (ref "IC15") (pin "7") (pinfunction "Q_7") (pintype "bidirectional"))
      (node (ref "M1") (pin "1") (pinfunction "G_1") (pintype "passive"))
      (node (ref "R62") (pin "1") (pinfunction "1_1") (pintype "passive"))
    )
    (net (code "134") (name "PP_N5V0_ANALOG") (class "Default")
      (node (ref "C38") (pin "1") (pinfunction "1_1") (pintype "passive"))
      (node (ref "C39") (pin "1") (pinfunction "1_1") (pintype "passive"))
      (node (ref "C44") (pin "1") (pinfunction "1_1") (pintype "passive"))
      (node (ref "C45") (pin "1") (pinfunction "1_1") (pintype "passive"))
      (node (ref "C47") (pin "1") (pinfunction "1_1") (pintype "passive"))
      (node (ref "C48") (pin "1") (pinfunction "1_1") (pintype "passive"))
      (node (ref "C52") (pin "1") (pinfunction "1_1") (pintype "passive"))
      (node (ref "C87") (pin "1") (pinfunction "1_1") (pintype "passive"))
      (node (ref "C88") (pin "1") (pinfunction "1_1") (pintype "passive"))
      (node (ref "C95") (pin "1") (pinfunction "1_1") (pintype "passive"))
      (node (ref "IC10") (pin "1") (pinfunction "OUT_1") (pintype "bidirectional"))
      (node (ref "IC16") (pin "4") (pinfunction "V-_4") (pintype "power_in"))
      (node (ref "IC17") (pin "2") (pinfunction "V-_2") (pintype "power_in"))
      (node (ref "IC5") (pin "13") (pinfunction "VEE_13") (pintype "bidirectional"))
      (node (ref "IC9") (pin "4") (pinfunction "V-_4") (pintype "power_in"))
      (node (ref "R36") (pin "1") (pinfunction "1_1") (pintype "passive"))
      (node (ref "R38") (pin "2") (pinfunction "2_2") (pintype "passive"))
      (node (ref "R39") (pin "1") (pinfunction "1_1") (pintype "passive"))
      (node (ref "R64") (pin "1") (pinfunction "1_1") (pintype "passive"))
      (node (ref "R65") (pin "1") (pinfunction "1_1") (pintype "passive"))
      (node (ref "R68") (pin "1") (pinfunction "1_1") (pintype "passive"))
      (node (ref "TP8") (pin "TP") (pinfunction "TP_TP") (pintype "input"))
    )
    (net (code "135") (name "PP_N6V0_CUK") (class "Default")
      (node (ref "C58") (pin "1") (pinfunction "1_1") (pintype "passive"))
      (node (ref "C60") (pin "1") (pinfunction "1_1") (pintype "passive"))
      (node (ref "IC10") (pin "5") (pinfunction "EN_5") (pintype "bidirectional"))
      (node (ref "IC10") (pin "8") (pinfunction "IN_8") (pintype "bidirectional"))
      (node (ref "L6") (pin "2") (pinfunction "2_2") (pintype "bidirectional"))
      (node (ref "R48") (pin "1") (pinfunction "1_1") (pintype "passive"))
    )
    (net (code "136") (name "PP_P3V3") (class "Default")
      (node (ref "C103") (pin "1") (pinfunction "1_1") (pintype "passive"))
      (node (ref "C106") (pin "1") (pinfunction "1_1") (pintype "passive"))
      (node (ref "C107") (pin "1") (pinfunction "1_1") (pintype "passive"))
      (node (ref "C108") (pin "1") (pinfunction "1_1") (pintype "passive"))
      (node (ref "C19") (pin "1") (pinfunction "1_1") (pintype "passive"))
      (node (ref "C20") (pin "1") (pinfunction "1_1") (pintype "passive"))
      (node (ref "C22") (pin "1") (pinfunction "1_1") (pintype "passive"))
      (node (ref "C23") (pin "1") (pinfunction "1_1") (pintype "passive"))
      (node (ref "C27") (pin "1") (pinfunction "1_1") (pintype "passive"))
      (node (ref "C28") (pin "1") (pinfunction "1_1") (pintype "passive"))
      (node (ref "C32") (pin "1") (pinfunction "1_1") (pintype "passive"))
      (node (ref "C33") (pin "1") (pinfunction "1_1") (pintype "passive"))
      (node (ref "C34") (pin "1") (pinfunction "1_1") (pintype "passive"))
      (node (ref "C35") (pin "1") (pinfunction "1_1") (pintype "passive"))
      (node (ref "C42") (pin "1") (pinfunction "1_1") (pintype "passive"))
      (node (ref "C5") (pin "1") (pinfunction "1_1") (pintype "passive"))
      (node (ref "C51") (pin "1") (pinfunction "1_1") (pintype "passive"))
      (node (ref "C54") (pin "1") (pinfunction "1_1") (pintype "passive"))
      (node (ref "C62") (pin "1") (pinfunction "1_1") (pintype "passive"))
      (node (ref "C63") (pin "1") (pinfunction "1_1") (pintype "passive"))
      (node (ref "C77") (pin "1") (pinfunction "1_1") (pintype "passive"))
      (node (ref "C80") (pin "1") (pinfunction "1_1") (pintype "passive"))
      (node (ref "C81") (pin "1") (pinfunction "1_1") (pintype "passive"))
      (node (ref "C84") (pin "1") (pinfunction "1_1") (pintype "passive"))
      (node (ref "C86") (pin "1") (pinfunction "1_1") (pintype "passive"))
      (node (ref "C91") (pin "1") (pinfunction "1_1") (pintype "passive"))
      (node (ref "C92") (pin "1") (pinfunction "1_1") (pintype "passive"))
      (node (ref "C93") (pin "1") (pinfunction "1_1") (pintype "passive"))
      (node (ref "D2") (pin "3") (pinfunction "C_3") (pintype "passive"))
      (node (ref "IC12") (pin "5") (pinfunction "VCC_5") (pintype "power_in"))
      (node (ref "IC14") (pin "5") (pinfunction "VCC_5") (pintype "bidirectional"))
      (node (ref "IC18") (pin "5") (pinfunction "VBUS_5") (pintype "bidirectional"))
      (node (ref "IC21") (pin "1") (pinfunction "VBAT_1") (pintype "bidirectional"))
      (node (ref "IC21") (pin "19") (pinfunction "VDD1_19") (pintype "bidirectional"))
      (node (ref "IC21") (pin "32") (pinfunction "VDD2_32") (pintype "bidirectional"))
      (node (ref "IC21") (pin "48") (pinfunction "VDD3_48") (pintype "bidirectional"))
      (node (ref "IC21") (pin "64") (pinfunction "VDD4_64") (pintype "bidirectional"))
      (node (ref "IC22") (pin "11") (pinfunction "VDDIO_11") (pintype "bidirectional"))
      (node (ref "IC22") (pin "18") (pinfunction "~{LDAC}_18") (pintype "bidirectional"))
      (node (ref "IC24") (pin "2") (pinfunction "OUT_2") (pintype "bidirectional"))
      (node (ref "IC24") (pin "4") (pinfunction "TAB_4") (pintype "bidirectional"))
      (node (ref "IC4") (pin "5") (pinfunction "VCC_5") (pintype "power_in"))
      (node (ref "IC5") (pin "12") (pinfunction "VCCO_12") (pintype "bidirectional"))
      (node (ref "IC5") (pin "9") (pinfunction "VCCO_9") (pintype "bidirectional"))
      (node (ref "IC6") (pin "8") (pinfunction "VCC_8") (pintype "bidirectional"))
      (node (ref "IC8") (pin "2") (pinfunction "D_2") (pintype "bidirectional"))
      (node (ref "IC8") (pin "8") (pinfunction "VDD_8") (pintype "bidirectional"))
      (node (ref "L2") (pin "1") (pinfunction "P$1_1") (pintype "bidirectional"))
      (node (ref "L7") (pin "1") (pinfunction "P$1_1") (pintype "bidirectional"))
      (node (ref "L8") (pin "1") (pinfunction "P$1_1") (pintype "bidirectional"))
      (node (ref "PROG") (pin "1") (pinfunction "1_1") (pintype "bidirectional"))
      (node (ref "R10") (pin "1") (pinfunction "1_1") (pintype "passive"))
      (node (ref "R11") (pin "1") (pinfunction "1_1") (pintype "passive"))
      (node (ref "R74") (pin "1") (pinfunction "1_1") (pintype "passive"))
      (node (ref "R75") (pin "1") (pinfunction "1_1") (pintype "passive"))
      (node (ref "TP23") (pin "TP") (pinfunction "TP_TP") (pintype "input"))
      (node (ref "U2") (pin "8") (pinfunction "VCC_8") (pintype "power_in"))
      (node (ref "U3") (pin "8") (pinfunction "VCC_8") (pintype "power_in"))
    )
    (net (code "137") (name "PP_P3V3_DAC2") (class "Default")
      (node (ref "C17") (pin "1") (pinfunction "1_1") (pintype "passive"))
      (node (ref "C18") (pin "1") (pinfunction "1_1") (pintype "passive"))
      (node (ref "L2") (pin "2") (pinfunction "P$2_2") (pintype "bidirectional"))
      (node (ref "U1") (pin "3") (pinfunction "VDD_3") (pintype "power_in"))
    )
    (net (code "138") (name "PP_P3V3_VDDA") (class "Default")
      (node (ref "C79") (pin "1") (pinfunction "1_1") (pintype "passive"))
      (node (ref "C85") (pin "1") (pinfunction "1_1") (pintype "passive"))
      (node (ref "IC21") (pin "13") (pinfunction "VDDA_13") (pintype "bidirectional"))
      (node (ref "L7") (pin "2") (pinfunction "P$2_2") (pintype "bidirectional"))
    )
    (net (code "139") (name "PP_P5V0_ANALOG") (class "Default")
      (node (ref "C111") (pin "1") (pinfunction "1_1") (pintype "passive"))
      (node (ref "C12") (pin "1") (pinfunction "1_1") (pintype "passive"))
      (node (ref "C21") (pin "1") (pinfunction "1_1") (pintype "passive"))
      (node (ref "C37") (pin "1") (pinfunction "1_1") (pintype "passive"))
      (node (ref "C43") (pin "1") (pinfunction "1_1") (pintype "passive"))
      (node (ref "C49") (pin "1") (pinfunction "1_1") (pintype "passive"))
      (node (ref "C50") (pin "1") (pinfunction "1_1") (pintype "passive"))
      (node (ref "C6") (pin "1") (pinfunction "1_1") (pintype "passive"))
      (node (ref "C64") (pin "1") (pinfunction "1_1") (pintype "passive"))
      (node (ref "C8") (pin "1") (pinfunction "1_1") (pintype "passive"))
      (node (ref "C89") (pin "1") (pinfunction "1_1") (pintype "passive"))
      (node (ref "C90") (pin "1") (pinfunction "1_1") (pintype "passive"))
      (node (ref "C96") (pin "1") (pinfunction "1_1") (pintype "passive"))
      (node (ref "IC1") (pin "1") (pinfunction "OUT_1") (pintype "bidirectional"))
      (node (ref "IC16") (pin "8") (pinfunction "V+_8") (pintype "power_in"))
      (node (ref "IC17") (pin "5") (pinfunction "V+_5") (pintype "power_in"))
      (node (ref "IC20") (pin "6") (pinfunction "G_6") (pintype "bidirectional"))
      (node (ref "IC20") (pin "9") (pinfunction "G_9") (pintype "bidirectional"))
      (node (ref "IC23") (pin "5") (pinfunction "V+_5") (pintype "power_in"))
      (node (ref "IC5") (pin "16") (pinfunction "VCCI_16") (pintype "bidirectional"))
      (node (ref "IC5") (pin "5") (pinfunction "VCCI_5") (pintype "bidirectional"))
      (node (ref "IC9") (pin "8") (pinfunction "V+_8") (pintype "power_in"))
      (node (ref "L10") (pin "1") (pinfunction "P$1_1") (pintype "bidirectional"))
      (node (ref "Q2") (pin "B") (pinfunction "B_B") (pintype "passive"))
      (node (ref "R12") (pin "2") (pinfunction "2_2") (pintype "passive"))
      (node (ref "R37") (pin "2") (pinfunction "2_2") (pintype "passive"))
      (node (ref "R51") (pin "2") (pinfunction "2_2") (pintype "passive"))
      (node (ref "T4") (pin "B") (pinfunction "B_B") (pintype "passive"))
      (node (ref "TP4") (pin "TP") (pinfunction "TP_TP") (pintype "input"))
    )
    (net (code "140") (name "PP_P5V0_DAC1") (class "Default")
      (node (ref "C98") (pin "1") (pinfunction "1_1") (pintype "passive"))
      (node (ref "C99") (pin "1") (pinfunction "1_1") (pintype "passive"))
      (node (ref "IC22") (pin "10") (pinfunction "VDD_10") (pintype "bidirectional"))
      (node (ref "L10") (pin "2") (pinfunction "P$2_2") (pintype "bidirectional"))
      (node (ref "R82") (pin "1") (pinfunction "1_1") (pintype "passive"))
    )
    (net (code "141") (name "PP_P15V0_ANALOG") (class "Default")
      (node (ref "C10") (pin "1") (pinfunction "1_1") (pintype "passive"))
      (node (ref "C13") (pin "1") (pinfunction "1_1") (pintype "passive"))
      (node (ref "C55") (pin "1") (pinfunction "1_1") (pintype "passive"))
      (node (ref "C7") (pin "1") (pinfunction "1_1") (pintype "passive"))
      (node (ref "C71") (pin "1") (pinfunction "1_1") (pintype "passive"))
      (node (ref "C72") (pin "1") (pinfunction "1_1") (pintype "passive"))
      (node (ref "C83") (pin "+") (pinfunction "+_+") (pintype "passive"))
      (node (ref "C9") (pin "1") (pinfunction "1_1") (pintype "passive"))
      (node (ref "IC1") (pin "5") (pinfunction "EN_5") (pintype "bidirectional"))
      (node (ref "IC1") (pin "8") (pinfunction "IN_8") (pintype "bidirectional"))
      (node (ref "IC19") (pin "11") (pinfunction "SUBC_11") (pintype "bidirectional"))
      (node (ref "IC19") (pin "12") (pinfunction "S_12") (pintype "bidirectional"))
      (node (ref "IC19") (pin "3") (pinfunction "S_3") (pintype "bidirectional"))
      (node (ref "IC2") (pin "1") (pinfunction "OUT_1") (pintype "bidirectional"))
      (node (ref "R13") (pin "2") (pinfunction "2_2") (pintype "passive"))
      (node (ref "R56") (pin "2") (pinfunction "2_2") (pintype "passive"))
      (node (ref "T2") (pin "C") (pinfunction "C_C") (pintype "passive"))
      (node (ref "T3") (pin "C") (pinfunction "C_C") (pintype "passive"))
      (node (ref "TP2") (pin "TP") (pinfunction "TP_TP") (pintype "input"))
    )
    (net (code "142") (name "PP_P16V0_BOOST") (class "Default")
      (node (ref "C11") (pin "1") (pinfunction "1_1") (pintype "passive"))
      (node (ref "C30") (pin "+") (pinfunction "+_+") (pintype "passive"))
      (node (ref "IC2") (pin "5") (pinfunction "EN_5") (pintype "bidirectional"))
      (node (ref "IC2") (pin "8") (pinfunction "IN_8") (pintype "bidirectional"))
      (node (ref "L3") (pin "4") (pinfunction "4_4") (pintype "bidirectional"))
      (node (ref "R3") (pin "2") (pinfunction "2_2") (pintype "passive"))
      (node (ref "R4") (pin "1") (pinfunction "1_1") (pintype "passive"))
    )
    (net (code "143") (name "QUENCH_WFM") (class "Default")
      (node (ref "C73") (pin "1") (pinfunction "1_1") (pintype "passive"))
      (node (ref "IC13") (pin "4") (pinfunction "O_4") (pintype "output"))
      (node (ref "R60") (pin "2") (pinfunction "2_2") (pintype "passive"))
    )
    (net (code "144") (name "SMPS_USB_VDD") (class "Default")
      (node (ref "C110") (pin "1") (pinfunction "1_1") (pintype "passive"))
      (node (ref "C16") (pin "1") (pinfunction "1_1") (pintype "passive"))
      (node (ref "C24") (pin "1") (pinfunction "1_1") (pintype "passive"))
      (node (ref "C31") (pin "+") (pinfunction "+_+") (pintype "passive"))
      (node (ref "C53") (pin "1") (pinfunction "1_1") (pintype "passive"))
      (node (ref "C61") (pin "1") (pinfunction "1_1") (pintype "passive"))
      (node (ref "C67") (pin "1") (pinfunction "1_1") (pintype "passive"))
      (node (ref "C82") (pin "2") (pinfunction "2_2") (pintype "passive"))
      (node (ref "D7") (pin "3") (pinfunction "C_3") (pintype "passive"))
      (node (ref "D8") (pin "3") (pinfunction "C_3") (pintype "passive"))
      (node (ref "IC11") (pin "15") (pinfunction "VIN_15") (pintype "bidirectional"))
      (node (ref "IC3") (pin "15") (pinfunction "VIN_15") (pintype "bidirectional"))
      (node (ref "L4") (pin "1") (pinfunction "1_1") (pintype "bidirectional"))
      (node (ref "L6") (pin "1") (pinfunction "1_1") (pintype "bidirectional"))
      (node (ref "Q6") (pin "3") (pinfunction "D_3") (pintype "passive"))
      (node (ref "RLY1") (pin "3") (pinfunction "PIN3_3") (pintype "bidirectional"))
      (node (ref "RLY2") (pin "3") (pinfunction "PIN3_3") (pintype "bidirectional"))
    )
    (net (code "145") (name "SPAD_PULLDN_SENSE") (class "Default")
      (node (ref "IC5") (pin "3") (pinfunction "VN_3") (pintype "bidirectional"))
      (node (ref "R26") (pin "2") (pinfunction "2_2") (pintype "passive"))
      (node (ref "R27") (pin "2") (pinfunction "2_2") (pintype "passive"))
      (node (ref "R33") (pin "1") (pinfunction "1_1") (pintype "passive"))
    )
    (net (code "146") (name "TP_FB_CUK") (class "Default")
      (node (ref "IC11") (pin "7") (pinfunction "FB_7") (pintype "bidirectional"))
      (node (ref "TP12") (pin "TP") (pinfunction "TP_TP") (pintype "input"))
    )
    (net (code "147") (name "TP_NFB_BOOST") (class "Default")
      (node (ref "IC3") (pin "10") (pinfunction "NFB_10") (pintype "bidirectional"))
      (node (ref "TP7") (pin "TP") (pinfunction "TP_TP") (pintype "input"))
    )
    (net (code "148") (name "TP_SYNC_BOOST") (class "Default")
      (node (ref "IC3") (pin "4") (pinfunction "SYNC_4") (pintype "bidirectional"))
      (node (ref "TP3") (pin "TP") (pinfunction "TP_TP") (pintype "input"))
    )
    (net (code "149") (name "TP_SYNC_CUK") (class "Default")
      (node (ref "IC11") (pin "4") (pinfunction "SYNC_4") (pintype "bidirectional"))
      (node (ref "TP9") (pin "TP") (pinfunction "TP_TP") (pintype "input"))
    )
    (net (code "150") (name "USBCONN_P1") (class "Default")
      (node (ref "C101") (pin "1") (pinfunction "1_1") (pintype "passive"))
      (node (ref "L9") (pin "1") (pinfunction "P$1_1") (pintype "bidirectional"))
      (node (ref "X8") (pin "1") (pinfunction "1_1") (pintype "passive"))
    )
    (net (code "151") (name "USBCONN_P4") (class "Default")
      (node (ref "L11") (pin "1") (pinfunction "P$1_1") (pintype "bidirectional"))
      (node (ref "X8") (pin "4") (pinfunction "4_4") (pintype "passive"))
    )
    (net (code "152") (name "USBD_CONN_N") (class "Default")
      (node (ref "IC18") (pin "3") (pinfunction "I/O2_3") (pintype "bidirectional"))
      (node (ref "X8") (pin "2") (pinfunction "2_2") (pintype "passive"))
    )
    (net (code "153") (name "USBD_CONN_P") (class "Default")
      (node (ref "IC18") (pin "1") (pinfunction "I/O1_1_1") (pintype "bidirectional"))
      (node (ref "X8") (pin "3") (pinfunction "3_3") (pintype "passive"))
    )
    (net (code "154") (name "USBD_TVS_N") (class "Default")
      (node (ref "IC18") (pin "4") (pinfunction "I/O2_2_4") (pintype "bidirectional"))
      (node (ref "R77") (pin "2") (pinfunction "2_2") (pintype "passive"))
    )
    (net (code "155") (name "USBD_TVS_P") (class "Default")
      (node (ref "IC18") (pin "6") (pinfunction "I/O1_2_6") (pintype "bidirectional"))
      (node (ref "R76") (pin "2") (pinfunction "2_2") (pintype "passive"))
    )
    (net (code "156") (name "USB_VDD") (class "Default")
      (node (ref "C104") (pin "1") (pinfunction "1_1") (pintype "passive"))
      (node (ref "C105") (pin "1") (pinfunction "1_1") (pintype "passive"))
      (node (ref "IC24") (pin "3") (pinfunction "IN_3") (pintype "bidirectional"))
      (node (ref "L9") (pin "2") (pinfunction "P$2_2") (pintype "bidirectional"))
      (node (ref "Q6") (pin "2") (pinfunction "S_2") (pintype "passive"))
      (node (ref "R67") (pin "2") (pinfunction "2_2") (pintype "passive"))
    )
    (net (code "157") (name "VBB") (class "Default")
      (node (ref "U3") (pin "4") (pinfunction "VBB_4") (pintype "power_in"))
    )
    (net (code "158") (name "VREF_AV_DET") (class "Default")
      (node (ref "R14") (pin "2") (pinfunction "2_2") (pintype "passive"))
      (node (ref "TP6") (pin "P$1") (pinfunction "P$1_P$1") (pintype "bidirectional"))
      (node (ref "U1") (pin "1") (pinfunction "VOUT_1") (pintype "output"))
    )
    (net (code "159") (name "VREF_CASCODE_IBIAS") (class "Default")
      (node (ref "IC22") (pin "2") (pinfunction "OUT0_2") (pintype "bidirectional"))
      (node (ref "R81") (pin "2") (pinfunction "2_2") (pintype "passive"))
      (node (ref "TP14") (pin "P$1") (pinfunction "P$1_P$1") (pintype "bidirectional"))
    )
    (net (code "160") (name "VREF_DELAY_DN") (class "Default")
      (node (ref "IC22") (pin "9") (pinfunction "OUT7_9") (pintype "bidirectional"))
      (node (ref "R45") (pin "2") (pinfunction "2_2") (pintype "passive"))
      (node (ref "TP21") (pin "P$1") (pinfunction "P$1_P$1") (pintype "bidirectional"))
    )
    (net (code "161") (name "VREF_DELAY_UP") (class "Default")
      (node (ref "IC22") (pin "8") (pinfunction "OUT6_8") (pintype "bidirectional"))
      (node (ref "IC9") (pin "3") (pinfunction "+IN_3") (pintype "input"))
      (node (ref "TP20") (pin "P$1") (pinfunction "P$1_P$1") (pintype "bidirectional"))
    )
    (net (code "162") (name "VREF_DIAMOND_IBIAS") (class "Default")
      (node (ref "IC22") (pin "3") (pinfunction "OUT1_3") (pintype "bidirectional"))
      (node (ref "IC23") (pin "3") (pinfunction "+IN_3") (pintype "input"))
      (node (ref "TP15") (pin "P$1") (pinfunction "P$1_P$1") (pintype "bidirectional"))
    )
    (net (code "163") (name "VREF_ONE_SHOT") (class "Default")
      (node (ref "IC15") (pin "3") (pinfunction "-IN_3") (pintype "bidirectional"))
      (node (ref "IC22") (pin "4") (pinfunction "OUT2_4") (pintype "bidirectional"))
      (node (ref "TP16") (pin "P$1") (pinfunction "P$1_P$1") (pintype "bidirectional"))
    )
    (net (code "164") (name "VREF_SLEW_DN") (class "Default")
      (node (ref "IC22") (pin "6") (pinfunction "OUT4_6") (pintype "bidirectional"))
      (node (ref "R70") (pin "2") (pinfunction "2_2") (pintype "passive"))
      (node (ref "TP18") (pin "P$1") (pinfunction "P$1_P$1") (pintype "bidirectional"))
    )
    (net (code "165") (name "VREF_SLEW_MAX") (class "Default")
      (node (ref "C65") (pin "1") (pinfunction "1_1") (pintype "passive"))
      (node (ref "D5") (pin "3") (pinfunction "C_3") (pintype "passive"))
      (node (ref "IC22") (pin "7") (pinfunction "OUT5_7") (pintype "bidirectional"))
      (node (ref "TP19") (pin "P$1") (pinfunction "P$1_P$1") (pintype "bidirectional"))
    )
    (net (code "166") (name "VREF_SLEW_UP") (class "Default")
      (node (ref "IC16") (pin "3") (pinfunction "+IN_3") (pintype "input"))
      (node (ref "IC22") (pin "5") (pinfunction "OUT3_5") (pintype "bidirectional"))
      (node (ref "TP17") (pin "P$1") (pinfunction "P$1_P$1") (pintype "bidirectional"))
    )
    (net (code "167") (name "V_IVTEST") (class "Default")
      (node (ref "RLY2") (pin "5") (pinfunction "PIN5_5") (pintype "bidirectional"))
      (node (ref "X7") (pin "1") (pinfunction "1_1") (pintype "passive"))
    )
    (net (code "168") (name "V_SCOPE") (class "Default")
      (node (ref "R41") (pin "2") (pinfunction "2_2") (pintype "passive"))
      (node (ref "TP10") (pin "SIG") (pinfunction "1_SIG") (pintype "passive"))
    )
    (net (code "169") (name "V_SPAD") (class "Default")
      (node (ref "RLY1") (pin "5") (pinfunction "PIN5_5") (pintype "bidirectional"))
      (node (ref "RLY2") (pin "10") (pinfunction "PIN10_10") (pintype "bidirectional"))
      (node (ref "X4") (pin "1") (pinfunction "1_1") (pintype "passive"))
    )
    (net (code "170") (name "unconnected-(IC5-VTP-Pad1)") (class "Default")
      (node (ref "IC5") (pin "1") (pinfunction "VTP_1") (pintype "bidirectional"))
    )
    (net (code "171") (name "unconnected-(IC21-PA0-Pad14)") (class "Default")
      (node (ref "IC21") (pin "14") (pinfunction "PA0_14") (pintype "bidirectional"))
    )
    (net (code "172") (name "unconnected-(IC21-PA4{slash}SPI1_NSS-Pad20)") (class "Default")
      (node (ref "IC21") (pin "20") (pinfunction "PA4/SPI1_NSS_20") (pintype "bidirectional"))
    )
    (net (code "173") (name "unconnected-(IC21-PA5{slash}SPI1_SCK-Pad21)") (class "Default")
      (node (ref "IC21") (pin "21") (pinfunction "PA5/SPI1_SCK_21") (pintype "bidirectional"))
    )
    (net (code "174") (name "unconnected-(IC21-PA6{slash}SPI1_MISO-Pad22)") (class "Default")
      (node (ref "IC21") (pin "22") (pinfunction "PA6/SPI1_MISO_22") (pintype "bidirectional"))
    )
    (net (code "175") (name "unconnected-(IC21-PA7{slash}SPI1_MOSI-Pad23)") (class "Default")
      (node (ref "IC21") (pin "23") (pinfunction "PA7/SPI1_MOSI_23") (pintype "bidirectional"))
    )
    (net (code "176") (name "unconnected-(IC21-PA8-Pad41)") (class "Default")
      (node (ref "IC21") (pin "41") (pinfunction "PA8_41") (pintype "bidirectional"))
    )
    (net (code "177") (name "unconnected-(IC21-PA9{slash}UART1_TX-Pad42)") (class "Default")
      (node (ref "IC21") (pin "42") (pinfunction "PA9/UART1_TX_42") (pintype "bidirectional"))
    )
    (net (code "178") (name "unconnected-(IC21-PA10{slash}UART1_RX-Pad43)") (class "Default")
      (node (ref "IC21") (pin "43") (pinfunction "PA10/UART1_RX_43") (pintype "bidirectional"))
    )
    (net (code "179") (name "unconnected-(IC21-PB0-Pad26)") (class "Default")
      (node (ref "IC21") (pin "26") (pinfunction "PB0_26") (pintype "bidirectional"))
    )
    (net (code "180") (name "unconnected-(IC21-PB1-Pad27)") (class "Default")
      (node (ref "IC21") (pin "27") (pinfunction "PB1_27") (pintype "bidirectional"))
    )
    (net (code "181") (name "unconnected-(IC21-PB4{slash}JTRST-Pad56)") (class "Default")
      (node (ref "IC21") (pin "56") (pinfunction "PB4/JTRST_56") (pintype "bidirectional"))
    )
    (net (code "182") (name "unconnected-(IC21-PB8-Pad61)") (class "Default")
      (node (ref "IC21") (pin "61") (pinfunction "PB8_61") (pintype "bidirectional"))
    )
    (net (code "183") (name "unconnected-(IC21-PB9-Pad62)") (class "Default")
      (node (ref "IC21") (pin "62") (pinfunction "PB9_62") (pintype "bidirectional"))
    )
    (net (code "184") (name "unconnected-(IC21-PB10-Pad29)") (class "Default")
      (node (ref "IC21") (pin "29") (pinfunction "PB10_29") (pintype "bidirectional"))
    )
    (net (code "185") (name "unconnected-(IC21-PB14{slash}I2S2_XD-Pad35)") (class "Default")
      (node (ref "IC21") (pin "35") (pinfunction "PB14/I2S2_XD_35") (pintype "bidirectional"))
    )
    (net (code "186") (name "unconnected-(IC21-PB15{slash}I2S2_SD-Pad36)") (class "Default")
      (node (ref "IC21") (pin "36") (pinfunction "PB15/I2S2_SD_36") (pintype "bidirectional"))
    )
    (net (code "187") (name "unconnected-(IC21-PC2-Pad10)") (class "Default")
      (node (ref "IC21") (pin "10") (pinfunction "PC2_10") (pintype "bidirectional"))
    )
    (net (code "188") (name "unconnected-(IC21-PC3-Pad11)") (class "Default")
      (node (ref "IC21") (pin "11") (pinfunction "PC3_11") (pintype "bidirectional"))
    )
    (net (code "189") (name "unconnected-(IC21-PC4-Pad24)") (class "Default")
      (node (ref "IC21") (pin "24") (pinfunction "PC4_24") (pintype "bidirectional"))
    )
    (net (code "190") (name "unconnected-(IC21-PC5-Pad25)") (class "Default")
      (node (ref "IC21") (pin "25") (pinfunction "PC5_25") (pintype "bidirectional"))
    )
    (net (code "191") (name "unconnected-(IC21-PC6{slash}I2S2_MCK-Pad37)") (class "Default")
      (node (ref "IC21") (pin "37") (pinfunction "PC6/I2S2_MCK_37") (pintype "bidirectional"))
    )
    (net (code "192") (name "unconnected-(IC21-PC7-Pad38)") (class "Default")
      (node (ref "IC21") (pin "38") (pinfunction "PC7_38") (pintype "bidirectional"))
    )
    (net (code "193") (name "unconnected-(IC21-PC8{slash}SDIO_D0-Pad39)") (class "Default")
      (node (ref "IC21") (pin "39") (pinfunction "PC8/SDIO_D0_39") (pintype "bidirectional"))
    )
    (net (code "194") (name "unconnected-(IC21-PC9{slash}SDIO_D1-Pad40)") (class "Default")
      (node (ref "IC21") (pin "40") (pinfunction "PC9/SDIO_D1_40") (pintype "bidirectional"))
    )
    (net (code "195") (name "unconnected-(IC21-PC13-Pad2)") (class "Default")
      (node (ref "IC21") (pin "2") (pinfunction "PC13_2") (pintype "bidirectional"))
    )
    (net (code "196") (name "unconnected-(IC21-PC14-Pad3)") (class "Default")
      (node (ref "IC21") (pin "3") (pinfunction "PC14_3") (pintype "bidirectional"))
    )
    (net (code "197") (name "unconnected-(IC21-PC15-Pad4)") (class "Default")
      (node (ref "IC21") (pin "4") (pinfunction "PC15_4") (pintype "bidirectional"))
    )
    (net (code "198") (name "unconnected-(RLY1-PIN7-Pad7)") (class "Default")
      (node (ref "RLY1") (pin "7") (pinfunction "PIN7_7") (pintype "bidirectional"))
    )
    (net (code "199") (name "unconnected-(RLY1-PIN8-Pad8)") (class "Default")
      (node (ref "RLY1") (pin "8") (pinfunction "PIN8_8") (pintype "bidirectional"))
    )
    (net (code "200") (name "unconnected-(RLY2-PIN7-Pad7)") (class "Default")
      (node (ref "RLY2") (pin "7") (pinfunction "PIN7_7") (pintype "bidirectional"))
    )
    (net (code "201") (name "unconnected-(RLY2-PIN8-Pad8)") (class "Default")
      (node (ref "RLY2") (pin "8") (pinfunction "PIN8_8") (pintype "bidirectional"))
    )
    (net (code "202") (name "unconnected-(U2-Q1-Pad3)") (class "Default")
      (node (ref "U2") (pin "3") (pinfunction "Q1_3") (pintype "output"))
    )
    (net (code "203") (name "unconnected-(U2-~{Q1}-Pad4)") (class "Default")
      (node (ref "U2") (pin "4") (pinfunction "~{Q1}_4") (pintype "output"))
    )
    (net (code "204") (name "unconnected-(U3-NC-Pad6)") (class "Default")
      (node (ref "U3") (pin "6") (pinfunction "NC_6") (pintype "no_connect"))
    )
    (net (code "205") (name "unconnected-(U3-NC_2-Pad1)") (class "Default")
      (node (ref "U3") (pin "1") (pinfunction "NC_2_1") (pintype "no_connect"))
    )
    (net (code "206") (name "~{FORCE_QUENCH}") (class "Default")
      (node (ref "IC12") (pin "4") (pinfunction "O_4") (pintype "output"))
      (node (ref "IC8") (pin "7") (pinfunction "~{PRE}_7") (pintype "bidirectional"))
    )
    (net (code "207") (name "~{LOGIC_QUENCH}") (class "Default")
      (node (ref "IC13") (pin "2") (pinfunction "I_2") (pintype "input"))
      (node (ref "IC8") (pin "3") (pinfunction "~{Q}_3") (pintype "bidirectional"))
      (node (ref "TP11") (pin "TP") (pinfunction "TP_TP") (pintype "input"))
    )
    (net (code "208") (name "~{MCU_SHDN_BOOST}") (class "Default")
      (node (ref "IC21") (pin "16") (pinfunction "PA2/UART2_TX_16") (pintype "bidirectional"))
      (node (ref "IC3") (pin "12") (pinfunction "~{SHDN}_12") (pintype "bidirectional"))
    )
    (net (code "209") (name "~{MCU_SHDN_CUK}") (class "Default")
      (node (ref "IC11") (pin "12") (pinfunction "~{SHDN}_12") (pintype "bidirectional"))
      (node (ref "IC21") (pin "15") (pinfunction "PA1_15") (pintype "bidirectional"))
    )
    (net (code "210") (name "~{MCU_SMPS_PRECHG}") (class "Default")
      (node (ref "IC21") (pin "17") (pinfunction "PA3/UART2_RX_17") (pintype "bidirectional"))
      (node (ref "R66") (pin "2") (pinfunction "2_2") (pintype "passive"))
    )
    (net (code "211") (name "~{ONE_SHOT_CLR}") (class "Default")
      (node (ref "IC15") (pin "8") (pinfunction "~{Q}_8") (pintype "bidirectional"))
      (node (ref "IC8") (pin "6") (pinfunction "~{CLR}_6") (pintype "bidirectional"))
    )
  )
)
